# BMS1.net
KiCad netlist of a schematic drawn in Altium Designer
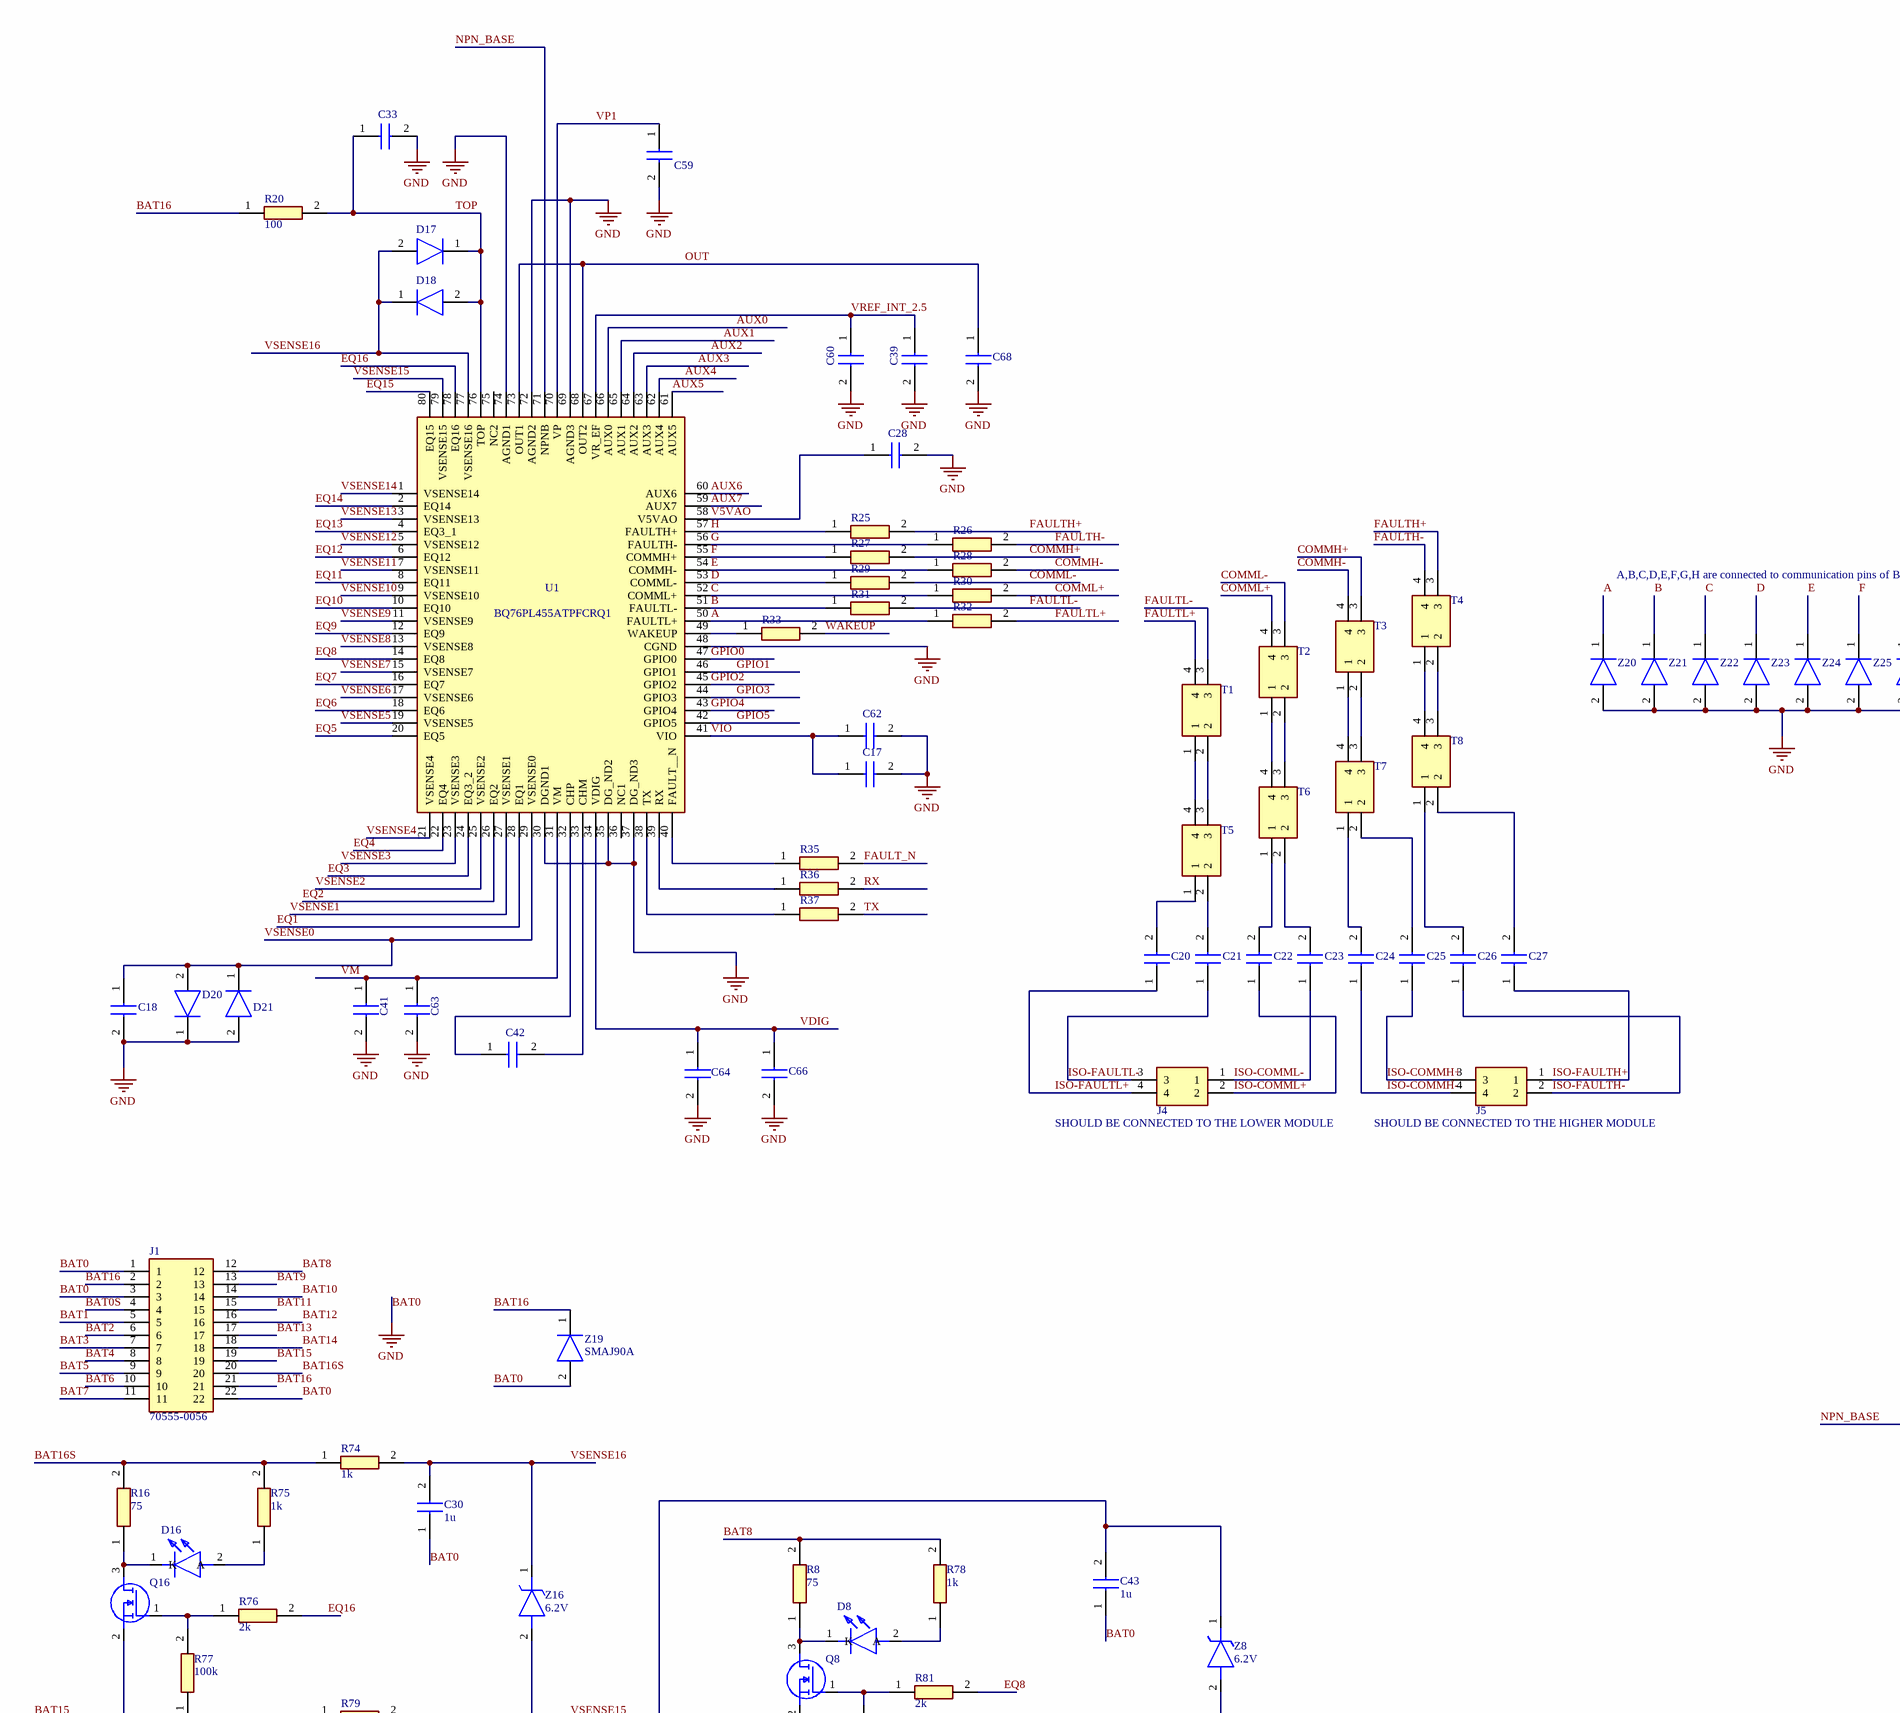
[diagram p0: BMS1.SchDoc, top left]
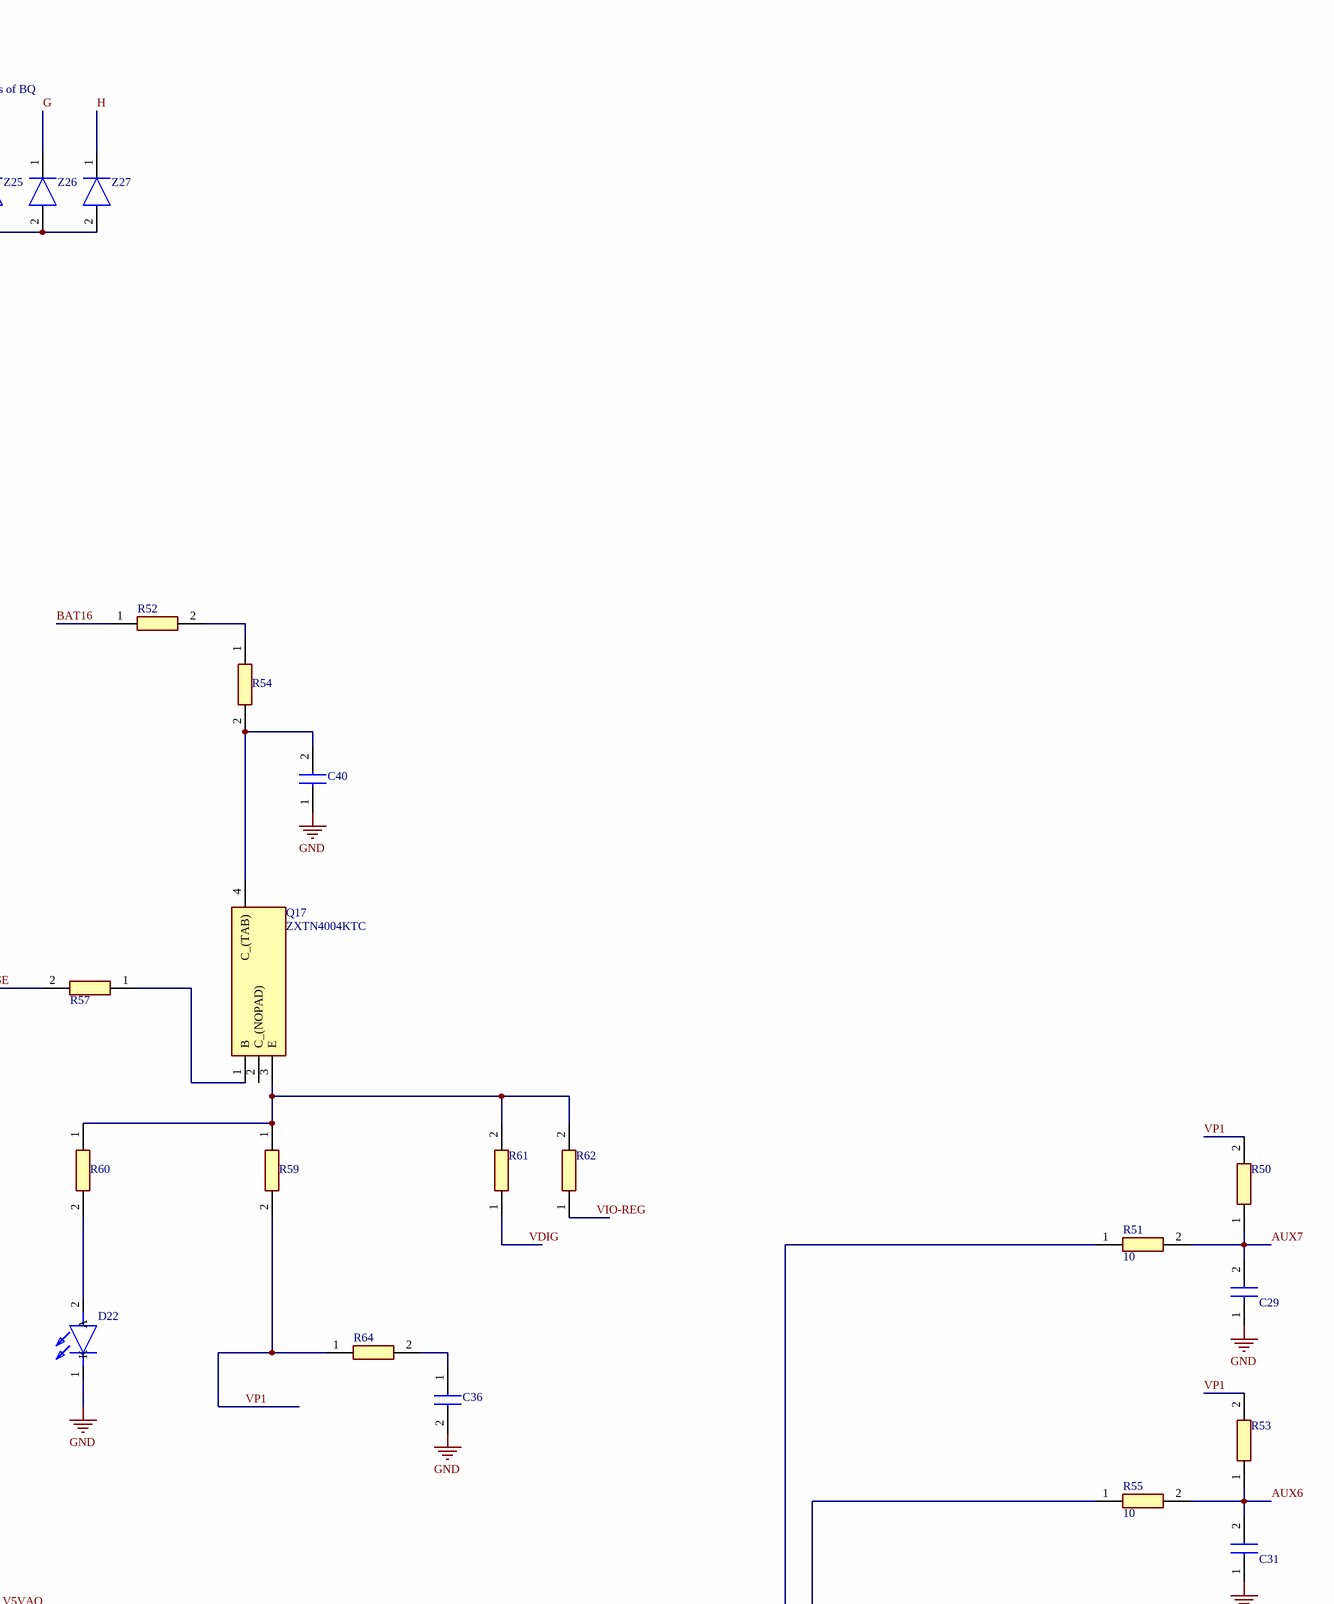
[diagram p1: BMS1.SchDoc, top right]
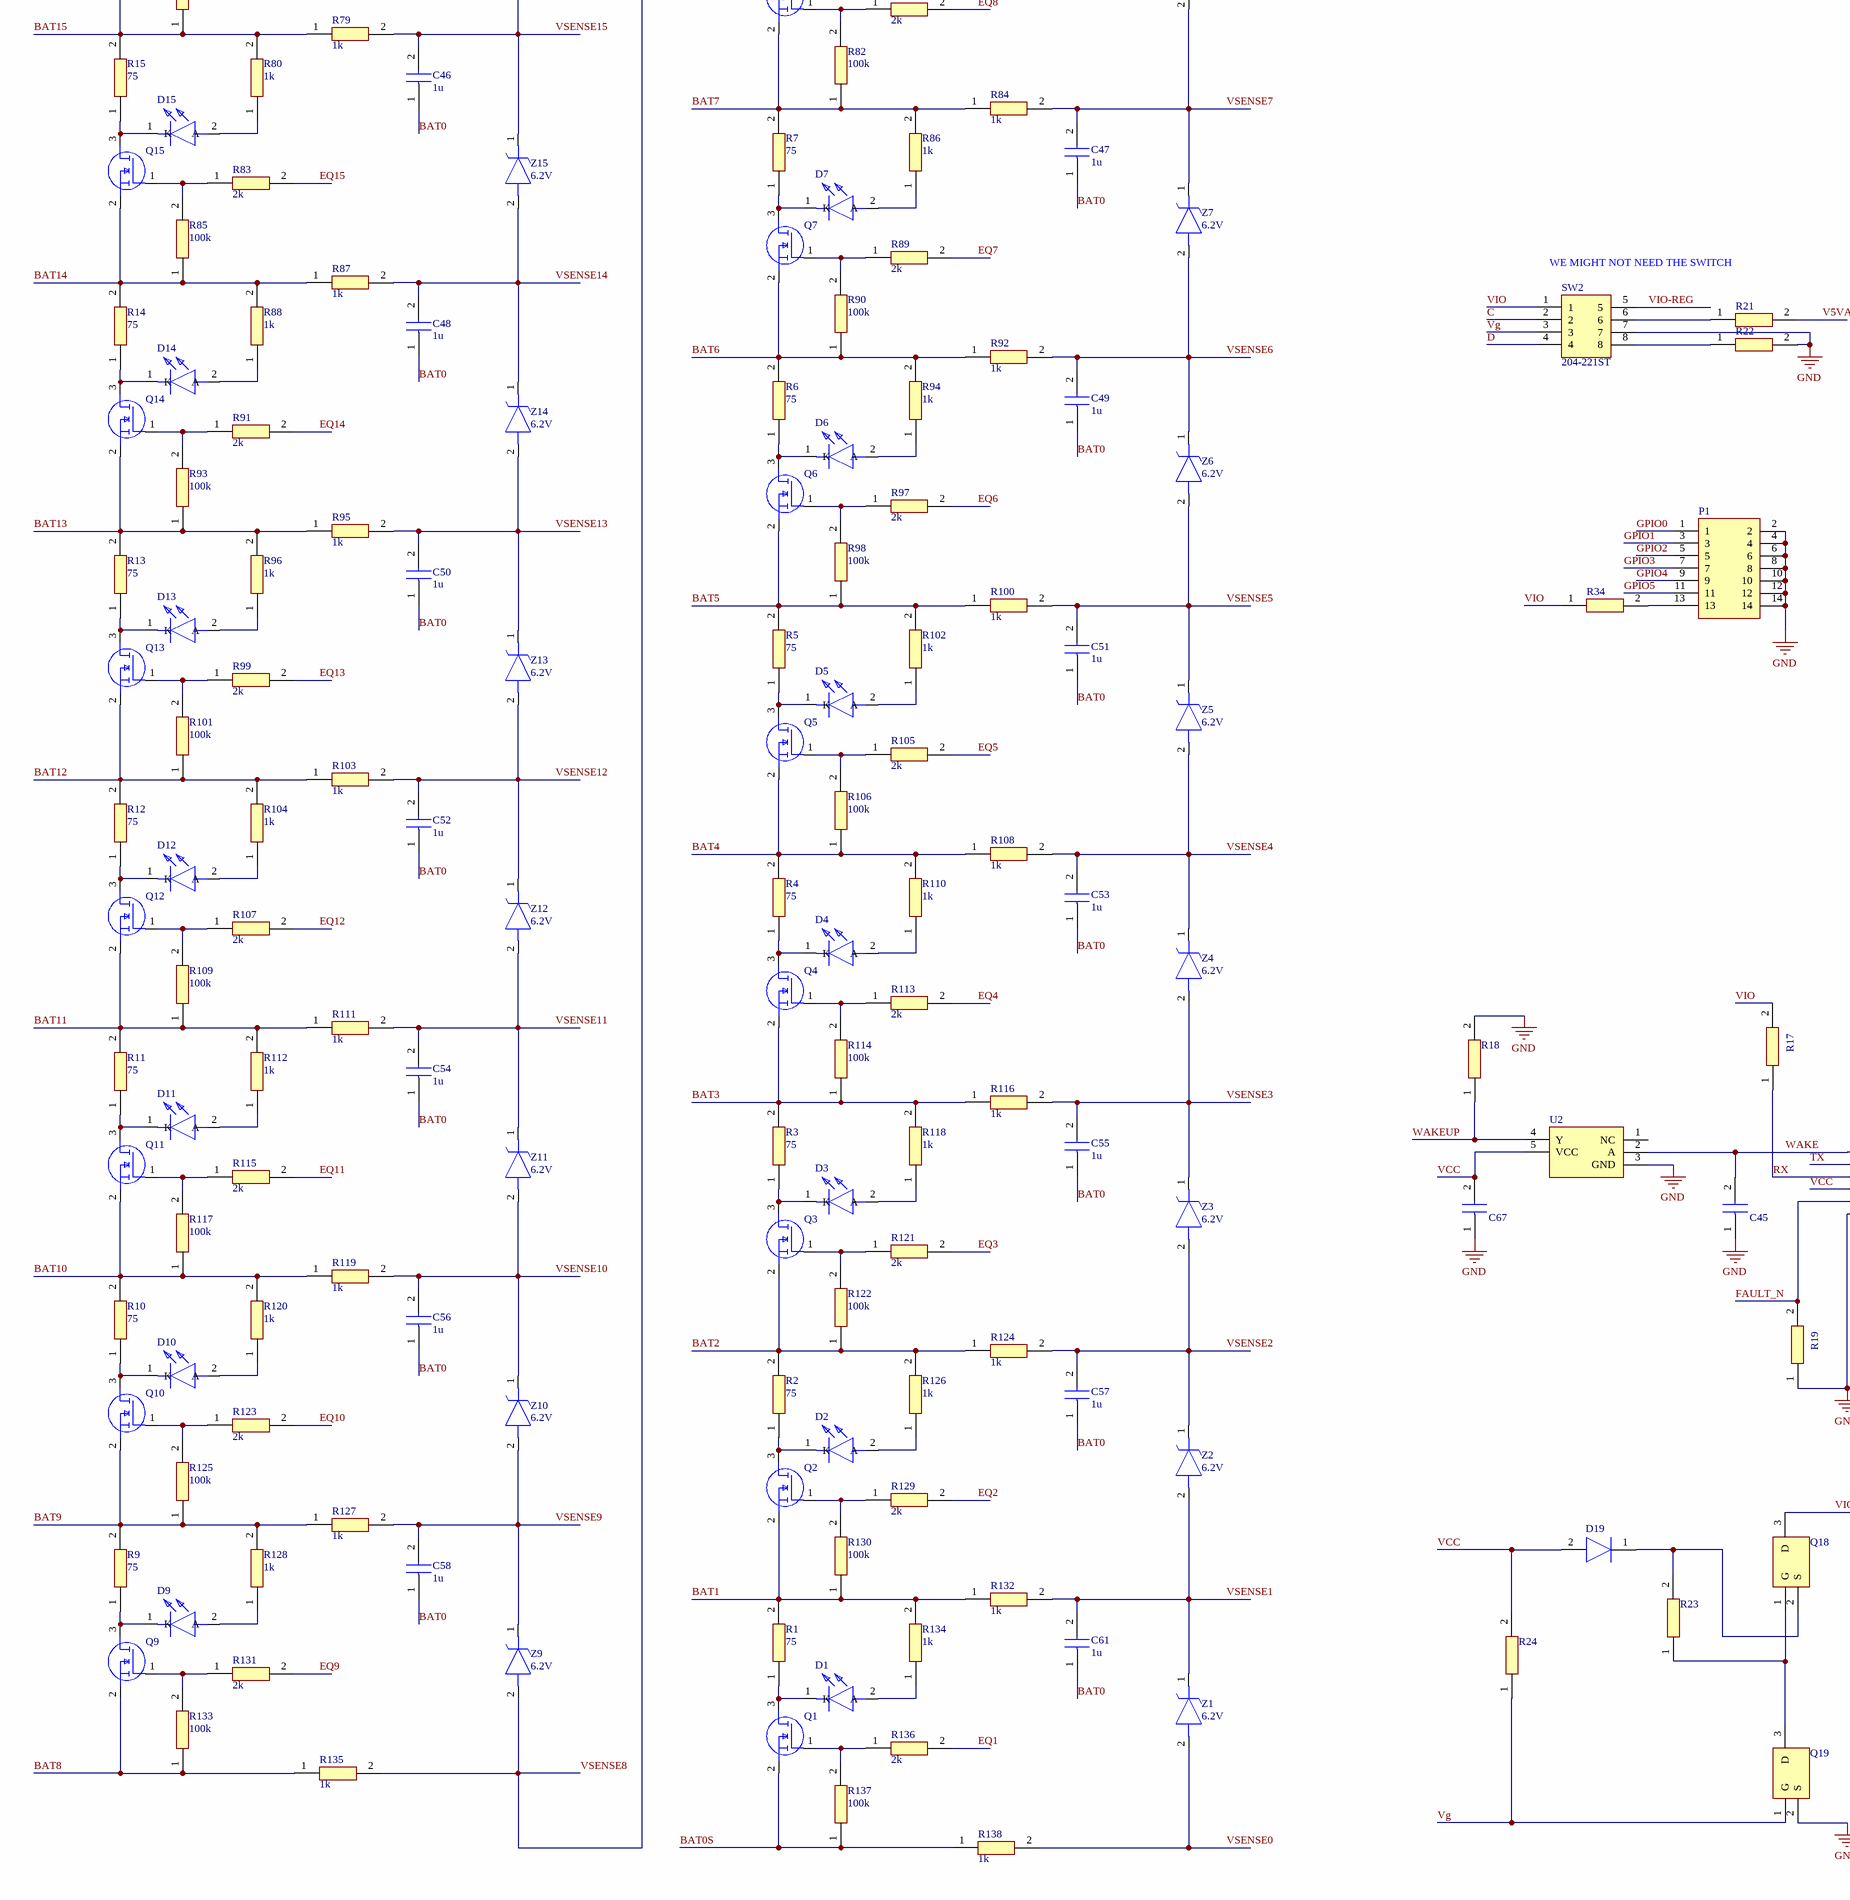
[diagram p2: BMS1.SchDoc, bottom left]
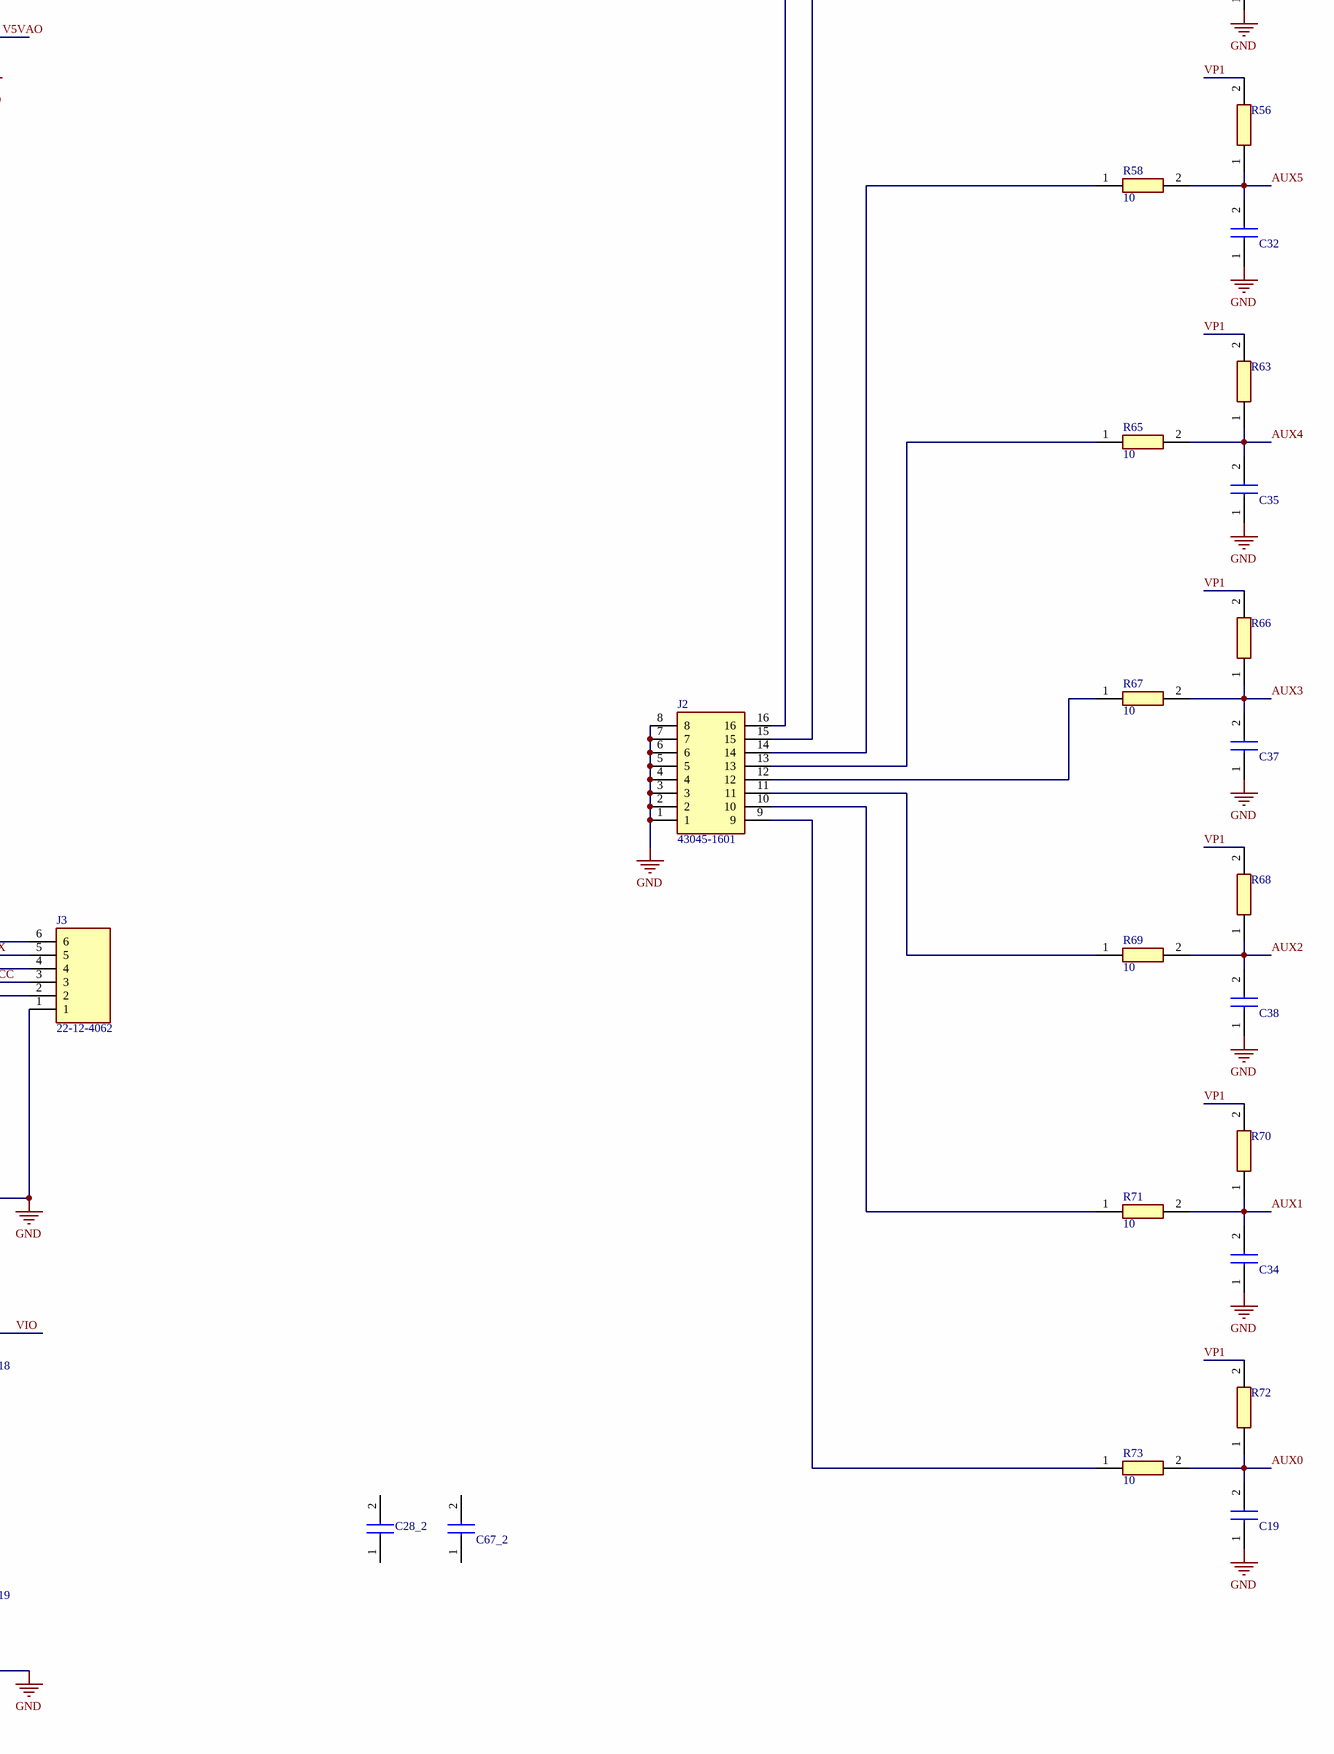
[diagram p3: BMS1.SchDoc, bottom right]

(export (version "E")
  (design (tool "Eeschema 10.0.6"))
  (components
    (comp (ref "C17")
      (value "1u")
      (footprint "SamacSys:CAPC1608X80N")
      (description "Capacitor")
      (fields
        (field (name "MANUFACTURER_PART_NUMBER") "C1608X7R1C105K080AC")
        (field (name "MOUSER PART NUMBER") "810-C1608X7R1C105K")
      )
      (libsource (lib "*") (part "C1608X7R1C105K080AC"))
    )
    (comp (ref "C18")
      (value "1u")
      (footprint "SamacSys:CAPC1608X80N")
      (description "Capacitor")
      (fields
        (field (name "MANUFACTURER_PART_NUMBER") "C1608X7R1C105K080AC")
        (field (name "MOUSER PART NUMBER") "810-C1608X7R1C105K")
      )
      (libsource (lib "*") (part "C1608X7R1C105K080AC"))
    )
    (comp (ref "C19")
      (value "C1608X7R1H104K080AA")
      (footprint "SamacSys:CAPC1608X80N")
      (description "Capacitor")
      (fields
        (field (name "MOUSER PART NUMBER") "810-C1608X7R1H104K")
        (field (name "RS PART NUMBER") "7414459P")
      )
      (libsource (lib "*") (part "C1608X7R1H104K080AA"))
    )
    (comp (ref "C20")
      (value "CC1206KKX7RCBB102")
      (footprint "SamacSys:CAPC3216X70N")
      (description "Capacitor")
      (fields (field (name "MOUSER PART NUMBER") "603-CC126KKX7RCBB102"))
      (libsource (lib "*") (part "CC1206KKX7RCBB102"))
    )
    (comp (ref "C21")
      (value "CC1206KKX7RCBB102")
      (footprint "SamacSys:CAPC3216X70N")
      (description "Capacitor")
      (fields (field (name "MOUSER PART NUMBER") "603-CC126KKX7RCBB102"))
      (libsource (lib "*") (part "CC1206KKX7RCBB102"))
    )
    (comp (ref "C22")
      (value "CC1206KKX7RCBB102")
      (footprint "SamacSys:CAPC3216X70N")
      (description "Capacitor")
      (fields (field (name "MOUSER PART NUMBER") "603-CC126KKX7RCBB102"))
      (libsource (lib "*") (part "CC1206KKX7RCBB102"))
    )
    (comp (ref "C23")
      (value "CC1206KKX7RCBB102")
      (footprint "SamacSys:CAPC3216X70N")
      (description "Capacitor")
      (fields (field (name "MOUSER PART NUMBER") "603-CC126KKX7RCBB102"))
      (libsource (lib "*") (part "CC1206KKX7RCBB102"))
    )
    (comp (ref "C24")
      (value "CC1206KKX7RCBB102")
      (footprint "SamacSys:CAPC3216X70N")
      (description "Capacitor")
      (fields (field (name "MOUSER PART NUMBER") "603-CC126KKX7RCBB102"))
      (libsource (lib "*") (part "CC1206KKX7RCBB102"))
    )
    (comp (ref "C25")
      (value "CC1206KKX7RCBB102")
      (footprint "SamacSys:CAPC3216X70N")
      (description "Capacitor")
      (fields (field (name "MOUSER PART NUMBER") "603-CC126KKX7RCBB102"))
      (libsource (lib "*") (part "CC1206KKX7RCBB102"))
    )
    (comp (ref "C26")
      (value "CC1206KKX7RCBB102")
      (footprint "SamacSys:CAPC3216X70N")
      (description "Capacitor")
      (fields (field (name "MOUSER PART NUMBER") "603-CC126KKX7RCBB102"))
      (libsource (lib "*") (part "CC1206KKX7RCBB102"))
    )
    (comp (ref "C27")
      (value "CC1206KKX7RCBB102")
      (footprint "SamacSys:CAPC3216X70N")
      (description "Capacitor")
      (fields (field (name "MOUSER PART NUMBER") "603-CC126KKX7RCBB102"))
      (libsource (lib "*") (part "CC1206KKX7RCBB102"))
    )
    (comp (ref "C28")
      (value "4.7u")
      (footprint "SamacSys:CAPC2012X145N")
      (description "Capacitor")
      (fields
        (field (name "MANUFACTURER_PART_NUMBER") "GRM21BR71C475KA73L")
        (field (name "MOUSER PART NUMBER") "81-GRM21BR71C475KA73")
      )
      (libsource (lib "*") (part "GRM21BR71C475KA73L"))
    )
    (comp (ref "C28_2")
      (value "0805YC475KAT2A")
      (footprint "SamacSys:CAPC2013X152N")
      (description "Capacitor")
      (fields
        (field (name "MOUSER PART NUMBER") "581-0805YC475KAT2A")
        (field (name "RS PART NUMBER") "6983554P")
      )
      (libsource (lib "*") (part "0805YC475KAT2A"))
    )
    (comp (ref "C29")
      (value "C1608X7R1H104K080AA")
      (footprint "SamacSys:CAPC1608X80N")
      (description "Capacitor")
      (fields
        (field (name "MOUSER PART NUMBER") "810-C1608X7R1H104K")
        (field (name "RS PART NUMBER") "7414459P")
      )
      (libsource (lib "*") (part "C1608X7R1H104K080AA"))
    )
    (comp (ref "C30")
      (value "1u")
      (footprint "SamacSys:CAPC3225X180N")
      (description "Capacitor")
      (fields
        (field (name "MANUFACTURER_PART_NUMBER") "GRM32CR72A105KA35L")
        (field (name "MOUSER PART NUMBER") "81-GRM32CR72A105KA35")
      )
      (libsource (lib "*") (part "GRM32CR72A105KA35L"))
    )
    (comp (ref "C31")
      (value "C1608X7R1H104K080AA")
      (footprint "SamacSys:CAPC1608X80N")
      (description "Capacitor")
      (fields
        (field (name "MOUSER PART NUMBER") "810-C1608X7R1H104K")
        (field (name "RS PART NUMBER") "7414459P")
      )
      (libsource (lib "*") (part "C1608X7R1H104K080AA"))
    )
    (comp (ref "C32")
      (value "C1608X7R1H104K080AA")
      (footprint "SamacSys:CAPC1608X80N")
      (description "Capacitor")
      (fields
        (field (name "MOUSER PART NUMBER") "810-C1608X7R1H104K")
        (field (name "RS PART NUMBER") "7414459P")
      )
      (libsource (lib "*") (part "C1608X7R1H104K080AA"))
    )
    (comp (ref "C33")
      (value "0.1u")
      (footprint "SamacSys:CAPC3225X150N")
      (description "Capacitor")
      (fields
        (field (name "MANUFACTURER_PART_NUMBER") "GRM32NR72A104KA01L")
        (field (name "MOUSER PART NUMBER") "81-GRM422X104K100L")
      )
      (libsource (lib "*") (part "GRM32NR72A104KA01L"))
    )
    (comp (ref "C34")
      (value "C1608X7R1H104K080AA")
      (footprint "SamacSys:CAPC1608X80N")
      (description "Capacitor")
      (fields
        (field (name "MOUSER PART NUMBER") "810-C1608X7R1H104K")
        (field (name "RS PART NUMBER") "7414459P")
      )
      (libsource (lib "*") (part "C1608X7R1H104K080AA"))
    )
    (comp (ref "C35")
      (value "C1608X7R1H104K080AA")
      (footprint "SamacSys:CAPC1608X80N")
      (description "Capacitor")
      (fields
        (field (name "MOUSER PART NUMBER") "810-C1608X7R1H104K")
        (field (name "RS PART NUMBER") "7414459P")
      )
      (libsource (lib "*") (part "C1608X7R1H104K080AA"))
    )
    (comp (ref "C36")
      (value "GRM31CR71H475KA12L")
      (footprint "SamacSys:CAPC3216X180N")
      (description "Capacitor")
      (fields
        (field (name "MOUSER PART NUMBER") "81-GRM31CR71H475KA2L")
        (field (name "RS PART NUMBER") "7236580P")
      )
      (libsource (lib "*") (part "GRM31CR71H475KA12L"))
    )
    (comp (ref "C37")
      (value "C1608X7R1H104K080AA")
      (footprint "SamacSys:CAPC1608X80N")
      (description "Capacitor")
      (fields
        (field (name "MOUSER PART NUMBER") "810-C1608X7R1H104K")
        (field (name "RS PART NUMBER") "7414459P")
      )
      (libsource (lib "*") (part "C1608X7R1H104K080AA"))
    )
    (comp (ref "C38")
      (value "C1608X7R1H104K080AA")
      (footprint "SamacSys:CAPC1608X80N")
      (description "Capacitor")
      (fields
        (field (name "MOUSER PART NUMBER") "810-C1608X7R1H104K")
        (field (name "RS PART NUMBER") "7414459P")
      )
      (libsource (lib "*") (part "C1608X7R1H104K080AA"))
    )
    (comp (ref "C39")
      (value "0.1u")
      (footprint "SamacSys:CAPC1608X95N")
      (description "Capacitor")
      (fields
        (field (name "MANUFACTURER_PART_NUMBER") "C0603X104K3RACTU")
        (field (name "MOUSER PART NUMBER") "80-C0603X104K3R")
      )
      (libsource (lib "*") (part "C0603X104K3RACTU"))
    )
    (comp (ref "C40")
      (value "GRM31CR72A105KA01L")
      (footprint "SamacSys:CAPC3216X180N")
      (description "Capacitor")
      (fields
        (field (name "MOUSER PART NUMBER") "81-GRM31CR72A105KA01")
        (field (name "RS PART NUMBER") "7236584P")
      )
      (libsource (lib "*") (part "GRM31CR72A105KA01L"))
    )
    (comp (ref "C41")
      (value "4.7u")
      (footprint "SamacSys:CAPC2012X145N")
      (description "Capacitor")
      (fields
        (field (name "MANUFACTURER_PART_NUMBER") "GRM21BR71C475KA73L")
        (field (name "MOUSER PART NUMBER") "81-GRM21BR71C475KA73")
      )
      (libsource (lib "*") (part "GRM21BR71C475KA73L"))
    )
    (comp (ref "C42")
      (value "22n")
      (footprint "SamacSys:CAPC1608X80N")
      (description "Capacitor")
      (fields
        (field (name "MANUFACTURER_PART_NUMBER") "C1608X7R1H223K080AA")
        (field (name "MOUSER PART NUMBER") "810-C1608X7R1H223K")
      )
      (libsource (lib "*") (part "C1608X7R1H223K080AA"))
    )
    (comp (ref "C43")
      (value "1u")
      (footprint "SamacSys:CAPC3225X180N")
      (description "Capacitor")
      (fields
        (field (name "MANUFACTURER_PART_NUMBER") "GRM32CR72A105KA35L")
        (field (name "MOUSER PART NUMBER") "81-GRM32CR72A105KA35")
      )
      (libsource (lib "*") (part "GRM32CR72A105KA35L"))
    )
    (comp (ref "C45")
      (value "GRM188R71C104KA01D")
      (footprint "SamacSys:CAPC1608X90N")
      (description "Capacitor")
      (fields (field (name "MOUSER PART NUMBER") "81-GRM39X104K16") (field (name "RS PART NUMBER") "2207922"))
      (libsource (lib "*") (part "GRM188R71C104KA01D"))
    )
    (comp (ref "C46")
      (value "1u")
      (footprint "SamacSys:CAPC3225X180N")
      (description "Capacitor")
      (fields
        (field (name "MANUFACTURER_PART_NUMBER") "GRM32CR72A105KA35L")
        (field (name "MOUSER PART NUMBER") "81-GRM32CR72A105KA35")
      )
      (libsource (lib "*") (part "GRM32CR72A105KA35L"))
    )
    (comp (ref "C47")
      (value "1u")
      (footprint "SamacSys:CAPC3225X180N")
      (description "Capacitor")
      (fields
        (field (name "MANUFACTURER_PART_NUMBER") "GRM32CR72A105KA35L")
        (field (name "MOUSER PART NUMBER") "81-GRM32CR72A105KA35")
      )
      (libsource (lib "*") (part "GRM32CR72A105KA35L"))
    )
    (comp (ref "C48")
      (value "1u")
      (footprint "SamacSys:CAPC3225X180N")
      (description "Capacitor")
      (fields
        (field (name "MANUFACTURER_PART_NUMBER") "GRM32CR72A105KA35L")
        (field (name "MOUSER PART NUMBER") "81-GRM32CR72A105KA35")
      )
      (libsource (lib "*") (part "GRM32CR72A105KA35L"))
    )
    (comp (ref "C49")
      (value "1u")
      (footprint "SamacSys:CAPC3225X180N")
      (description "Capacitor")
      (fields
        (field (name "MANUFACTURER_PART_NUMBER") "GRM32CR72A105KA35L")
        (field (name "MOUSER PART NUMBER") "81-GRM32CR72A105KA35")
      )
      (libsource (lib "*") (part "GRM32CR72A105KA35L"))
    )
    (comp (ref "C50")
      (value "1u")
      (footprint "SamacSys:CAPC3225X180N")
      (description "Capacitor")
      (fields
        (field (name "MANUFACTURER_PART_NUMBER") "GRM32CR72A105KA35L")
        (field (name "MOUSER PART NUMBER") "81-GRM32CR72A105KA35")
      )
      (libsource (lib "*") (part "GRM32CR72A105KA35L"))
    )
    (comp (ref "C51")
      (value "1u")
      (footprint "SamacSys:CAPC3225X180N")
      (description "Capacitor")
      (fields
        (field (name "MANUFACTURER_PART_NUMBER") "GRM32CR72A105KA35L")
        (field (name "MOUSER PART NUMBER") "81-GRM32CR72A105KA35")
      )
      (libsource (lib "*") (part "GRM32CR72A105KA35L"))
    )
    (comp (ref "C52")
      (value "1u")
      (footprint "SamacSys:CAPC3225X180N")
      (description "Capacitor")
      (fields
        (field (name "MANUFACTURER_PART_NUMBER") "GRM32CR72A105KA35L")
        (field (name "MOUSER PART NUMBER") "81-GRM32CR72A105KA35")
      )
      (libsource (lib "*") (part "GRM32CR72A105KA35L"))
    )
    (comp (ref "C53")
      (value "1u")
      (footprint "SamacSys:CAPC3225X180N")
      (description "Capacitor")
      (fields
        (field (name "MANUFACTURER_PART_NUMBER") "GRM32CR72A105KA35L")
        (field (name "MOUSER PART NUMBER") "81-GRM32CR72A105KA35")
      )
      (libsource (lib "*") (part "GRM32CR72A105KA35L"))
    )
    (comp (ref "C54")
      (value "1u")
      (footprint "SamacSys:CAPC3225X180N")
      (description "Capacitor")
      (fields
        (field (name "MANUFACTURER_PART_NUMBER") "GRM32CR72A105KA35L")
        (field (name "MOUSER PART NUMBER") "81-GRM32CR72A105KA35")
      )
      (libsource (lib "*") (part "GRM32CR72A105KA35L"))
    )
    (comp (ref "C55")
      (value "1u")
      (footprint "SamacSys:CAPC3225X180N")
      (description "Capacitor")
      (fields
        (field (name "MANUFACTURER_PART_NUMBER") "GRM32CR72A105KA35L")
        (field (name "MOUSER PART NUMBER") "81-GRM32CR72A105KA35")
      )
      (libsource (lib "*") (part "GRM32CR72A105KA35L"))
    )
    (comp (ref "C56")
      (value "1u")
      (footprint "SamacSys:CAPC3225X180N")
      (description "Capacitor")
      (fields
        (field (name "MANUFACTURER_PART_NUMBER") "GRM32CR72A105KA35L")
        (field (name "MOUSER PART NUMBER") "81-GRM32CR72A105KA35")
      )
      (libsource (lib "*") (part "GRM32CR72A105KA35L"))
    )
    (comp (ref "C57")
      (value "1u")
      (footprint "SamacSys:CAPC3225X180N")
      (description "Capacitor")
      (fields
        (field (name "MANUFACTURER_PART_NUMBER") "GRM32CR72A105KA35L")
        (field (name "MOUSER PART NUMBER") "81-GRM32CR72A105KA35")
      )
      (libsource (lib "*") (part "GRM32CR72A105KA35L"))
    )
    (comp (ref "C58")
      (value "1u")
      (footprint "SamacSys:CAPC3225X180N")
      (description "Capacitor")
      (fields
        (field (name "MANUFACTURER_PART_NUMBER") "GRM32CR72A105KA35L")
        (field (name "MOUSER PART NUMBER") "81-GRM32CR72A105KA35")
      )
      (libsource (lib "*") (part "GRM32CR72A105KA35L"))
    )
    (comp (ref "C59")
      (value "0.1u")
      (footprint "SamacSys:CAPC1608X95N")
      (description "Capacitor")
      (fields
        (field (name "MANUFACTURER_PART_NUMBER") "C0603X104K3RACTU")
        (field (name "MOUSER PART NUMBER") "80-C0603X104K3R")
      )
      (libsource (lib "*") (part "C0603X104K3RACTU"))
    )
    (comp (ref "C60")
      (value "1.8u")
      (footprint "SamacSys:CAPC3225X170N")
      (description "Capacitor")
      (fields
        (field (name "MANUFACTURER_PART_NUMBER") "C1210C185K3RACTU")
        (field (name "MOUSER PART NUMBER") "80-C1210C185K3R")
      )
      (libsource (lib "*") (part "C1210C185K3RACTU"))
    )
    (comp (ref "C61")
      (value "1u")
      (footprint "SamacSys:CAPC3225X180N")
      (description "Capacitor")
      (fields
        (field (name "MANUFACTURER_PART_NUMBER") "GRM32CR72A105KA35L")
        (field (name "MOUSER PART NUMBER") "81-GRM32CR72A105KA35")
      )
      (libsource (lib "*") (part "GRM32CR72A105KA35L"))
    )
    (comp (ref "C62")
      (value "0.1u")
      (footprint "SamacSys:CAPC1608X95N")
      (description "Capacitor")
      (fields
        (field (name "MANUFACTURER_PART_NUMBER") "C0603X104K3RACTU")
        (field (name "MOUSER PART NUMBER") "80-C0603X104K3R")
      )
      (libsource (lib "*") (part "C0603X104K3RACTU"))
    )
    (comp (ref "C63")
      (value "0.1u")
      (footprint "SamacSys:CAPC1608X95N")
      (description "Capacitor")
      (fields
        (field (name "MANUFACTURER_PART_NUMBER") "C0603X104K3RACTU")
        (field (name "MOUSER PART NUMBER") "80-C0603X104K3R")
      )
      (libsource (lib "*") (part "C0603X104K3RACTU"))
    )
    (comp (ref "C64")
      (value "0.1u")
      (footprint "SamacSys:CAPC1608X95N")
      (description "Capacitor")
      (fields
        (field (name "MANUFACTURER_PART_NUMBER") "C0603X104K3RACTU")
        (field (name "MOUSER PART NUMBER") "80-C0603X104K3R")
      )
      (libsource (lib "*") (part "C0603X104K3RACTU"))
    )
    (comp (ref "C66")
      (value "4.7u")
      (footprint "SamacSys:CAPC2012X145N")
      (description "Capacitor")
      (fields
        (field (name "MANUFACTURER_PART_NUMBER") "GRM21BR71C475KA73L")
        (field (name "MOUSER PART NUMBER") "81-GRM21BR71C475KA73")
      )
      (libsource (lib "*") (part "GRM21BR71C475KA73L"))
    )
    (comp (ref "C67")
      (value "GRM188R71C104KA01D")
      (footprint "SamacSys:CAPC1608X90N")
      (description "Capacitor")
      (fields (field (name "MOUSER PART NUMBER") "81-GRM39X104K16") (field (name "RS PART NUMBER") "2207922"))
      (libsource (lib "*") (part "GRM188R71C104KA01D"))
    )
    (comp (ref "C67_2")
      (value "GRM188R72A104KA35D")
      (footprint "SamacSys:CAPC1608X90N")
      (description "Capacitor")
      (fields
        (field (name "MOUSER PART NUMBER") "81-GRM188R72A104KA35")
        (field (name "RS PART NUMBER") "7235742P")
      )
      (libsource (lib "*") (part "GRM188R72A104KA35D"))
    )
    (comp (ref "C68")
      (value "2700pF")
      (footprint "SamacSys:CAPC2012X147N")
      (description "Capacitor")
      (fields
        (field (name "MANUFACTURER_PART_NUMBER") "08055A272JAT2A")
        (field (name "MOUSER PART NUMBER") "581-08055A272JAT2A")
      )
      (libsource (lib "*") (part "08055A272JAT2A"))
    )
    (comp (ref "D1")
      (value "HSMG-C150")
      (footprint "SamacSys:LEDC3216X120N")
      (description "LED")
      (fields (field (name "MOUSER PART NUMBER") "630-HSMG-C150") (field (name "RS PART NUMBER") "4860531P"))
      (libsource (lib "*") (part "HSMG-C150"))
    )
    (comp (ref "D2")
      (value "HSMG-C150")
      (footprint "SamacSys:LEDC3216X120N")
      (description "LED")
      (fields (field (name "MOUSER PART NUMBER") "630-HSMG-C150") (field (name "RS PART NUMBER") "4860531P"))
      (libsource (lib "*") (part "HSMG-C150"))
    )
    (comp (ref "D3")
      (value "HSMG-C150")
      (footprint "SamacSys:LEDC3216X120N")
      (description "LED")
      (fields (field (name "MOUSER PART NUMBER") "630-HSMG-C150") (field (name "RS PART NUMBER") "4860531P"))
      (libsource (lib "*") (part "HSMG-C150"))
    )
    (comp (ref "D4")
      (value "HSMG-C150")
      (footprint "SamacSys:LEDC3216X120N")
      (description "LED")
      (fields (field (name "MOUSER PART NUMBER") "630-HSMG-C150") (field (name "RS PART NUMBER") "4860531P"))
      (libsource (lib "*") (part "HSMG-C150"))
    )
    (comp (ref "D5")
      (value "HSMG-C150")
      (footprint "SamacSys:LEDC3216X120N")
      (description "LED")
      (fields (field (name "MOUSER PART NUMBER") "630-HSMG-C150") (field (name "RS PART NUMBER") "4860531P"))
      (libsource (lib "*") (part "HSMG-C150"))
    )
    (comp (ref "D6")
      (value "HSMG-C150")
      (footprint "SamacSys:LEDC3216X120N")
      (description "LED")
      (fields (field (name "MOUSER PART NUMBER") "630-HSMG-C150") (field (name "RS PART NUMBER") "4860531P"))
      (libsource (lib "*") (part "HSMG-C150"))
    )
    (comp (ref "D7")
      (value "HSMG-C150")
      (footprint "SamacSys:LEDC3216X120N")
      (description "LED")
      (fields (field (name "MOUSER PART NUMBER") "630-HSMG-C150") (field (name "RS PART NUMBER") "4860531P"))
      (libsource (lib "*") (part "HSMG-C150"))
    )
    (comp (ref "D8")
      (value "HSMG-C150")
      (footprint "SamacSys:LEDC3216X120N")
      (description "LED")
      (fields (field (name "MOUSER PART NUMBER") "630-HSMG-C150") (field (name "RS PART NUMBER") "4860531P"))
      (libsource (lib "*") (part "HSMG-C150"))
    )
    (comp (ref "D9")
      (value "HSMG-C150")
      (footprint "SamacSys:LEDC3216X120N")
      (description "LED")
      (fields (field (name "MOUSER PART NUMBER") "630-HSMG-C150") (field (name "RS PART NUMBER") "4860531P"))
      (libsource (lib "*") (part "HSMG-C150"))
    )
    (comp (ref "D10")
      (value "HSMG-C150")
      (footprint "SamacSys:LEDC3216X120N")
      (description "LED")
      (fields (field (name "MOUSER PART NUMBER") "630-HSMG-C150") (field (name "RS PART NUMBER") "4860531P"))
      (libsource (lib "*") (part "HSMG-C150"))
    )
    (comp (ref "D11")
      (value "HSMG-C150")
      (footprint "SamacSys:LEDC3216X120N")
      (description "LED")
      (fields (field (name "MOUSER PART NUMBER") "630-HSMG-C150") (field (name "RS PART NUMBER") "4860531P"))
      (libsource (lib "*") (part "HSMG-C150"))
    )
    (comp (ref "D12")
      (value "HSMG-C150")
      (footprint "SamacSys:LEDC3216X120N")
      (description "LED")
      (fields (field (name "MOUSER PART NUMBER") "630-HSMG-C150") (field (name "RS PART NUMBER") "4860531P"))
      (libsource (lib "*") (part "HSMG-C150"))
    )
    (comp (ref "D13")
      (value "HSMG-C150")
      (footprint "SamacSys:LEDC3216X120N")
      (description "LED")
      (fields (field (name "MOUSER PART NUMBER") "630-HSMG-C150") (field (name "RS PART NUMBER") "4860531P"))
      (libsource (lib "*") (part "HSMG-C150"))
    )
    (comp (ref "D14")
      (value "HSMG-C150")
      (footprint "SamacSys:LEDC3216X120N")
      (description "LED")
      (fields (field (name "MOUSER PART NUMBER") "630-HSMG-C150") (field (name "RS PART NUMBER") "4860531P"))
      (libsource (lib "*") (part "HSMG-C150"))
    )
    (comp (ref "D15")
      (value "HSMG-C150")
      (footprint "SamacSys:LEDC3216X120N")
      (description "LED")
      (fields (field (name "MOUSER PART NUMBER") "630-HSMG-C150") (field (name "RS PART NUMBER") "4860531P"))
      (libsource (lib "*") (part "HSMG-C150"))
    )
    (comp (ref "D16")
      (value "HSMG-C150")
      (footprint "SamacSys:LEDC3216X120N")
      (description "LED")
      (fields (field (name "MOUSER PART NUMBER") "630-HSMG-C150") (field (name "RS PART NUMBER") "4860531P"))
      (libsource (lib "*") (part "HSMG-C150"))
    )
    (comp (ref "D17")
      (value "100v")
      (footprint "SamacSys:SOD3716X115N")
      (description "Diode")
      (fields
        (field (name "MANUFACTURER_PART_NUMBER") "1N4148W-7-F")
        (field (name "MOUSER PART NUMBER") "621-1N4148W-F")
      )
      (libsource (lib "*") (part "1N4148W-7-F"))
    )
    (comp (ref "D18")
      (value "100V")
      (footprint "SamacSys:SOD3716X115N")
      (description "Diode")
      (fields
        (field (name "MANUFACTURER_PART_NUMBER") "1N4148W-7-F")
        (field (name "MOUSER PART NUMBER") "621-1N4148W-F")
      )
      (libsource (lib "*") (part "1N4148W-7-F"))
    )
    (comp (ref "D19")
      (value "1N5819HW-7-F")
      (footprint "SamacSys:SOD3716X145N")
      (description "Diode")
      (fields (field (name "MOUSER PART NUMBER") "621-1N5819HW-F") (field (name "RS PART NUMBER") "7082197P"))
      (libsource (lib "*") (part "1N5819HW-7-F"))
    )
    (comp (ref "D20")
      (value "100v")
      (footprint "SamacSys:SOD3716X115N")
      (description "Diode")
      (fields
        (field (name "MANUFACTURER_PART_NUMBER") "1N4148W-7-F")
        (field (name "MOUSER PART NUMBER") "621-1N4148W-F")
      )
      (libsource (lib "*") (part "1N4148W-7-F"))
    )
    (comp (ref "D21")
      (value "100v")
      (footprint "SamacSys:SOD3716X115N")
      (description "Diode")
      (fields
        (field (name "MANUFACTURER_PART_NUMBER") "1N4148W-7-F")
        (field (name "MOUSER PART NUMBER") "621-1N4148W-F")
      )
      (libsource (lib "*") (part "1N4148W-7-F"))
    )
    (comp (ref "D22")
      (value "HSMG-C150")
      (footprint "SamacSys:LEDC3216X120N")
      (description "LED")
      (fields (field (name "MOUSER PART NUMBER") "630-HSMG-C150") (field (name "RS PART NUMBER") "4860531P"))
      (libsource (lib "*") (part "HSMG-C150"))
    )
    (comp (ref "J1")
      (value "70555-0056")
      (footprint "SamacSys:70555-0056")
      (description "Connector")
      (fields (field (name "MOUSER PART NUMBER") "538-70555-0056"))
      (libsource (lib "*") (part "70555-0056"))
    )
    (comp (ref "J2")
      (value "43045-1601")
      (footprint "SamacSys:0430451600")
      (description "Connector")
      (fields (field (name "MOUSER PART NUMBER") "538-43045-1601") (field (name "RS PART NUMBER") "6700504P"))
      (libsource (lib "*") (part "43045-1601"))
    )
    (comp (ref "J3")
      (value "22-12-4062")
      (footprint "SamacSys:22-12-4062")
      (description "Connector")
      (fields (field (name "MOUSER PART NUMBER") "538-22-12-4062") (field (name "RS PART NUMBER") "6701254P"))
      (libsource (lib "*") (part "22-12-4062"))
    )
    (comp (ref "J4")
      (value "70551-0038")
      (footprint "SamacSys:70551-0038_1")
      (description "Connector")
      (fields (field (name "MOUSER PART NUMBER") "538-70551-0038"))
      (libsource (lib "*") (part "70551-0038"))
    )
    (comp (ref "J5")
      (value "70551-0038")
      (footprint "SamacSys:70551-0038_1")
      (description "Connector")
      (fields (field (name "MOUSER PART NUMBER") "538-70551-0038"))
      (libsource (lib "*") (part "70551-0038"))
    )
    (comp (ref "P1")
      (value "HTSW-107-07-G-D")
      (footprint "SamacSys:HDRV14W64P254_2X7_1778X503X673P")
      (description "Connector")
      (fields (field (name "MOUSER PART NUMBER") "200-HTSW10707GD") (field (name "RS PART NUMBER") "1801877"))
      (libsource (lib "*") (part "HTSW-107-07-G-D"))
    )
    (comp (ref "Q1")
      (value "2V7002KT1G")
      (footprint "SamacSys:SOT96P237X111-3N")
      (description "MOSFET (N-Channel)")
      (fields (field (name "MOUSER PART NUMBER") "863-2V7002KT1G") (field (name "RS PART NUMBER") "8009361P"))
      (libsource (lib "*") (part "2V7002KT1G"))
    )
    (comp (ref "Q2")
      (value "2V7002KT1G")
      (footprint "SamacSys:SOT96P237X111-3N")
      (description "MOSFET (N-Channel)")
      (fields (field (name "MOUSER PART NUMBER") "863-2V7002KT1G") (field (name "RS PART NUMBER") "8009361P"))
      (libsource (lib "*") (part "2V7002KT1G"))
    )
    (comp (ref "Q3")
      (value "2V7002KT1G")
      (footprint "SamacSys:SOT96P237X111-3N")
      (description "MOSFET (N-Channel)")
      (fields (field (name "MOUSER PART NUMBER") "863-2V7002KT1G") (field (name "RS PART NUMBER") "8009361P"))
      (libsource (lib "*") (part "2V7002KT1G"))
    )
    (comp (ref "Q4")
      (value "2V7002KT1G")
      (footprint "SamacSys:SOT96P237X111-3N")
      (description "MOSFET (N-Channel)")
      (fields (field (name "MOUSER PART NUMBER") "863-2V7002KT1G") (field (name "RS PART NUMBER") "8009361P"))
      (libsource (lib "*") (part "2V7002KT1G"))
    )
    (comp (ref "Q5")
      (value "2V7002KT1G")
      (footprint "SamacSys:SOT96P237X111-3N")
      (description "MOSFET (N-Channel)")
      (fields (field (name "MOUSER PART NUMBER") "863-2V7002KT1G") (field (name "RS PART NUMBER") "8009361P"))
      (libsource (lib "*") (part "2V7002KT1G"))
    )
    (comp (ref "Q6")
      (value "2V7002KT1G")
      (footprint "SamacSys:SOT96P237X111-3N")
      (description "MOSFET (N-Channel)")
      (fields (field (name "MOUSER PART NUMBER") "863-2V7002KT1G") (field (name "RS PART NUMBER") "8009361P"))
      (libsource (lib "*") (part "2V7002KT1G"))
    )
    (comp (ref "Q7")
      (value "2V7002KT1G")
      (footprint "SamacSys:SOT96P237X111-3N")
      (description "MOSFET (N-Channel)")
      (fields (field (name "MOUSER PART NUMBER") "863-2V7002KT1G") (field (name "RS PART NUMBER") "8009361P"))
      (libsource (lib "*") (part "2V7002KT1G"))
    )
    (comp (ref "Q8")
      (value "2V7002KT1G")
      (footprint "SamacSys:SOT96P237X111-3N")
      (description "MOSFET (N-Channel)")
      (fields (field (name "MOUSER PART NUMBER") "863-2V7002KT1G") (field (name "RS PART NUMBER") "8009361P"))
      (libsource (lib "*") (part "2V7002KT1G"))
    )
    (comp (ref "Q9")
      (value "2V7002KT1G")
      (footprint "SamacSys:SOT96P237X111-3N")
      (description "MOSFET (N-Channel)")
      (fields (field (name "MOUSER PART NUMBER") "863-2V7002KT1G") (field (name "RS PART NUMBER") "8009361P"))
      (libsource (lib "*") (part "2V7002KT1G"))
    )
    (comp (ref "Q10")
      (value "2V7002KT1G")
      (footprint "SamacSys:SOT96P237X111-3N")
      (description "MOSFET (N-Channel)")
      (fields (field (name "MOUSER PART NUMBER") "863-2V7002KT1G") (field (name "RS PART NUMBER") "8009361P"))
      (libsource (lib "*") (part "2V7002KT1G"))
    )
    (comp (ref "Q11")
      (value "2V7002KT1G")
      (footprint "SamacSys:SOT96P237X111-3N")
      (description "MOSFET (N-Channel)")
      (fields (field (name "MOUSER PART NUMBER") "863-2V7002KT1G") (field (name "RS PART NUMBER") "8009361P"))
      (libsource (lib "*") (part "2V7002KT1G"))
    )
    (comp (ref "Q12")
      (value "2V7002KT1G")
      (footprint "SamacSys:SOT96P237X111-3N")
      (description "MOSFET (N-Channel)")
      (fields (field (name "MOUSER PART NUMBER") "863-2V7002KT1G") (field (name "RS PART NUMBER") "8009361P"))
      (libsource (lib "*") (part "2V7002KT1G"))
    )
    (comp (ref "Q13")
      (value "2V7002KT1G")
      (footprint "SamacSys:SOT96P237X111-3N")
      (description "MOSFET (N-Channel)")
      (fields (field (name "MOUSER PART NUMBER") "863-2V7002KT1G") (field (name "RS PART NUMBER") "8009361P"))
      (libsource (lib "*") (part "2V7002KT1G"))
    )
    (comp (ref "Q14")
      (value "2V7002KT1G")
      (footprint "SamacSys:SOT96P237X111-3N")
      (description "MOSFET (N-Channel)")
      (fields (field (name "MOUSER PART NUMBER") "863-2V7002KT1G") (field (name "RS PART NUMBER") "8009361P"))
      (libsource (lib "*") (part "2V7002KT1G"))
    )
    (comp (ref "Q15")
      (value "2V7002KT1G")
      (footprint "SamacSys:SOT96P237X111-3N")
      (description "MOSFET (N-Channel)")
      (fields (field (name "MOUSER PART NUMBER") "863-2V7002KT1G") (field (name "RS PART NUMBER") "8009361P"))
      (libsource (lib "*") (part "2V7002KT1G"))
    )
    (comp (ref "Q16")
      (value "2V7002KT1G")
      (footprint "SamacSys:SOT96P237X111-3N")
      (description "MOSFET (N-Channel)")
      (fields (field (name "MOUSER PART NUMBER") "863-2V7002KT1G") (field (name "RS PART NUMBER") "8009361P"))
      (libsource (lib "*") (part "2V7002KT1G"))
    )
    (comp (ref "Q17")
      (value "ZXTN4004KTC")
      (footprint "SamacSys:TO229P990X239-4N")
      (description "Transistor")
      (fields
        (field (name "MOUSER PART NUMBER") "621-ZXTN4004KTC")
        (field (name "RS PART NUMBER") "7705222P")
      )
      (libsource (lib "*") (part "ZXTN4004KTC"))
    )
    (comp (ref "Q18")
      (value "SI2319DS-T1-E3")
      (footprint "SamacSys:SOT95P237X112-3N")
      (description "Integrated Circuit")
      (fields
        (field (name "MOUSER PART NUMBER") "781-SI2319DS-T1-E3")
        (field (name "RS PART NUMBER") "7104689P")
      )
      (libsource (lib "*") (part "SI2319DS-T1-E3"))
    )
    (comp (ref "Q19")
      (value "2N7002E-T1-E3")
      (footprint "SamacSys:SOT95P237X112-3N")
      (description "Integrated Circuit")
      (fields (field (name "MOUSER PART NUMBER") "781-2N7002E-T1-E3"))
      (libsource (lib "*") (part "2N7002E-T1-E3"))
    )
    (comp (ref "R1")
      (value "75")
      (footprint "SamacSys:RESC6332X70N")
      (description "Resistor")
      (fields
        (field (name "MANUFACTURER_PART_NUMBER") "CRCW251275R0FKEG")
        (field (name "MOUSER PART NUMBER") "71-CRCW2512-75-E3")
      )
      (libsource (lib "*") (part "CRCW251275R0FKEG"))
    )
    (comp (ref "R2")
      (value "75")
      (footprint "SamacSys:RESC6332X70N")
      (description "Resistor")
      (fields
        (field (name "MANUFACTURER_PART_NUMBER") "CRCW251275R0FKEG")
        (field (name "MOUSER PART NUMBER") "71-CRCW2512-75-E3")
      )
      (libsource (lib "*") (part "CRCW251275R0FKEG"))
    )
    (comp (ref "R3")
      (value "75")
      (footprint "SamacSys:RESC6332X70N")
      (description "Resistor")
      (fields
        (field (name "MANUFACTURER_PART_NUMBER") "CRCW251275R0FKEG")
        (field (name "MOUSER PART NUMBER") "71-CRCW2512-75-E3")
      )
      (libsource (lib "*") (part "CRCW251275R0FKEG"))
    )
    (comp (ref "R4")
      (value "75")
      (footprint "SamacSys:RESC6332X70N")
      (description "Resistor")
      (fields
        (field (name "MANUFACTURER_PART_NUMBER") "CRCW251275R0FKEG")
        (field (name "MOUSER PART NUMBER") "71-CRCW2512-75-E3")
      )
      (libsource (lib "*") (part "CRCW251275R0FKEG"))
    )
    (comp (ref "R5")
      (value "75")
      (footprint "SamacSys:RESC6332X70N")
      (description "Resistor")
      (fields
        (field (name "MANUFACTURER_PART_NUMBER") "CRCW251275R0FKEG")
        (field (name "MOUSER PART NUMBER") "71-CRCW2512-75-E3")
      )
      (libsource (lib "*") (part "CRCW251275R0FKEG"))
    )
    (comp (ref "R6")
      (value "75")
      (footprint "SamacSys:RESC6332X70N")
      (description "Resistor")
      (fields
        (field (name "MANUFACTURER_PART_NUMBER") "CRCW251275R0FKEG")
        (field (name "MOUSER PART NUMBER") "71-CRCW2512-75-E3")
      )
      (libsource (lib "*") (part "CRCW251275R0FKEG"))
    )
    (comp (ref "R7")
      (value "75")
      (footprint "SamacSys:RESC6332X70N")
      (description "Resistor")
      (fields
        (field (name "MANUFACTURER_PART_NUMBER") "CRCW251275R0FKEG")
        (field (name "MOUSER PART NUMBER") "71-CRCW2512-75-E3")
      )
      (libsource (lib "*") (part "CRCW251275R0FKEG"))
    )
    (comp (ref "R8")
      (value "75")
      (footprint "SamacSys:RESC6332X70N")
      (description "Resistor")
      (fields
        (field (name "MANUFACTURER_PART_NUMBER") "CRCW251275R0FKEG")
        (field (name "MOUSER PART NUMBER") "71-CRCW2512-75-E3")
      )
      (libsource (lib "*") (part "CRCW251275R0FKEG"))
    )
    (comp (ref "R9")
      (value "75")
      (footprint "SamacSys:RESC6332X70N")
      (description "Resistor")
      (fields
        (field (name "MANUFACTURER_PART_NUMBER") "CRCW251275R0FKEG")
        (field (name "MOUSER PART NUMBER") "71-CRCW2512-75-E3")
      )
      (libsource (lib "*") (part "CRCW251275R0FKEG"))
    )
    (comp (ref "R10")
      (value "75")
      (footprint "SamacSys:RESC6332X70N")
      (description "Resistor")
      (fields
        (field (name "MANUFACTURER_PART_NUMBER") "CRCW251275R0FKEG")
        (field (name "MOUSER PART NUMBER") "71-CRCW2512-75-E3")
      )
      (libsource (lib "*") (part "CRCW251275R0FKEG"))
    )
    (comp (ref "R11")
      (value "75")
      (footprint "SamacSys:RESC6332X70N")
      (description "Resistor")
      (fields
        (field (name "MANUFACTURER_PART_NUMBER") "CRCW251275R0FKEG")
        (field (name "MOUSER PART NUMBER") "71-CRCW2512-75-E3")
      )
      (libsource (lib "*") (part "CRCW251275R0FKEG"))
    )
    (comp (ref "R12")
      (value "75")
      (footprint "SamacSys:RESC6332X70N")
      (description "Resistor")
      (fields
        (field (name "MANUFACTURER_PART_NUMBER") "CRCW251275R0FKEG")
        (field (name "MOUSER PART NUMBER") "71-CRCW2512-75-E3")
      )
      (libsource (lib "*") (part "CRCW251275R0FKEG"))
    )
    (comp (ref "R13")
      (value "75")
      (footprint "SamacSys:RESC6332X70N")
      (description "Resistor")
      (fields
        (field (name "MANUFACTURER_PART_NUMBER") "CRCW251275R0FKEG")
        (field (name "MOUSER PART NUMBER") "71-CRCW2512-75-E3")
      )
      (libsource (lib "*") (part "CRCW251275R0FKEG"))
    )
    (comp (ref "R14")
      (value "75")
      (footprint "SamacSys:RESC6332X70N")
      (description "Resistor")
      (fields
        (field (name "MANUFACTURER_PART_NUMBER") "CRCW251275R0FKEG")
        (field (name "MOUSER PART NUMBER") "71-CRCW2512-75-E3")
      )
      (libsource (lib "*") (part "CRCW251275R0FKEG"))
    )
    (comp (ref "R15")
      (value "75")
      (footprint "SamacSys:RESC6332X70N")
      (description "Resistor")
      (fields
        (field (name "MANUFACTURER_PART_NUMBER") "CRCW251275R0FKEG")
        (field (name "MOUSER PART NUMBER") "71-CRCW2512-75-E3")
      )
      (libsource (lib "*") (part "CRCW251275R0FKEG"))
    )
    (comp (ref "R16")
      (value "75")
      (footprint "SamacSys:RESC6332X70N")
      (description "Resistor")
      (fields
        (field (name "MANUFACTURER_PART_NUMBER") "CRCW251275R0FKEG")
        (field (name "MOUSER PART NUMBER") "71-CRCW2512-75-E3")
      )
      (libsource (lib "*") (part "CRCW251275R0FKEG"))
    )
    (comp (ref "R17")
      (value "CRCW060310K0FKEA")
      (footprint "SamacSys:RESC1608X50N")
      (description "Resistor")
      (fields
        (field (name "MOUSER PART NUMBER") "71-CRCW0603-10K-E3")
        (field (name "RS PART NUMBER") "6789667P")
      )
      (libsource (lib "*") (part "CRCW060310K0FKEA"))
    )
    (comp (ref "R18")
      (value "RC0603FR-07100KL")
      (footprint "SamacSys:RESC1608X55N")
      (description "Resistor")
      (fields
        (field (name "MOUSER PART NUMBER") "603-RC0603FR-07100KL")
        (field (name "RS PART NUMBER") "5048940")
      )
      (libsource (lib "") (part "RC0603FR-07100KL_1"))
    )
    (comp (ref "R19")
      (value "RC0603FR-0749K9L")
      (footprint "SamacSys:RESC1608X55N")
      (description "Resistor")
      (fields
        (field (name "MOUSER PART NUMBER") "603-RC0603FR-0749K9L")
        (field (name "RS PART NUMBER") "5047537")
      )
      (libsource (lib "*") (part "RC0603FR-0749K9L"))
    )
    (comp (ref "R20")
      (value "100")
      (footprint "SamacSys:RESC3216X60N")
      (description "Resistor")
      (fields
        (field (name "MANUFACTURER_PART_NUMBER") "CRCW1206100RFKEA")
        (field (name "MOUSER PART NUMBER") "71-CRCW1206-100-E3")
      )
      (libsource (lib "*") (part "CRCW1206100RFKEA"))
    )
    (comp (ref "R21")
      (value "RC0603FR-07100KL")
      (footprint "SamacSys:RESC1608X55N")
      (description "Resistor")
      (fields
        (field (name "MOUSER PART NUMBER") "603-RC0603FR-07100KL")
        (field (name "RS PART NUMBER") "5048940")
      )
      (libsource (lib "*") (part "RC0603FR-07100KL"))
    )
    (comp (ref "R22")
      (value "RC0603FR-07100KL")
      (footprint "SamacSys:RESC1608X55N")
      (description "Resistor")
      (fields
        (field (name "MOUSER PART NUMBER") "603-RC0603FR-07100KL")
        (field (name "RS PART NUMBER") "5048940")
      )
      (libsource (lib "*") (part "RC0603FR-07100KL"))
    )
    (comp (ref "R23")
      (value "RC0603FR-07100KL")
      (footprint "SamacSys:RESC1608X55N")
      (description "Resistor")
      (fields
        (field (name "MOUSER PART NUMBER") "603-RC0603FR-07100KL")
        (field (name "RS PART NUMBER") "5048940")
      )
      (libsource (lib "") (part "RC0603FR-07100KL_1"))
    )
    (comp (ref "R24")
      (value "RC0603FR-07100KL")
      (footprint "SamacSys:RESC1608X55N")
      (description "Resistor")
      (fields
        (field (name "MOUSER PART NUMBER") "603-RC0603FR-07100KL")
        (field (name "RS PART NUMBER") "5048940")
      )
      (libsource (lib "") (part "RC0603FR-07100KL_1"))
    )
    (comp (ref "R25")
      (value "10")
      (footprint "SamacSys:RESC3216X60N")
      (description "Resistor")
      (fields
        (field (name "MANUFACTURER_PART_NUMBER") "CRCW120610R0FKEA")
        (field (name "MOUSER PART NUMBER") "71-CRCW1206-10-E3")
      )
      (libsource (lib "*") (part "CRCW120610R0FKEA"))
    )
    (comp (ref "R26")
      (value "10")
      (footprint "SamacSys:RESC3216X60N")
      (description "Resistor")
      (fields
        (field (name "MANUFACTURER_PART_NUMBER") "CRCW120610R0FKEA")
        (field (name "MOUSER PART NUMBER") "71-CRCW1206-10-E3")
      )
      (libsource (lib "*") (part "CRCW120610R0FKEA"))
    )
    (comp (ref "R27")
      (value "10")
      (footprint "SamacSys:RESC3216X60N")
      (description "Resistor")
      (fields
        (field (name "MANUFACTURER_PART_NUMBER") "CRCW120610R0FKEA")
        (field (name "MOUSER PART NUMBER") "71-CRCW1206-10-E3")
      )
      (libsource (lib "*") (part "CRCW120610R0FKEA"))
    )
    (comp (ref "R28")
      (value "10")
      (footprint "SamacSys:RESC3216X60N")
      (description "Resistor")
      (fields
        (field (name "MANUFACTURER_PART_NUMBER") "CRCW120610R0FKEA")
        (field (name "MOUSER PART NUMBER") "71-CRCW1206-10-E3")
      )
      (libsource (lib "*") (part "CRCW120610R0FKEA"))
    )
    (comp (ref "R29")
      (value "10")
      (footprint "SamacSys:RESC3216X60N")
      (description "Resistor")
      (fields
        (field (name "MANUFACTURER_PART_NUMBER") "CRCW120610R0FKEA")
        (field (name "MOUSER PART NUMBER") "71-CRCW1206-10-E3")
      )
      (libsource (lib "*") (part "CRCW120610R0FKEA"))
    )
    (comp (ref "R30")
      (value "10")
      (footprint "SamacSys:RESC3216X60N")
      (description "Resistor")
      (fields
        (field (name "MANUFACTURER_PART_NUMBER") "CRCW120610R0FKEA")
        (field (name "MOUSER PART NUMBER") "71-CRCW1206-10-E3")
      )
      (libsource (lib "*") (part "CRCW120610R0FKEA"))
    )
    (comp (ref "R31")
      (value "10")
      (footprint "SamacSys:RESC3216X60N")
      (description "Resistor")
      (fields
        (field (name "MANUFACTURER_PART_NUMBER") "CRCW120610R0FKEA")
        (field (name "MOUSER PART NUMBER") "71-CRCW1206-10-E3")
      )
      (libsource (lib "*") (part "CRCW120610R0FKEA"))
    )
    (comp (ref "R32")
      (value "10")
      (footprint "SamacSys:RESC3216X60N")
      (description "Resistor")
      (fields
        (field (name "MANUFACTURER_PART_NUMBER") "CRCW120610R0FKEA")
        (field (name "MOUSER PART NUMBER") "71-CRCW1206-10-E3")
      )
      (libsource (lib "*") (part "CRCW120610R0FKEA"))
    )
    (comp (ref "R33")
      (value "49.9")
      (footprint "SamacSys:RESC1608X50N")
      (description "Resistor")
      (fields
        (field (name "MANUFACTURER_PART_NUMBER") "CRCW060349R9FKEA")
        (field (name "MOUSER PART NUMBER") "71-CRCW0603-49.9-E3")
      )
      (libsource (lib "*") (part "CRCW060349R9FKEA"))
    )
    (comp (ref "R34")
      (value "CRCW0603100RFKEA")
      (footprint "SamacSys:RESC1608X50N")
      (description "Resistor")
      (fields
        (field (name "MOUSER PART NUMBER") "71-CRCW0603-100-E3")
        (field (name "RS PART NUMBER") "2509682456")
      )
      (libsource (lib "*") (part "CRCW0603100RFKEA"))
    )
    (comp (ref "R35")
      (value "49.9")
      (footprint "SamacSys:RESC1608X50N")
      (description "Resistor")
      (fields
        (field (name "MANUFACTURER_PART_NUMBER") "CRCW060349R9FKEA")
        (field (name "MOUSER PART NUMBER") "71-CRCW0603-49.9-E3")
      )
      (libsource (lib "*") (part "CRCW060349R9FKEA"))
    )
    (comp (ref "R36")
      (value "49.9")
      (footprint "SamacSys:RESC1608X50N")
      (description "Resistor")
      (fields
        (field (name "MANUFACTURER_PART_NUMBER") "CRCW060349R9FKEA")
        (field (name "MOUSER PART NUMBER") "71-CRCW0603-49.9-E3")
      )
      (libsource (lib "*") (part "CRCW060349R9FKEA"))
    )
    (comp (ref "R37")
      (value "49.9")
      (footprint "SamacSys:RESC1608X50N")
      (description "Resistor")
      (fields
        (field (name "MANUFACTURER_PART_NUMBER") "CRCW060349R9FKEA")
        (field (name "MOUSER PART NUMBER") "71-CRCW0603-49.9-E3")
      )
      (libsource (lib "*") (part "CRCW060349R9FKEA"))
    )
    (comp (ref "R50")
      (value "CRCW060310K0FKEA")
      (footprint "SamacSys:RESC1608X50N")
      (description "Resistor")
      (fields
        (field (name "MOUSER PART NUMBER") "71-CRCW0603-10K-E3")
        (field (name "RS PART NUMBER") "6789667P")
      )
      (libsource (lib "*") (part "CRCW060310K0FKEA"))
    )
    (comp (ref "R51")
      (value "10")
      (footprint "SamacSys:RESC1608X50N")
      (description "Resistor")
      (fields
        (field (name "MANUFACTURER_PART_NUMBER") "CRCW060310R0FKEA")
        (field (name "MOUSER PART NUMBER") "71-CRCW0603-10-E3")
      )
      (libsource (lib "*") (part "CRCW060310R0FKEA"))
    )
    (comp (ref "R52")
      (value "CRCW2512200RJNEG")
      (footprint "SamacSys:RESC6332X70N")
      (description "Resistor")
      (fields
        (field (name "MOUSER PART NUMBER") "71-CRCW2512J-200-E3")
        (field (name "RS PART NUMBER") "8429493")
      )
      (libsource (lib "") (part "CRCW2512200RJNEG_1"))
    )
    (comp (ref "R53")
      (value "CRCW060310K0FKEA")
      (footprint "SamacSys:RESC1608X50N")
      (description "Resistor")
      (fields
        (field (name "MOUSER PART NUMBER") "71-CRCW0603-10K-E3")
        (field (name "RS PART NUMBER") "6789667P")
      )
      (libsource (lib "*") (part "CRCW060310K0FKEA"))
    )
    (comp (ref "R54")
      (value "CRCW2512200RJNEG")
      (footprint "SamacSys:RESC6332X70N")
      (description "Resistor")
      (fields
        (field (name "MOUSER PART NUMBER") "71-CRCW2512J-200-E3")
        (field (name "RS PART NUMBER") "8429493")
      )
      (libsource (lib "*") (part "CRCW2512200RJNEG"))
    )
    (comp (ref "R55")
      (value "10")
      (footprint "SamacSys:RESC1608X50N")
      (description "Resistor")
      (fields
        (field (name "MANUFACTURER_PART_NUMBER") "CRCW060310R0FKEA")
        (field (name "MOUSER PART NUMBER") "71-CRCW0603-10-E3")
      )
      (libsource (lib "*") (part "CRCW060310R0FKEA"))
    )
    (comp (ref "R56")
      (value "CRCW060310K0FKEA")
      (footprint "SamacSys:RESC1608X50N")
      (description "Resistor")
      (fields
        (field (name "MOUSER PART NUMBER") "71-CRCW0603-10K-E3")
        (field (name "RS PART NUMBER") "6789667P")
      )
      (libsource (lib "*") (part "CRCW060310K0FKEA"))
    )
    (comp (ref "R57")
      (value "CRCW06030000Z0EA")
      (footprint "SamacSys:RESC1608X50N")
      (description "Resistor")
      (fields
        (field (name "MOUSER PART NUMBER") "71-CRCW0603-0-E3")
        (field (name "RS PART NUMBER") "2508364822")
      )
      (libsource (lib "") (part "CRCW06030000Z0EA_1"))
    )
    (comp (ref "R58")
      (value "10")
      (footprint "SamacSys:RESC1608X50N")
      (description "Resistor")
      (fields
        (field (name "MANUFACTURER_PART_NUMBER") "CRCW060310R0FKEA")
        (field (name "MOUSER PART NUMBER") "71-CRCW0603-10-E3")
      )
      (libsource (lib "*") (part "CRCW060310R0FKEA"))
    )
    (comp (ref "R59")
      (value "CRCW06030000Z0EA")
      (footprint "SamacSys:RESC1608X50N")
      (description "Resistor")
      (fields
        (field (name "MOUSER PART NUMBER") "71-CRCW0603-0-E3")
        (field (name "RS PART NUMBER") "2508364822")
      )
      (libsource (lib "*") (part "CRCW06030000Z0EA"))
    )
    (comp (ref "R60")
      (value "CRCW06032K00FKEA")
      (footprint "SamacSys:RESC1608X50N")
      (description "Resistor")
      (fields
        (field (name "MOUSER PART NUMBER") "71-CRCW0603-2.0K-E3")
        (field (name "RS PART NUMBER") "2508364901")
      )
      (libsource (lib "") (part "CRCW06032K00FKEA_1"))
    )
    (comp (ref "R61")
      (value "RC0603FR-071RL")
      (footprint "SamacSys:RESC1608X55N")
      (description "Resistor")
      (fields
        (field (name "MOUSER PART NUMBER") "603-RC0603FR-071RL")
        (field (name "RS PART NUMBER") "5048978")
      )
      (libsource (lib "*") (part "RC0603FR-071RL"))
    )
    (comp (ref "R62")
      (value "RC0603FR-071RL")
      (footprint "SamacSys:RESC1608X55N")
      (description "Resistor")
      (fields
        (field (name "MOUSER PART NUMBER") "603-RC0603FR-071RL")
        (field (name "RS PART NUMBER") "5048978")
      )
      (libsource (lib "*") (part "RC0603FR-071RL"))
    )
    (comp (ref "R63")
      (value "CRCW060310K0FKEA")
      (footprint "SamacSys:RESC1608X50N")
      (description "Resistor")
      (fields
        (field (name "MOUSER PART NUMBER") "71-CRCW0603-10K-E3")
        (field (name "RS PART NUMBER") "6789667P")
      )
      (libsource (lib "*") (part "CRCW060310K0FKEA"))
    )
    (comp (ref "R64")
      (value "ERJ-3RQFR39V")
      (footprint "SamacSys:RESC1608X60N")
      (description "Resistor")
      (fields (field (name "MOUSER PART NUMBER") "667-ERJ-3RQFR39V"))
      (libsource (lib "*") (part "ERJ-3RQFR39V"))
    )
    (comp (ref "R65")
      (value "10")
      (footprint "SamacSys:RESC1608X50N")
      (description "Resistor")
      (fields
        (field (name "MANUFACTURER_PART_NUMBER") "CRCW060310R0FKEA")
        (field (name "MOUSER PART NUMBER") "71-CRCW0603-10-E3")
      )
      (libsource (lib "*") (part "CRCW060310R0FKEA"))
    )
    (comp (ref "R66")
      (value "CRCW060310K0FKEA")
      (footprint "SamacSys:RESC1608X50N")
      (description "Resistor")
      (fields
        (field (name "MOUSER PART NUMBER") "71-CRCW0603-10K-E3")
        (field (name "RS PART NUMBER") "6789667P")
      )
      (libsource (lib "*") (part "CRCW060310K0FKEA"))
    )
    (comp (ref "R67")
      (value "10")
      (footprint "SamacSys:RESC1608X50N")
      (description "Resistor")
      (fields
        (field (name "MANUFACTURER_PART_NUMBER") "CRCW060310R0FKEA")
        (field (name "MOUSER PART NUMBER") "71-CRCW0603-10-E3")
      )
      (libsource (lib "*") (part "CRCW060310R0FKEA"))
    )
    (comp (ref "R68")
      (value "CRCW060310K0FKEA")
      (footprint "SamacSys:RESC1608X50N")
      (description "Resistor")
      (fields
        (field (name "MOUSER PART NUMBER") "71-CRCW0603-10K-E3")
        (field (name "RS PART NUMBER") "6789667P")
      )
      (libsource (lib "*") (part "CRCW060310K0FKEA"))
    )
    (comp (ref "R69")
      (value "10")
      (footprint "SamacSys:RESC1608X50N")
      (description "Resistor")
      (fields
        (field (name "MANUFACTURER_PART_NUMBER") "CRCW060310R0FKEA")
        (field (name "MOUSER PART NUMBER") "71-CRCW0603-10-E3")
      )
      (libsource (lib "*") (part "CRCW060310R0FKEA"))
    )
    (comp (ref "R70")
      (value "CRCW060310K0FKEA")
      (footprint "SamacSys:RESC1608X50N")
      (description "Resistor")
      (fields
        (field (name "MOUSER PART NUMBER") "71-CRCW0603-10K-E3")
        (field (name "RS PART NUMBER") "6789667P")
      )
      (libsource (lib "*") (part "CRCW060310K0FKEA"))
    )
    (comp (ref "R71")
      (value "10")
      (footprint "SamacSys:RESC1608X50N")
      (description "Resistor")
      (fields
        (field (name "MANUFACTURER_PART_NUMBER") "CRCW060310R0FKEA")
        (field (name "MOUSER PART NUMBER") "71-CRCW0603-10-E3")
      )
      (libsource (lib "*") (part "CRCW060310R0FKEA"))
    )
    (comp (ref "R72")
      (value "CRCW060310K0FKEA")
      (footprint "SamacSys:RESC1608X50N")
      (description "Resistor")
      (fields
        (field (name "MOUSER PART NUMBER") "71-CRCW0603-10K-E3")
        (field (name "RS PART NUMBER") "6789667P")
      )
      (libsource (lib "*") (part "CRCW060310K0FKEA"))
    )
    (comp (ref "R73")
      (value "10")
      (footprint "SamacSys:RESC1608X50N")
      (description "Resistor")
      (fields
        (field (name "MANUFACTURER_PART_NUMBER") "CRCW060310R0FKEA")
        (field (name "MOUSER PART NUMBER") "71-CRCW0603-10-E3")
      )
      (libsource (lib "*") (part "CRCW060310R0FKEA"))
    )
    (comp (ref "R74")
      (value "1k")
      (footprint "SamacSys:RESC1608X50N")
      (description "Resistor")
      (fields
        (field (name "MANUFACTURER_PART_NUMBER") "CRCW06031K00FKEA")
        (field (name "MOUSER PART NUMBER") "71-CRCW0603-1.0K-E3")
      )
      (libsource (lib "*") (part "CRCW06031K00FKEA"))
    )
    (comp (ref "R75")
      (value "1k")
      (footprint "SamacSys:RESC1608X50N")
      (description "Resistor")
      (fields
        (field (name "MANUFACTURER_PART_NUMBER") "CRCW06031K00FKEA")
        (field (name "MOUSER PART NUMBER") "71-CRCW0603-1.0K-E3")
      )
      (libsource (lib "") (part "CRCW06031K00FKEA_1"))
    )
    (comp (ref "R76")
      (value "2k")
      (footprint "SamacSys:RESC1608X50N")
      (description "Resistor")
      (fields
        (field (name "MANUFACTURER_PART_NUMBER") "CRCW06032K00FKEA")
        (field (name "MOUSER PART NUMBER") "71-CRCW0603-2.0K-E3")
      )
      (libsource (lib "*") (part "CRCW06032K00FKEA"))
    )
    (comp (ref "R77")
      (value "100k")
      (footprint "SamacSys:RESC1608X55N")
      (description "Resistor")
      (fields
        (field (name "MANUFACTURER_PART_NUMBER") "RC0603FR-07100KL")
        (field (name "MOUSER PART NUMBER") "603-RC0603FR-07100KL")
      )
      (libsource (lib "") (part "RC0603FR-07100KL_1"))
    )
    (comp (ref "R78")
      (value "1k")
      (footprint "SamacSys:RESC1608X50N")
      (description "Resistor")
      (fields
        (field (name "MANUFACTURER_PART_NUMBER") "CRCW06031K00FKEA")
        (field (name "MOUSER PART NUMBER") "71-CRCW0603-1.0K-E3")
      )
      (libsource (lib "") (part "CRCW06031K00FKEA_1"))
    )
    (comp (ref "R79")
      (value "1k")
      (footprint "SamacSys:RESC1608X50N")
      (description "Resistor")
      (fields
        (field (name "MANUFACTURER_PART_NUMBER") "CRCW06031K00FKEA")
        (field (name "MOUSER PART NUMBER") "71-CRCW0603-1.0K-E3")
      )
      (libsource (lib "*") (part "CRCW06031K00FKEA"))
    )
    (comp (ref "R80")
      (value "1k")
      (footprint "SamacSys:RESC1608X50N")
      (description "Resistor")
      (fields
        (field (name "MANUFACTURER_PART_NUMBER") "CRCW06031K00FKEA")
        (field (name "MOUSER PART NUMBER") "71-CRCW0603-1.0K-E3")
      )
      (libsource (lib "") (part "CRCW06031K00FKEA_1"))
    )
    (comp (ref "R81")
      (value "2k")
      (footprint "SamacSys:RESC1608X50N")
      (description "Resistor")
      (fields
        (field (name "MANUFACTURER_PART_NUMBER") "CRCW06032K00FKEA")
        (field (name "MOUSER PART NUMBER") "71-CRCW0603-2.0K-E3")
      )
      (libsource (lib "*") (part "CRCW06032K00FKEA"))
    )
    (comp (ref "R82")
      (value "100k")
      (footprint "SamacSys:RESC1608X55N")
      (description "Resistor")
      (fields
        (field (name "MANUFACTURER_PART_NUMBER") "RC0603FR-07100KL")
        (field (name "MOUSER PART NUMBER") "603-RC0603FR-07100KL")
      )
      (libsource (lib "") (part "RC0603FR-07100KL_1"))
    )
    (comp (ref "R83")
      (value "2k")
      (footprint "SamacSys:RESC1608X50N")
      (description "Resistor")
      (fields
        (field (name "MANUFACTURER_PART_NUMBER") "CRCW06032K00FKEA")
        (field (name "MOUSER PART NUMBER") "71-CRCW0603-2.0K-E3")
      )
      (libsource (lib "*") (part "CRCW06032K00FKEA"))
    )
    (comp (ref "R84")
      (value "1k")
      (footprint "SamacSys:RESC1608X50N")
      (description "Resistor")
      (fields
        (field (name "MANUFACTURER_PART_NUMBER") "CRCW06031K00FKEA")
        (field (name "MOUSER PART NUMBER") "71-CRCW0603-1.0K-E3")
      )
      (libsource (lib "*") (part "CRCW06031K00FKEA"))
    )
    (comp (ref "R85")
      (value "100k")
      (footprint "SamacSys:RESC1608X55N")
      (description "Resistor")
      (fields
        (field (name "MANUFACTURER_PART_NUMBER") "RC0603FR-07100KL")
        (field (name "MOUSER PART NUMBER") "603-RC0603FR-07100KL")
      )
      (libsource (lib "") (part "RC0603FR-07100KL_1"))
    )
    (comp (ref "R86")
      (value "1k")
      (footprint "SamacSys:RESC1608X50N")
      (description "Resistor")
      (fields
        (field (name "MANUFACTURER_PART_NUMBER") "CRCW06031K00FKEA")
        (field (name "MOUSER PART NUMBER") "71-CRCW0603-1.0K-E3")
      )
      (libsource (lib "") (part "CRCW06031K00FKEA_1"))
    )
    (comp (ref "R87")
      (value "1k")
      (footprint "SamacSys:RESC1608X50N")
      (description "Resistor")
      (fields
        (field (name "MANUFACTURER_PART_NUMBER") "CRCW06031K00FKEA")
        (field (name "MOUSER PART NUMBER") "71-CRCW0603-1.0K-E3")
      )
      (libsource (lib "*") (part "CRCW06031K00FKEA"))
    )
    (comp (ref "R88")
      (value "1k")
      (footprint "SamacSys:RESC1608X50N")
      (description "Resistor")
      (fields
        (field (name "MANUFACTURER_PART_NUMBER") "CRCW06031K00FKEA")
        (field (name "MOUSER PART NUMBER") "71-CRCW0603-1.0K-E3")
      )
      (libsource (lib "") (part "CRCW06031K00FKEA_1"))
    )
    (comp (ref "R89")
      (value "2k")
      (footprint "SamacSys:RESC1608X50N")
      (description "Resistor")
      (fields
        (field (name "MANUFACTURER_PART_NUMBER") "CRCW06032K00FKEA")
        (field (name "MOUSER PART NUMBER") "71-CRCW0603-2.0K-E3")
      )
      (libsource (lib "*") (part "CRCW06032K00FKEA"))
    )
    (comp (ref "R90")
      (value "100k")
      (footprint "SamacSys:RESC1608X55N")
      (description "Resistor")
      (fields
        (field (name "MANUFACTURER_PART_NUMBER") "RC0603FR-07100KL")
        (field (name "MOUSER PART NUMBER") "603-RC0603FR-07100KL")
      )
      (libsource (lib "") (part "RC0603FR-07100KL_1"))
    )
    (comp (ref "R91")
      (value "2k")
      (footprint "SamacSys:RESC1608X50N")
      (description "Resistor")
      (fields
        (field (name "MANUFACTURER_PART_NUMBER") "CRCW06032K00FKEA")
        (field (name "MOUSER PART NUMBER") "71-CRCW0603-2.0K-E3")
      )
      (libsource (lib "*") (part "CRCW06032K00FKEA"))
    )
    (comp (ref "R92")
      (value "1k")
      (footprint "SamacSys:RESC1608X50N")
      (description "Resistor")
      (fields
        (field (name "MANUFACTURER_PART_NUMBER") "CRCW06031K00FKEA")
        (field (name "MOUSER PART NUMBER") "71-CRCW0603-1.0K-E3")
      )
      (libsource (lib "*") (part "CRCW06031K00FKEA"))
    )
    (comp (ref "R93")
      (value "100k")
      (footprint "SamacSys:RESC1608X55N")
      (description "Resistor")
      (fields
        (field (name "MANUFACTURER_PART_NUMBER") "RC0603FR-07100KL")
        (field (name "MOUSER PART NUMBER") "603-RC0603FR-07100KL")
      )
      (libsource (lib "") (part "RC0603FR-07100KL_1"))
    )
    (comp (ref "R94")
      (value "1k")
      (footprint "SamacSys:RESC1608X50N")
      (description "Resistor")
      (fields
        (field (name "MANUFACTURER_PART_NUMBER") "CRCW06031K00FKEA")
        (field (name "MOUSER PART NUMBER") "71-CRCW0603-1.0K-E3")
      )
      (libsource (lib "") (part "CRCW06031K00FKEA_1"))
    )
    (comp (ref "R95")
      (value "1k")
      (footprint "SamacSys:RESC1608X50N")
      (description "Resistor")
      (fields
        (field (name "MANUFACTURER_PART_NUMBER") "CRCW06031K00FKEA")
        (field (name "MOUSER PART NUMBER") "71-CRCW0603-1.0K-E3")
      )
      (libsource (lib "*") (part "CRCW06031K00FKEA"))
    )
    (comp (ref "R96")
      (value "1k")
      (footprint "SamacSys:RESC1608X50N")
      (description "Resistor")
      (fields
        (field (name "MANUFACTURER_PART_NUMBER") "CRCW06031K00FKEA")
        (field (name "MOUSER PART NUMBER") "71-CRCW0603-1.0K-E3")
      )
      (libsource (lib "") (part "CRCW06031K00FKEA_1"))
    )
    (comp (ref "R97")
      (value "2k")
      (footprint "SamacSys:RESC1608X50N")
      (description "Resistor")
      (fields
        (field (name "MANUFACTURER_PART_NUMBER") "CRCW06032K00FKEA")
        (field (name "MOUSER PART NUMBER") "71-CRCW0603-2.0K-E3")
      )
      (libsource (lib "*") (part "CRCW06032K00FKEA"))
    )
    (comp (ref "R98")
      (value "100k")
      (footprint "SamacSys:RESC1608X55N")
      (description "Resistor")
      (fields
        (field (name "MANUFACTURER_PART_NUMBER") "RC0603FR-07100KL")
        (field (name "MOUSER PART NUMBER") "603-RC0603FR-07100KL")
      )
      (libsource (lib "") (part "RC0603FR-07100KL_1"))
    )
    (comp (ref "R99")
      (value "2k")
      (footprint "SamacSys:RESC1608X50N")
      (description "Resistor")
      (fields
        (field (name "MANUFACTURER_PART_NUMBER") "CRCW06032K00FKEA")
        (field (name "MOUSER PART NUMBER") "71-CRCW0603-2.0K-E3")
      )
      (libsource (lib "*") (part "CRCW06032K00FKEA"))
    )
    (comp (ref "R100")
      (value "1k")
      (footprint "SamacSys:RESC1608X50N")
      (description "Resistor")
      (fields
        (field (name "MANUFACTURER_PART_NUMBER") "CRCW06031K00FKEA")
        (field (name "MOUSER PART NUMBER") "71-CRCW0603-1.0K-E3")
      )
      (libsource (lib "*") (part "CRCW06031K00FKEA"))
    )
    (comp (ref "R101")
      (value "100k")
      (footprint "SamacSys:RESC1608X55N")
      (description "Resistor")
      (fields
        (field (name "MANUFACTURER_PART_NUMBER") "RC0603FR-07100KL")
        (field (name "MOUSER PART NUMBER") "603-RC0603FR-07100KL")
      )
      (libsource (lib "") (part "RC0603FR-07100KL_1"))
    )
    (comp (ref "R102")
      (value "1k")
      (footprint "SamacSys:RESC1608X50N")
      (description "Resistor")
      (fields
        (field (name "MANUFACTURER_PART_NUMBER") "CRCW06031K00FKEA")
        (field (name "MOUSER PART NUMBER") "71-CRCW0603-1.0K-E3")
      )
      (libsource (lib "") (part "CRCW06031K00FKEA_1"))
    )
    (comp (ref "R103")
      (value "1k")
      (footprint "SamacSys:RESC1608X50N")
      (description "Resistor")
      (fields
        (field (name "MANUFACTURER_PART_NUMBER") "CRCW06031K00FKEA")
        (field (name "MOUSER PART NUMBER") "71-CRCW0603-1.0K-E3")
      )
      (libsource (lib "*") (part "CRCW06031K00FKEA"))
    )
    (comp (ref "R104")
      (value "1k")
      (footprint "SamacSys:RESC1608X50N")
      (description "Resistor")
      (fields
        (field (name "MANUFACTURER_PART_NUMBER") "CRCW06031K00FKEA")
        (field (name "MOUSER PART NUMBER") "71-CRCW0603-1.0K-E3")
      )
      (libsource (lib "") (part "CRCW06031K00FKEA_1"))
    )
    (comp (ref "R105")
      (value "2k")
      (footprint "SamacSys:RESC1608X50N")
      (description "Resistor")
      (fields
        (field (name "MANUFACTURER_PART_NUMBER") "CRCW06032K00FKEA")
        (field (name "MOUSER PART NUMBER") "71-CRCW0603-2.0K-E3")
      )
      (libsource (lib "*") (part "CRCW06032K00FKEA"))
    )
    (comp (ref "R106")
      (value "100k")
      (footprint "SamacSys:RESC1608X55N")
      (description "Resistor")
      (fields
        (field (name "MANUFACTURER_PART_NUMBER") "RC0603FR-07100KL")
        (field (name "MOUSER PART NUMBER") "603-RC0603FR-07100KL")
      )
      (libsource (lib "") (part "RC0603FR-07100KL_1"))
    )
    (comp (ref "R107")
      (value "2k")
      (footprint "SamacSys:RESC1608X50N")
      (description "Resistor")
      (fields
        (field (name "MANUFACTURER_PART_NUMBER") "CRCW06032K00FKEA")
        (field (name "MOUSER PART NUMBER") "71-CRCW0603-2.0K-E3")
      )
      (libsource (lib "*") (part "CRCW06032K00FKEA"))
    )
    (comp (ref "R108")
      (value "1k")
      (footprint "SamacSys:RESC1608X50N")
      (description "Resistor")
      (fields
        (field (name "MANUFACTURER_PART_NUMBER") "CRCW06031K00FKEA")
        (field (name "MOUSER PART NUMBER") "71-CRCW0603-1.0K-E3")
      )
      (libsource (lib "*") (part "CRCW06031K00FKEA"))
    )
    (comp (ref "R109")
      (value "100k")
      (footprint "SamacSys:RESC1608X55N")
      (description "Resistor")
      (fields
        (field (name "MANUFACTURER_PART_NUMBER") "RC0603FR-07100KL")
        (field (name "MOUSER PART NUMBER") "603-RC0603FR-07100KL")
      )
      (libsource (lib "") (part "RC0603FR-07100KL_1"))
    )
    (comp (ref "R110")
      (value "1k")
      (footprint "SamacSys:RESC1608X50N")
      (description "Resistor")
      (fields
        (field (name "MANUFACTURER_PART_NUMBER") "CRCW06031K00FKEA")
        (field (name "MOUSER PART NUMBER") "71-CRCW0603-1.0K-E3")
      )
      (libsource (lib "") (part "CRCW06031K00FKEA_1"))
    )
    (comp (ref "R111")
      (value "1k")
      (footprint "SamacSys:RESC1608X50N")
      (description "Resistor")
      (fields
        (field (name "MANUFACTURER_PART_NUMBER") "CRCW06031K00FKEA")
        (field (name "MOUSER PART NUMBER") "71-CRCW0603-1.0K-E3")
      )
      (libsource (lib "*") (part "CRCW06031K00FKEA"))
    )
    (comp (ref "R112")
      (value "1k")
      (footprint "SamacSys:RESC1608X50N")
      (description "Resistor")
      (fields
        (field (name "MANUFACTURER_PART_NUMBER") "CRCW06031K00FKEA")
        (field (name "MOUSER PART NUMBER") "71-CRCW0603-1.0K-E3")
      )
      (libsource (lib "") (part "CRCW06031K00FKEA_1"))
    )
    (comp (ref "R113")
      (value "2k")
      (footprint "SamacSys:RESC1608X50N")
      (description "Resistor")
      (fields
        (field (name "MANUFACTURER_PART_NUMBER") "CRCW06032K00FKEA")
        (field (name "MOUSER PART NUMBER") "71-CRCW0603-2.0K-E3")
      )
      (libsource (lib "*") (part "CRCW06032K00FKEA"))
    )
    (comp (ref "R114")
      (value "100k")
      (footprint "SamacSys:RESC1608X55N")
      (description "Resistor")
      (fields
        (field (name "MANUFACTURER_PART_NUMBER") "RC0603FR-07100KL")
        (field (name "MOUSER PART NUMBER") "603-RC0603FR-07100KL")
      )
      (libsource (lib "") (part "RC0603FR-07100KL_1"))
    )
    (comp (ref "R115")
      (value "2k")
      (footprint "SamacSys:RESC1608X50N")
      (description "Resistor")
      (fields
        (field (name "MANUFACTURER_PART_NUMBER") "CRCW06032K00FKEA")
        (field (name "MOUSER PART NUMBER") "71-CRCW0603-2.0K-E3")
      )
      (libsource (lib "*") (part "CRCW06032K00FKEA"))
    )
    (comp (ref "R116")
      (value "1k")
      (footprint "SamacSys:RESC1608X50N")
      (description "Resistor")
      (fields
        (field (name "MANUFACTURER_PART_NUMBER") "CRCW06031K00FKEA")
        (field (name "MOUSER PART NUMBER") "71-CRCW0603-1.0K-E3")
      )
      (libsource (lib "*") (part "CRCW06031K00FKEA"))
    )
    (comp (ref "R117")
      (value "100k")
      (footprint "SamacSys:RESC1608X55N")
      (description "Resistor")
      (fields
        (field (name "MANUFACTURER_PART_NUMBER") "RC0603FR-07100KL")
        (field (name "MOUSER PART NUMBER") "603-RC0603FR-07100KL")
      )
      (libsource (lib "") (part "RC0603FR-07100KL_1"))
    )
    (comp (ref "R118")
      (value "1k")
      (footprint "SamacSys:RESC1608X50N")
      (description "Resistor")
      (fields
        (field (name "MANUFACTURER_PART_NUMBER") "CRCW06031K00FKEA")
        (field (name "MOUSER PART NUMBER") "71-CRCW0603-1.0K-E3")
      )
      (libsource (lib "") (part "CRCW06031K00FKEA_1"))
    )
    (comp (ref "R119")
      (value "1k")
      (footprint "SamacSys:RESC1608X50N")
      (description "Resistor")
      (fields
        (field (name "MANUFACTURER_PART_NUMBER") "CRCW06031K00FKEA")
        (field (name "MOUSER PART NUMBER") "71-CRCW0603-1.0K-E3")
      )
      (libsource (lib "*") (part "CRCW06031K00FKEA"))
    )
    (comp (ref "R120")
      (value "1k")
      (footprint "SamacSys:RESC1608X50N")
      (description "Resistor")
      (fields
        (field (name "MANUFACTURER_PART_NUMBER") "CRCW06031K00FKEA")
        (field (name "MOUSER PART NUMBER") "71-CRCW0603-1.0K-E3")
      )
      (libsource (lib "") (part "CRCW06031K00FKEA_1"))
    )
    (comp (ref "R121")
      (value "2k")
      (footprint "SamacSys:RESC1608X50N")
      (description "Resistor")
      (fields
        (field (name "MANUFACTURER_PART_NUMBER") "CRCW06032K00FKEA")
        (field (name "MOUSER PART NUMBER") "71-CRCW0603-2.0K-E3")
      )
      (libsource (lib "*") (part "CRCW06032K00FKEA"))
    )
    (comp (ref "R122")
      (value "100k")
      (footprint "SamacSys:RESC1608X55N")
      (description "Resistor")
      (fields
        (field (name "MANUFACTURER_PART_NUMBER") "RC0603FR-07100KL")
        (field (name "MOUSER PART NUMBER") "603-RC0603FR-07100KL")
      )
      (libsource (lib "") (part "RC0603FR-07100KL_1"))
    )
    (comp (ref "R123")
      (value "2k")
      (footprint "SamacSys:RESC1608X50N")
      (description "Resistor")
      (fields
        (field (name "MANUFACTURER_PART_NUMBER") "CRCW06032K00FKEA")
        (field (name "MOUSER PART NUMBER") "71-CRCW0603-2.0K-E3")
      )
      (libsource (lib "*") (part "CRCW06032K00FKEA"))
    )
    (comp (ref "R124")
      (value "1k")
      (footprint "SamacSys:RESC1608X50N")
      (description "Resistor")
      (fields
        (field (name "MANUFACTURER_PART_NUMBER") "CRCW06031K00FKEA")
        (field (name "MOUSER PART NUMBER") "71-CRCW0603-1.0K-E3")
      )
      (libsource (lib "*") (part "CRCW06031K00FKEA"))
    )
    (comp (ref "R125")
      (value "100k")
      (footprint "SamacSys:RESC1608X55N")
      (description "Resistor")
      (fields
        (field (name "MANUFACTURER_PART_NUMBER") "RC0603FR-07100KL")
        (field (name "MOUSER PART NUMBER") "603-RC0603FR-07100KL")
      )
      (libsource (lib "") (part "RC0603FR-07100KL_1"))
    )
    (comp (ref "R126")
      (value "1k")
      (footprint "SamacSys:RESC1608X50N")
      (description "Resistor")
      (fields
        (field (name "MANUFACTURER_PART_NUMBER") "CRCW06031K00FKEA")
        (field (name "MOUSER PART NUMBER") "71-CRCW0603-1.0K-E3")
      )
      (libsource (lib "") (part "CRCW06031K00FKEA_1"))
    )
    (comp (ref "R127")
      (value "1k")
      (footprint "SamacSys:RESC1608X50N")
      (description "Resistor")
      (fields
        (field (name "MANUFACTURER_PART_NUMBER") "CRCW06031K00FKEA")
        (field (name "MOUSER PART NUMBER") "71-CRCW0603-1.0K-E3")
      )
      (libsource (lib "*") (part "CRCW06031K00FKEA"))
    )
    (comp (ref "R128")
      (value "1k")
      (footprint "SamacSys:RESC1608X50N")
      (description "Resistor")
      (fields
        (field (name "MANUFACTURER_PART_NUMBER") "CRCW06031K00FKEA")
        (field (name "MOUSER PART NUMBER") "71-CRCW0603-1.0K-E3")
      )
      (libsource (lib "") (part "CRCW06031K00FKEA_1"))
    )
    (comp (ref "R129")
      (value "2k")
      (footprint "SamacSys:RESC1608X50N")
      (description "Resistor")
      (fields
        (field (name "MANUFACTURER_PART_NUMBER") "CRCW06032K00FKEA")
        (field (name "MOUSER PART NUMBER") "71-CRCW0603-2.0K-E3")
      )
      (libsource (lib "*") (part "CRCW06032K00FKEA"))
    )
    (comp (ref "R130")
      (value "100k")
      (footprint "SamacSys:RESC1608X55N")
      (description "Resistor")
      (fields
        (field (name "MANUFACTURER_PART_NUMBER") "RC0603FR-07100KL")
        (field (name "MOUSER PART NUMBER") "603-RC0603FR-07100KL")
      )
      (libsource (lib "") (part "RC0603FR-07100KL_1"))
    )
    (comp (ref "R131")
      (value "2k")
      (footprint "SamacSys:RESC1608X50N")
      (description "Resistor")
      (fields
        (field (name "MANUFACTURER_PART_NUMBER") "CRCW06032K00FKEA")
        (field (name "MOUSER PART NUMBER") "71-CRCW0603-2.0K-E3")
      )
      (libsource (lib "*") (part "CRCW06032K00FKEA"))
    )
    (comp (ref "R132")
      (value "1k")
      (footprint "SamacSys:RESC1608X50N")
      (description "Resistor")
      (fields
        (field (name "MANUFACTURER_PART_NUMBER") "CRCW06031K00FKEA")
        (field (name "MOUSER PART NUMBER") "71-CRCW0603-1.0K-E3")
      )
      (libsource (lib "*") (part "CRCW06031K00FKEA"))
    )
    (comp (ref "R133")
      (value "100k")
      (footprint "SamacSys:RESC1608X55N")
      (description "Resistor")
      (fields
        (field (name "MANUFACTURER_PART_NUMBER") "RC0603FR-07100KL")
        (field (name "MOUSER PART NUMBER") "603-RC0603FR-07100KL")
      )
      (libsource (lib "") (part "RC0603FR-07100KL_1"))
    )
    (comp (ref "R134")
      (value "1k")
      (footprint "SamacSys:RESC1608X50N")
      (description "Resistor")
      (fields
        (field (name "MANUFACTURER_PART_NUMBER") "CRCW06031K00FKEA")
        (field (name "MOUSER PART NUMBER") "71-CRCW0603-1.0K-E3")
      )
      (libsource (lib "") (part "CRCW06031K00FKEA_1"))
    )
    (comp (ref "R135")
      (value "1k")
      (footprint "SamacSys:RESC1608X50N")
      (description "Resistor")
      (fields
        (field (name "MANUFACTURER_PART_NUMBER") "CRCW06031K00FKEA")
        (field (name "MOUSER PART NUMBER") "71-CRCW0603-1.0K-E3")
      )
      (libsource (lib "*") (part "CRCW06031K00FKEA"))
    )
    (comp (ref "R136")
      (value "2k")
      (footprint "SamacSys:RESC1608X50N")
      (description "Resistor")
      (fields
        (field (name "MANUFACTURER_PART_NUMBER") "CRCW06032K00FKEA")
        (field (name "MOUSER PART NUMBER") "71-CRCW0603-2.0K-E3")
      )
      (libsource (lib "*") (part "CRCW06032K00FKEA"))
    )
    (comp (ref "R137")
      (value "100k")
      (footprint "SamacSys:RESC1608X55N")
      (description "Resistor")
      (fields
        (field (name "MANUFACTURER_PART_NUMBER") "RC0603FR-07100KL")
        (field (name "MOUSER PART NUMBER") "603-RC0603FR-07100KL")
      )
      (libsource (lib "") (part "RC0603FR-07100KL_1"))
    )
    (comp (ref "R138")
      (value "1k")
      (footprint "SamacSys:RESC1608X50N")
      (description "Resistor")
      (fields
        (field (name "MANUFACTURER_PART_NUMBER") "CRCW06031K00FKEA")
        (field (name "MOUSER PART NUMBER") "71-CRCW0603-1.0K-E3")
      )
      (libsource (lib "*") (part "CRCW06031K00FKEA"))
    )
    (comp (ref "SW2")
      (value "204-221ST")
      (footprint "SamacSys:204-221ST")
      (description "Switch")
      (fields (field (name "MOUSER PART NUMBER") "774-204221ST"))
      (libsource (lib "*") (part "204-221ST"))
    )
    (comp (ref "T1")
      (value "744242471")
      (footprint "SamacSys:744242471")
      (description "Inductor")
      (fields (field (name "MOUSER PART NUMBER") "710-744242471") (field (name "RS PART NUMBER") "9040274P"))
      (libsource (lib "*") (part "744242471"))
    )
    (comp (ref "T2")
      (value "744242471")
      (footprint "SamacSys:744242471")
      (description "Inductor")
      (fields (field (name "MOUSER PART NUMBER") "710-744242471") (field (name "RS PART NUMBER") "9040274P"))
      (libsource (lib "*") (part "744242471"))
    )
    (comp (ref "T3")
      (value "744242471")
      (footprint "SamacSys:744242471")
      (description "Inductor")
      (fields (field (name "MOUSER PART NUMBER") "710-744242471") (field (name "RS PART NUMBER") "9040274P"))
      (libsource (lib "*") (part "744242471"))
    )
    (comp (ref "T4")
      (value "744242471")
      (footprint "SamacSys:744242471")
      (description "Inductor")
      (fields (field (name "MOUSER PART NUMBER") "710-744242471") (field (name "RS PART NUMBER") "9040274P"))
      (libsource (lib "*") (part "744242471"))
    )
    (comp (ref "T5")
      (value "ACT45B-101-2P-TL003")
      (footprint "SamacSys:TDK_ACT45B_2")
      (description "Filter")
      (fields (field (name "MOUSER PART NUMBER") "810-ACT45B1012PTL003"))
      (libsource (lib "*") (part "ACT45B-101-2P-TL003"))
    )
    (comp (ref "T6")
      (value "ACT45B-101-2P-TL003")
      (footprint "SamacSys:TDK_ACT45B_2")
      (description "Filter")
      (fields (field (name "MOUSER PART NUMBER") "810-ACT45B1012PTL003"))
      (libsource (lib "*") (part "ACT45B-101-2P-TL003"))
    )
    (comp (ref "T7")
      (value "ACT45B-101-2P-TL003")
      (footprint "SamacSys:TDK_ACT45B_2")
      (description "Filter")
      (fields (field (name "MOUSER PART NUMBER") "810-ACT45B1012PTL003"))
      (libsource (lib "*") (part "ACT45B-101-2P-TL003"))
    )
    (comp (ref "T8")
      (value "ACT45B-101-2P-TL003")
      (footprint "SamacSys:TDK_ACT45B_2")
      (description "Filter")
      (fields (field (name "MOUSER PART NUMBER") "810-ACT45B1012PTL003"))
      (libsource (lib "*") (part "ACT45B-101-2P-TL003"))
    )
    (comp (ref "U1")
      (value "BQ76PL455ATPFCRQ1")
      (footprint "SamacSys:QFP50P1400X1400X120-80N")
      (description "Integrated Circuit")
      (fields (field (name "MOUSER PART NUMBER") "595-Q76PL455ATPFCRQ1"))
      (libsource (lib "*") (part "BQ76PL455ATPFCRQ1"))
    )
    (comp (ref "U2")
      (value "NC7SZ04M5X")
      (footprint "SamacSys:SOT95P280X145-5N")
      (description "Integrated Circuit")
      (fields (field (name "MOUSER PART NUMBER") "512-NC7SZ04M5X") (field (name "RS PART NUMBER") "6709797P"))
      (libsource (lib "*") (part "NC7SZ04M5X"))
    )
    (comp (ref "Z1")
      (value "6.2V")
      (footprint "SamacSys:SOD3716X145N")
      (description "Zener Diode")
      (fields
        (field (name "MANUFACTURER_PART_NUMBER") "DDZ6V2B-7")
        (field (name "MOUSER PART NUMBER") "621-DDZ6V2B-7")
      )
      (libsource (lib "*") (part "DDZ6V2B-7"))
    )
    (comp (ref "Z2")
      (value "6.2V")
      (footprint "SamacSys:SOD3716X145N")
      (description "Zener Diode")
      (fields
        (field (name "MANUFACTURER_PART_NUMBER") "DDZ6V2B-7")
        (field (name "MOUSER PART NUMBER") "621-DDZ6V2B-7")
      )
      (libsource (lib "*") (part "DDZ6V2B-7"))
    )
    (comp (ref "Z3")
      (value "6.2V")
      (footprint "SamacSys:SOD3716X145N")
      (description "Zener Diode")
      (fields
        (field (name "MANUFACTURER_PART_NUMBER") "DDZ6V2B-7")
        (field (name "MOUSER PART NUMBER") "621-DDZ6V2B-7")
      )
      (libsource (lib "*") (part "DDZ6V2B-7"))
    )
    (comp (ref "Z4")
      (value "6.2V")
      (footprint "SamacSys:SOD3716X145N")
      (description "Zener Diode")
      (fields
        (field (name "MANUFACTURER_PART_NUMBER") "DDZ6V2B-7")
        (field (name "MOUSER PART NUMBER") "621-DDZ6V2B-7")
      )
      (libsource (lib "*") (part "DDZ6V2B-7"))
    )
    (comp (ref "Z5")
      (value "6.2V")
      (footprint "SamacSys:SOD3716X145N")
      (description "Zener Diode")
      (fields
        (field (name "MANUFACTURER_PART_NUMBER") "DDZ6V2B-7")
        (field (name "MOUSER PART NUMBER") "621-DDZ6V2B-7")
      )
      (libsource (lib "*") (part "DDZ6V2B-7"))
    )
    (comp (ref "Z6")
      (value "6.2V")
      (footprint "SamacSys:SOD3716X145N")
      (description "Zener Diode")
      (fields
        (field (name "MANUFACTURER_PART_NUMBER") "DDZ6V2B-7")
        (field (name "MOUSER PART NUMBER") "621-DDZ6V2B-7")
      )
      (libsource (lib "*") (part "DDZ6V2B-7"))
    )
    (comp (ref "Z7")
      (value "6.2V")
      (footprint "SamacSys:SOD3716X145N")
      (description "Zener Diode")
      (fields
        (field (name "MANUFACTURER_PART_NUMBER") "DDZ6V2B-7")
        (field (name "MOUSER PART NUMBER") "621-DDZ6V2B-7")
      )
      (libsource (lib "*") (part "DDZ6V2B-7"))
    )
    (comp (ref "Z8")
      (value "6.2V")
      (footprint "SamacSys:SOD3716X145N")
      (description "Zener Diode")
      (fields
        (field (name "MANUFACTURER_PART_NUMBER") "DDZ6V2B-7")
        (field (name "MOUSER PART NUMBER") "621-DDZ6V2B-7")
      )
      (libsource (lib "*") (part "DDZ6V2B-7"))
    )
    (comp (ref "Z9")
      (value "6.2V")
      (footprint "SamacSys:SOD3716X145N")
      (description "Zener Diode")
      (fields
        (field (name "MANUFACTURER_PART_NUMBER") "DDZ6V2B-7")
        (field (name "MOUSER PART NUMBER") "621-DDZ6V2B-7")
      )
      (libsource (lib "*") (part "DDZ6V2B-7"))
    )
    (comp (ref "Z10")
      (value "6.2V")
      (footprint "SamacSys:SOD3716X145N")
      (description "Zener Diode")
      (fields
        (field (name "MANUFACTURER_PART_NUMBER") "DDZ6V2B-7")
        (field (name "MOUSER PART NUMBER") "621-DDZ6V2B-7")
      )
      (libsource (lib "*") (part "DDZ6V2B-7"))
    )
    (comp (ref "Z11")
      (value "6.2V")
      (footprint "SamacSys:SOD3716X145N")
      (description "Zener Diode")
      (fields
        (field (name "MANUFACTURER_PART_NUMBER") "DDZ6V2B-7")
        (field (name "MOUSER PART NUMBER") "621-DDZ6V2B-7")
      )
      (libsource (lib "*") (part "DDZ6V2B-7"))
    )
    (comp (ref "Z12")
      (value "6.2V")
      (footprint "SamacSys:SOD3716X145N")
      (description "Zener Diode")
      (fields
        (field (name "MANUFACTURER_PART_NUMBER") "DDZ6V2B-7")
        (field (name "MOUSER PART NUMBER") "621-DDZ6V2B-7")
      )
      (libsource (lib "*") (part "DDZ6V2B-7"))
    )
    (comp (ref "Z13")
      (value "6.2V")
      (footprint "SamacSys:SOD3716X145N")
      (description "Zener Diode")
      (fields
        (field (name "MANUFACTURER_PART_NUMBER") "DDZ6V2B-7")
        (field (name "MOUSER PART NUMBER") "621-DDZ6V2B-7")
      )
      (libsource (lib "*") (part "DDZ6V2B-7"))
    )
    (comp (ref "Z14")
      (value "6.2V")
      (footprint "SamacSys:SOD3716X145N")
      (description "Zener Diode")
      (fields
        (field (name "MANUFACTURER_PART_NUMBER") "DDZ6V2B-7")
        (field (name "MOUSER PART NUMBER") "621-DDZ6V2B-7")
      )
      (libsource (lib "*") (part "DDZ6V2B-7"))
    )
    (comp (ref "Z15")
      (value "6.2V")
      (footprint "SamacSys:SOD3716X145N")
      (description "Zener Diode")
      (fields
        (field (name "MANUFACTURER_PART_NUMBER") "DDZ6V2B-7")
        (field (name "MOUSER PART NUMBER") "621-DDZ6V2B-7")
      )
      (libsource (lib "*") (part "DDZ6V2B-7"))
    )
    (comp (ref "Z16")
      (value "6.2V")
      (footprint "SamacSys:SOD3716X145N")
      (description "Zener Diode")
      (fields
        (field (name "MANUFACTURER_PART_NUMBER") "DDZ6V2B-7")
        (field (name "MOUSER PART NUMBER") "621-DDZ6V2B-7")
      )
      (libsource (lib "*") (part "DDZ6V2B-7"))
    )
    (comp (ref "Z19")
      (value "SMAJ90A")
      (footprint "SamacSys:DIOM5026X229N")
      (description "Diode")
      (fields (field (name "MOUSER PART NUMBER") "576-SMAJ90A"))
      (libsource (lib "*") (part "SMAJ90A"))
    )
    (comp (ref "Z20")
      (value "PESD5V0U1UA,115")
      (footprint "SamacSys:SOD2512X110N")
      (description "Diode")
      (fields
        (field (name "MOUSER PART NUMBER") "771-PESD5V0U1UA-T/R")
        (field (name "RS PART NUMBER") "8166751P")
      )
      (libsource (lib "*") (part "PESD5V0U1UA,115"))
    )
    (comp (ref "Z21")
      (value "PESD5V0U1UA,115")
      (footprint "SamacSys:SOD2512X110N")
      (description "Diode")
      (fields
        (field (name "MOUSER PART NUMBER") "771-PESD5V0U1UA-T/R")
        (field (name "RS PART NUMBER") "8166751P")
      )
      (libsource (lib "*") (part "PESD5V0U1UA,115"))
    )
    (comp (ref "Z22")
      (value "PESD5V0U1UA,115")
      (footprint "SamacSys:SOD2512X110N")
      (description "Diode")
      (fields
        (field (name "MOUSER PART NUMBER") "771-PESD5V0U1UA-T/R")
        (field (name "RS PART NUMBER") "8166751P")
      )
      (libsource (lib "*") (part "PESD5V0U1UA,115"))
    )
    (comp (ref "Z23")
      (value "PESD5V0U1UA,115")
      (footprint "SamacSys:SOD2512X110N")
      (description "Diode")
      (fields
        (field (name "MOUSER PART NUMBER") "771-PESD5V0U1UA-T/R")
        (field (name "RS PART NUMBER") "8166751P")
      )
      (libsource (lib "*") (part "PESD5V0U1UA,115"))
    )
    (comp (ref "Z24")
      (value "PESD5V0U1UA,115")
      (footprint "SamacSys:SOD2512X110N")
      (description "Diode")
      (fields
        (field (name "MOUSER PART NUMBER") "771-PESD5V0U1UA-T/R")
        (field (name "RS PART NUMBER") "8166751P")
      )
      (libsource (lib "*") (part "PESD5V0U1UA,115"))
    )
    (comp (ref "Z25")
      (value "PESD5V0U1UA,115")
      (footprint "SamacSys:SOD2512X110N")
      (description "Diode")
      (fields
        (field (name "MOUSER PART NUMBER") "771-PESD5V0U1UA-T/R")
        (field (name "RS PART NUMBER") "8166751P")
      )
      (libsource (lib "*") (part "PESD5V0U1UA,115"))
    )
    (comp (ref "Z26")
      (value "PESD5V0U1UA,115")
      (footprint "SamacSys:SOD2512X110N")
      (description "Diode")
      (fields
        (field (name "MOUSER PART NUMBER") "771-PESD5V0U1UA-T/R")
        (field (name "RS PART NUMBER") "8166751P")
      )
      (libsource (lib "*") (part "PESD5V0U1UA,115"))
    )
    (comp (ref "Z27")
      (value "PESD5V0U1UA,115")
      (footprint "SamacSys:SOD2512X110N")
      (description "Diode")
      (fields
        (field (name "MOUSER PART NUMBER") "771-PESD5V0U1UA-T/R")
        (field (name "RS PART NUMBER") "8166751P")
      )
      (libsource (lib "*") (part "PESD5V0U1UA,115"))
    )
  )
  (nets
    (net (code "1") (name "/A") (class "Default")
      (node (ref "R32") (pin "1") (pinfunction "1_1") (pintype "passive"))
      (node (ref "U1") (pin "50") (pinfunction "FAULTL+_50") (pintype "passive"))
      (node (ref "Z20") (pin "1") (pinfunction "K_1") (pintype "passive"))
    )
    (net (code "2") (name "/AUX0") (class "Default")
      (node (ref "C19") (pin "2") (pinfunction "2_2") (pintype "passive"))
      (node (ref "R72") (pin "1") (pinfunction "1_1") (pintype "passive"))
      (node (ref "R73") (pin "2") (pinfunction "2_2") (pintype "passive"))
      (node (ref "U1") (pin "66") (pinfunction "AUX0_66") (pintype "passive"))
    )
    (net (code "3") (name "/AUX1") (class "Default")
      (node (ref "C34") (pin "2") (pinfunction "2_2") (pintype "passive"))
      (node (ref "R70") (pin "1") (pinfunction "1_1") (pintype "passive"))
      (node (ref "R71") (pin "2") (pinfunction "2_2") (pintype "passive"))
      (node (ref "U1") (pin "65") (pinfunction "AUX1_65") (pintype "passive"))
    )
    (net (code "4") (name "/AUX2") (class "Default")
      (node (ref "C38") (pin "2") (pinfunction "2_2") (pintype "passive"))
      (node (ref "R68") (pin "1") (pinfunction "1_1") (pintype "passive"))
      (node (ref "R69") (pin "2") (pinfunction "2_2") (pintype "passive"))
      (node (ref "U1") (pin "64") (pinfunction "AUX2_64") (pintype "passive"))
    )
    (net (code "5") (name "/AUX3") (class "Default")
      (node (ref "C37") (pin "2") (pinfunction "2_2") (pintype "passive"))
      (node (ref "R66") (pin "1") (pinfunction "1_1") (pintype "passive"))
      (node (ref "R67") (pin "2") (pinfunction "2_2") (pintype "passive"))
      (node (ref "U1") (pin "63") (pinfunction "AUX3_63") (pintype "passive"))
    )
    (net (code "6") (name "/AUX4") (class "Default")
      (node (ref "C35") (pin "2") (pinfunction "2_2") (pintype "passive"))
      (node (ref "R63") (pin "1") (pinfunction "1_1") (pintype "passive"))
      (node (ref "R65") (pin "2") (pinfunction "2_2") (pintype "passive"))
      (node (ref "U1") (pin "62") (pinfunction "AUX4_62") (pintype "passive"))
    )
    (net (code "7") (name "/AUX5") (class "Default")
      (node (ref "C32") (pin "2") (pinfunction "2_2") (pintype "passive"))
      (node (ref "R56") (pin "1") (pinfunction "1_1") (pintype "passive"))
      (node (ref "R58") (pin "2") (pinfunction "2_2") (pintype "passive"))
      (node (ref "U1") (pin "61") (pinfunction "AUX5_61") (pintype "passive"))
    )
    (net (code "8") (name "/AUX6") (class "Default")
      (node (ref "C31") (pin "2") (pinfunction "2_2") (pintype "passive"))
      (node (ref "R53") (pin "1") (pinfunction "1_1") (pintype "passive"))
      (node (ref "R55") (pin "2") (pinfunction "2_2") (pintype "passive"))
      (node (ref "U1") (pin "60") (pinfunction "AUX6_60") (pintype "passive"))
    )
    (net (code "9") (name "/AUX7") (class "Default")
      (node (ref "C29") (pin "2") (pinfunction "2_2") (pintype "passive"))
      (node (ref "R50") (pin "1") (pinfunction "1_1") (pintype "passive"))
      (node (ref "R51") (pin "2") (pinfunction "2_2") (pintype "passive"))
      (node (ref "U1") (pin "59") (pinfunction "AUX7_59") (pintype "passive"))
    )
    (net (code "10") (name "/B") (class "Default")
      (node (ref "R31") (pin "1") (pinfunction "1_1") (pintype "passive"))
      (node (ref "U1") (pin "51") (pinfunction "FAULTL-_51") (pintype "passive"))
      (node (ref "Z21") (pin "1") (pinfunction "K_1") (pintype "passive"))
    )
    (net (code "11") (name "/BAT0S") (class "Default")
      (node (ref "J1") (pin "4") (pinfunction "4_4") (pintype "passive"))
      (node (ref "Q1") (pin "2") (pinfunction "S_2") (pintype "passive"))
      (node (ref "R137") (pin "1") (pinfunction "1_1") (pintype "passive"))
      (node (ref "R138") (pin "1") (pinfunction "1_1") (pintype "passive"))
    )
    (net (code "12") (name "/BAT1") (class "Default")
      (node (ref "J1") (pin "5") (pinfunction "5_5") (pintype "passive"))
      (node (ref "Q2") (pin "2") (pinfunction "S_2") (pintype "passive"))
      (node (ref "R1") (pin "2") (pinfunction "2_2") (pintype "passive"))
      (node (ref "R130") (pin "1") (pinfunction "1_1") (pintype "passive"))
      (node (ref "R132") (pin "1") (pinfunction "1_1") (pintype "passive"))
      (node (ref "R134") (pin "2") (pinfunction "2_2") (pintype "passive"))
    )
    (net (code "13") (name "/BAT2") (class "Default")
      (node (ref "J1") (pin "6") (pinfunction "6_6") (pintype "passive"))
      (node (ref "Q3") (pin "2") (pinfunction "S_2") (pintype "passive"))
      (node (ref "R122") (pin "1") (pinfunction "1_1") (pintype "passive"))
      (node (ref "R124") (pin "1") (pinfunction "1_1") (pintype "passive"))
      (node (ref "R126") (pin "2") (pinfunction "2_2") (pintype "passive"))
      (node (ref "R2") (pin "2") (pinfunction "2_2") (pintype "passive"))
    )
    (net (code "14") (name "/BAT3") (class "Default")
      (node (ref "J1") (pin "7") (pinfunction "7_7") (pintype "passive"))
      (node (ref "Q4") (pin "2") (pinfunction "S_2") (pintype "passive"))
      (node (ref "R114") (pin "1") (pinfunction "1_1") (pintype "passive"))
      (node (ref "R116") (pin "1") (pinfunction "1_1") (pintype "passive"))
      (node (ref "R118") (pin "2") (pinfunction "2_2") (pintype "passive"))
      (node (ref "R3") (pin "2") (pinfunction "2_2") (pintype "passive"))
    )
    (net (code "15") (name "/BAT4") (class "Default")
      (node (ref "J1") (pin "8") (pinfunction "8_8") (pintype "passive"))
      (node (ref "Q5") (pin "2") (pinfunction "S_2") (pintype "passive"))
      (node (ref "R106") (pin "1") (pinfunction "1_1") (pintype "passive"))
      (node (ref "R108") (pin "1") (pinfunction "1_1") (pintype "passive"))
      (node (ref "R110") (pin "2") (pinfunction "2_2") (pintype "passive"))
      (node (ref "R4") (pin "2") (pinfunction "2_2") (pintype "passive"))
    )
    (net (code "16") (name "/BAT5") (class "Default")
      (node (ref "J1") (pin "9") (pinfunction "9_9") (pintype "passive"))
      (node (ref "Q6") (pin "2") (pinfunction "S_2") (pintype "passive"))
      (node (ref "R100") (pin "1") (pinfunction "1_1") (pintype "passive"))
      (node (ref "R102") (pin "2") (pinfunction "2_2") (pintype "passive"))
      (node (ref "R5") (pin "2") (pinfunction "2_2") (pintype "passive"))
      (node (ref "R98") (pin "1") (pinfunction "1_1") (pintype "passive"))
    )
    (net (code "17") (name "/BAT6") (class "Default")
      (node (ref "J1") (pin "10") (pinfunction "10_10") (pintype "passive"))
      (node (ref "Q7") (pin "2") (pinfunction "S_2") (pintype "passive"))
      (node (ref "R6") (pin "2") (pinfunction "2_2") (pintype "passive"))
      (node (ref "R90") (pin "1") (pinfunction "1_1") (pintype "passive"))
      (node (ref "R92") (pin "1") (pinfunction "1_1") (pintype "passive"))
      (node (ref "R94") (pin "2") (pinfunction "2_2") (pintype "passive"))
    )
    (net (code "18") (name "/BAT7") (class "Default")
      (node (ref "J1") (pin "11") (pinfunction "11_11") (pintype "passive"))
      (node (ref "Q8") (pin "2") (pinfunction "S_2") (pintype "passive"))
      (node (ref "R7") (pin "2") (pinfunction "2_2") (pintype "passive"))
      (node (ref "R82") (pin "1") (pinfunction "1_1") (pintype "passive"))
      (node (ref "R84") (pin "1") (pinfunction "1_1") (pintype "passive"))
      (node (ref "R86") (pin "2") (pinfunction "2_2") (pintype "passive"))
    )
    (net (code "19") (name "/BAT8") (class "Default")
      (node (ref "J1") (pin "12") (pinfunction "12_12") (pintype "passive"))
      (node (ref "Q9") (pin "2") (pinfunction "S_2") (pintype "passive"))
      (node (ref "R133") (pin "1") (pinfunction "1_1") (pintype "passive"))
      (node (ref "R135") (pin "1") (pinfunction "1_1") (pintype "passive"))
      (node (ref "R78") (pin "2") (pinfunction "2_2") (pintype "passive"))
      (node (ref "R8") (pin "2") (pinfunction "2_2") (pintype "passive"))
    )
    (net (code "20") (name "/BAT9") (class "Default")
      (node (ref "J1") (pin "13") (pinfunction "13_13") (pintype "passive"))
      (node (ref "Q10") (pin "2") (pinfunction "S_2") (pintype "passive"))
      (node (ref "R125") (pin "1") (pinfunction "1_1") (pintype "passive"))
      (node (ref "R127") (pin "1") (pinfunction "1_1") (pintype "passive"))
      (node (ref "R128") (pin "2") (pinfunction "2_2") (pintype "passive"))
      (node (ref "R9") (pin "2") (pinfunction "2_2") (pintype "passive"))
    )
    (net (code "21") (name "/BAT10") (class "Default")
      (node (ref "J1") (pin "14") (pinfunction "14_14") (pintype "passive"))
      (node (ref "Q11") (pin "2") (pinfunction "S_2") (pintype "passive"))
      (node (ref "R10") (pin "2") (pinfunction "2_2") (pintype "passive"))
      (node (ref "R117") (pin "1") (pinfunction "1_1") (pintype "passive"))
      (node (ref "R119") (pin "1") (pinfunction "1_1") (pintype "passive"))
      (node (ref "R120") (pin "2") (pinfunction "2_2") (pintype "passive"))
    )
    (net (code "22") (name "/BAT11") (class "Default")
      (node (ref "J1") (pin "15") (pinfunction "15_15") (pintype "passive"))
      (node (ref "Q12") (pin "2") (pinfunction "S_2") (pintype "passive"))
      (node (ref "R109") (pin "1") (pinfunction "1_1") (pintype "passive"))
      (node (ref "R11") (pin "2") (pinfunction "2_2") (pintype "passive"))
      (node (ref "R111") (pin "1") (pinfunction "1_1") (pintype "passive"))
      (node (ref "R112") (pin "2") (pinfunction "2_2") (pintype "passive"))
    )
    (net (code "23") (name "/BAT12") (class "Default")
      (node (ref "J1") (pin "16") (pinfunction "16_16") (pintype "passive"))
      (node (ref "Q13") (pin "2") (pinfunction "S_2") (pintype "passive"))
      (node (ref "R101") (pin "1") (pinfunction "1_1") (pintype "passive"))
      (node (ref "R103") (pin "1") (pinfunction "1_1") (pintype "passive"))
      (node (ref "R104") (pin "2") (pinfunction "2_2") (pintype "passive"))
      (node (ref "R12") (pin "2") (pinfunction "2_2") (pintype "passive"))
    )
    (net (code "24") (name "/BAT13") (class "Default")
      (node (ref "J1") (pin "17") (pinfunction "17_17") (pintype "passive"))
      (node (ref "Q14") (pin "2") (pinfunction "S_2") (pintype "passive"))
      (node (ref "R13") (pin "2") (pinfunction "2_2") (pintype "passive"))
      (node (ref "R93") (pin "1") (pinfunction "1_1") (pintype "passive"))
      (node (ref "R95") (pin "1") (pinfunction "1_1") (pintype "passive"))
      (node (ref "R96") (pin "2") (pinfunction "2_2") (pintype "passive"))
    )
    (net (code "25") (name "/BAT14") (class "Default")
      (node (ref "J1") (pin "18") (pinfunction "18_18") (pintype "passive"))
      (node (ref "Q15") (pin "2") (pinfunction "S_2") (pintype "passive"))
      (node (ref "R14") (pin "2") (pinfunction "2_2") (pintype "passive"))
      (node (ref "R85") (pin "1") (pinfunction "1_1") (pintype "passive"))
      (node (ref "R87") (pin "1") (pinfunction "1_1") (pintype "passive"))
      (node (ref "R88") (pin "2") (pinfunction "2_2") (pintype "passive"))
    )
    (net (code "26") (name "/BAT15") (class "Default")
      (node (ref "J1") (pin "19") (pinfunction "19_19") (pintype "passive"))
      (node (ref "Q16") (pin "2") (pinfunction "S_2") (pintype "passive"))
      (node (ref "R15") (pin "2") (pinfunction "2_2") (pintype "passive"))
      (node (ref "R77") (pin "1") (pinfunction "1_1") (pintype "passive"))
      (node (ref "R79") (pin "1") (pinfunction "1_1") (pintype "passive"))
      (node (ref "R80") (pin "2") (pinfunction "2_2") (pintype "passive"))
    )
    (net (code "27") (name "/BAT16") (class "Default")
      (node (ref "J1") (pin "2") (pinfunction "2_2") (pintype "passive"))
      (node (ref "J1") (pin "21") (pinfunction "21_21") (pintype "passive"))
      (node (ref "R20") (pin "1") (pinfunction "1_1") (pintype "passive"))
      (node (ref "R52") (pin "1") (pinfunction "1_1") (pintype "passive"))
      (node (ref "Z19") (pin "1") (pinfunction "K_1") (pintype "passive"))
    )
    (net (code "28") (name "/BAT16S") (class "Default")
      (node (ref "J1") (pin "20") (pinfunction "20_20") (pintype "passive"))
      (node (ref "R16") (pin "2") (pinfunction "2_2") (pintype "passive"))
      (node (ref "R74") (pin "1") (pinfunction "1_1") (pintype "passive"))
      (node (ref "R75") (pin "2") (pinfunction "2_2") (pintype "passive"))
    )
    (net (code "29") (name "/C") (class "Default")
      (node (ref "R30") (pin "1") (pinfunction "1_1") (pintype "passive"))
      (node (ref "SW2") (pin "2") (pinfunction "2_2") (pintype "passive"))
      (node (ref "U1") (pin "52") (pinfunction "COMML+_52") (pintype "passive"))
      (node (ref "Z22") (pin "1") (pinfunction "K_1") (pintype "passive"))
    )
    (net (code "30") (name "/COMMH+") (class "Default")
      (node (ref "R27") (pin "2") (pinfunction "2_2") (pintype "passive"))
      (node (ref "T3") (pin "3") (pinfunction "3_3") (pintype "passive"))
    )
    (net (code "31") (name "/COMMH-") (class "Default")
      (node (ref "R28") (pin "2") (pinfunction "2_2") (pintype "passive"))
      (node (ref "T3") (pin "4") (pinfunction "4_4") (pintype "passive"))
    )
    (net (code "32") (name "/COMML+") (class "Default")
      (node (ref "R30") (pin "2") (pinfunction "2_2") (pintype "passive"))
      (node (ref "T2") (pin "4") (pinfunction "4_4") (pintype "passive"))
    )
    (net (code "33") (name "/COMML-") (class "Default")
      (node (ref "R29") (pin "2") (pinfunction "2_2") (pintype "passive"))
      (node (ref "T2") (pin "3") (pinfunction "3_3") (pintype "passive"))
    )
    (net (code "34") (name "/D") (class "Default")
      (node (ref "R29") (pin "1") (pinfunction "1_1") (pintype "passive"))
      (node (ref "SW2") (pin "4") (pinfunction "4_4") (pintype "passive"))
      (node (ref "U1") (pin "53") (pinfunction "COMML-_53") (pintype "passive"))
      (node (ref "Z23") (pin "1") (pinfunction "K_1") (pintype "passive"))
    )
    (net (code "35") (name "/E") (class "Default")
      (node (ref "R28") (pin "1") (pinfunction "1_1") (pintype "passive"))
      (node (ref "U1") (pin "54") (pinfunction "COMMH-_54") (pintype "passive"))
      (node (ref "Z24") (pin "1") (pinfunction "K_1") (pintype "passive"))
    )
    (net (code "36") (name "/EQ1") (class "Default")
      (node (ref "R136") (pin "2") (pinfunction "2_2") (pintype "passive"))
      (node (ref "U1") (pin "28") (pinfunction "EQ1_28") (pintype "passive"))
    )
    (net (code "37") (name "/EQ2") (class "Default")
      (node (ref "R129") (pin "2") (pinfunction "2_2") (pintype "passive"))
      (node (ref "U1") (pin "26") (pinfunction "EQ2_26") (pintype "passive"))
    )
    (net (code "38") (name "/EQ3") (class "Default")
      (node (ref "R121") (pin "2") (pinfunction "2_2") (pintype "passive"))
      (node (ref "U1") (pin "24") (pinfunction "EQ3_2_24") (pintype "passive"))
    )
    (net (code "39") (name "/EQ4") (class "Default")
      (node (ref "R113") (pin "2") (pinfunction "2_2") (pintype "passive"))
      (node (ref "U1") (pin "22") (pinfunction "EQ4_22") (pintype "passive"))
    )
    (net (code "40") (name "/EQ5") (class "Default")
      (node (ref "R105") (pin "2") (pinfunction "2_2") (pintype "passive"))
      (node (ref "U1") (pin "20") (pinfunction "EQ5_20") (pintype "passive"))
    )
    (net (code "41") (name "/EQ6") (class "Default")
      (node (ref "R97") (pin "2") (pinfunction "2_2") (pintype "passive"))
      (node (ref "U1") (pin "18") (pinfunction "EQ6_18") (pintype "passive"))
    )
    (net (code "42") (name "/EQ7") (class "Default")
      (node (ref "R89") (pin "2") (pinfunction "2_2") (pintype "passive"))
      (node (ref "U1") (pin "16") (pinfunction "EQ7_16") (pintype "passive"))
    )
    (net (code "43") (name "/EQ8") (class "Default")
      (node (ref "R81") (pin "2") (pinfunction "2_2") (pintype "passive"))
      (node (ref "U1") (pin "14") (pinfunction "EQ8_14") (pintype "passive"))
    )
    (net (code "44") (name "/EQ9") (class "Default")
      (node (ref "R131") (pin "2") (pinfunction "2_2") (pintype "passive"))
      (node (ref "U1") (pin "12") (pinfunction "EQ9_12") (pintype "passive"))
    )
    (net (code "45") (name "/EQ10") (class "Default")
      (node (ref "R123") (pin "2") (pinfunction "2_2") (pintype "passive"))
      (node (ref "U1") (pin "10") (pinfunction "EQ10_10") (pintype "passive"))
    )
    (net (code "46") (name "/EQ11") (class "Default")
      (node (ref "R115") (pin "2") (pinfunction "2_2") (pintype "passive"))
      (node (ref "U1") (pin "8") (pinfunction "EQ11_8") (pintype "passive"))
    )
    (net (code "47") (name "/EQ12") (class "Default")
      (node (ref "R107") (pin "2") (pinfunction "2_2") (pintype "passive"))
      (node (ref "U1") (pin "6") (pinfunction "EQ12_6") (pintype "passive"))
    )
    (net (code "48") (name "/EQ13") (class "Default")
      (node (ref "R99") (pin "2") (pinfunction "2_2") (pintype "passive"))
      (node (ref "U1") (pin "4") (pinfunction "EQ3_1_4") (pintype "passive"))
    )
    (net (code "49") (name "/EQ14") (class "Default")
      (node (ref "R91") (pin "2") (pinfunction "2_2") (pintype "passive"))
      (node (ref "U1") (pin "2") (pinfunction "EQ14_2") (pintype "passive"))
    )
    (net (code "50") (name "/EQ15") (class "Default")
      (node (ref "R83") (pin "2") (pinfunction "2_2") (pintype "passive"))
      (node (ref "U1") (pin "80") (pinfunction "EQ15_80") (pintype "passive"))
    )
    (net (code "51") (name "/EQ16") (class "Default")
      (node (ref "R76") (pin "2") (pinfunction "2_2") (pintype "passive"))
      (node (ref "U1") (pin "78") (pinfunction "EQ16_78") (pintype "passive"))
    )
    (net (code "52") (name "/F") (class "Default")
      (node (ref "R27") (pin "1") (pinfunction "1_1") (pintype "passive"))
      (node (ref "U1") (pin "55") (pinfunction "COMMH+_55") (pintype "passive"))
      (node (ref "Z25") (pin "1") (pinfunction "K_1") (pintype "passive"))
    )
    (net (code "53") (name "/FAULTH+") (class "Default")
      (node (ref "R25") (pin "2") (pinfunction "2_2") (pintype "passive"))
      (node (ref "T4") (pin "3") (pinfunction "3_3") (pintype "passive"))
    )
    (net (code "54") (name "/FAULTH-") (class "Default")
      (node (ref "R26") (pin "2") (pinfunction "2_2") (pintype "passive"))
      (node (ref "T4") (pin "4") (pinfunction "4_4") (pintype "passive"))
    )
    (net (code "55") (name "/FAULTL+") (class "Default")
      (node (ref "R32") (pin "2") (pinfunction "2_2") (pintype "passive"))
      (node (ref "T1") (pin "4") (pinfunction "4_4") (pintype "passive"))
    )
    (net (code "56") (name "/FAULTL-") (class "Default")
      (node (ref "R31") (pin "2") (pinfunction "2_2") (pintype "passive"))
      (node (ref "T1") (pin "3") (pinfunction "3_3") (pintype "passive"))
    )
    (net (code "57") (name "/FAULT_N") (class "Default")
      (node (ref "J3") (pin "2") (pinfunction "2_2") (pintype "passive"))
      (node (ref "R19") (pin "2") (pinfunction "2_2") (pintype "passive"))
      (node (ref "R35") (pin "2") (pinfunction "2_2") (pintype "passive"))
    )
    (net (code "58") (name "/G") (class "Default")
      (node (ref "R26") (pin "1") (pinfunction "1_1") (pintype "passive"))
      (node (ref "U1") (pin "56") (pinfunction "FAULTH-_56") (pintype "passive"))
      (node (ref "Z26") (pin "1") (pinfunction "K_1") (pintype "passive"))
    )
    (net (code "59") (name "/GPIO0") (class "Default")
      (node (ref "P1") (pin "1") (pinfunction "1_1") (pintype "passive"))
      (node (ref "U1") (pin "47") (pinfunction "GPIO0_47") (pintype "passive"))
    )
    (net (code "60") (name "/GPIO1") (class "Default")
      (node (ref "P1") (pin "3") (pinfunction "3_3") (pintype "passive"))
      (node (ref "U1") (pin "46") (pinfunction "GPIO1_46") (pintype "passive"))
    )
    (net (code "61") (name "/GPIO2") (class "Default")
      (node (ref "P1") (pin "5") (pinfunction "5_5") (pintype "passive"))
      (node (ref "U1") (pin "45") (pinfunction "GPIO2_45") (pintype "passive"))
    )
    (net (code "62") (name "/GPIO3") (class "Default")
      (node (ref "P1") (pin "7") (pinfunction "7_7") (pintype "passive"))
      (node (ref "U1") (pin "44") (pinfunction "GPIO3_44") (pintype "passive"))
    )
    (net (code "63") (name "/GPIO4") (class "Default")
      (node (ref "P1") (pin "9") (pinfunction "9_9") (pintype "passive"))
      (node (ref "U1") (pin "43") (pinfunction "GPIO4_43") (pintype "passive"))
    )
    (net (code "64") (name "/GPIO5") (class "Default")
      (node (ref "P1") (pin "11") (pinfunction "11_11") (pintype "passive"))
      (node (ref "U1") (pin "42") (pinfunction "GPIO5_42") (pintype "passive"))
    )
    (net (code "65") (name "/H") (class "Default")
      (node (ref "R25") (pin "1") (pinfunction "1_1") (pintype "passive"))
      (node (ref "U1") (pin "57") (pinfunction "FAULTH+_57") (pintype "passive"))
      (node (ref "Z27") (pin "1") (pinfunction "K_1") (pintype "passive"))
    )
    (net (code "66") (name "/ISO-COMMH+") (class "Default")
      (node (ref "C25") (pin "1") (pinfunction "1_1") (pintype "passive"))
      (node (ref "J5") (pin "3") (pinfunction "3_3") (pintype "passive"))
    )
    (net (code "67") (name "/ISO-COMMH-") (class "Default")
      (node (ref "C24") (pin "1") (pinfunction "1_1") (pintype "passive"))
      (node (ref "J5") (pin "4") (pinfunction "4_4") (pintype "passive"))
    )
    (net (code "68") (name "/ISO-COMML+") (class "Default")
      (node (ref "C22") (pin "1") (pinfunction "1_1") (pintype "passive"))
      (node (ref "J4") (pin "2") (pinfunction "2_2") (pintype "passive"))
    )
    (net (code "69") (name "/ISO-COMML-") (class "Default")
      (node (ref "C23") (pin "1") (pinfunction "1_1") (pintype "passive"))
      (node (ref "J4") (pin "1") (pinfunction "1_1") (pintype "passive"))
    )
    (net (code "70") (name "/ISO-FAULTH+") (class "Default")
      (node (ref "C27") (pin "1") (pinfunction "1_1") (pintype "passive"))
      (node (ref "J5") (pin "1") (pinfunction "1_1") (pintype "passive"))
    )
    (net (code "71") (name "/ISO-FAULTH-") (class "Default")
      (node (ref "C26") (pin "1") (pinfunction "1_1") (pintype "passive"))
      (node (ref "J5") (pin "2") (pinfunction "2_2") (pintype "passive"))
    )
    (net (code "72") (name "/ISO-FAULTL+") (class "Default")
      (node (ref "C20") (pin "1") (pinfunction "1_1") (pintype "passive"))
      (node (ref "J4") (pin "4") (pinfunction "4_4") (pintype "passive"))
    )
    (net (code "73") (name "/ISO-FAULTL-") (class "Default")
      (node (ref "C21") (pin "1") (pinfunction "1_1") (pintype "passive"))
      (node (ref "J4") (pin "3") (pinfunction "3_3") (pintype "passive"))
    )
    (net (code "74") (name "/NPN_BASE") (class "Default")
      (node (ref "R57") (pin "2") (pinfunction "2_2") (pintype "passive"))
      (node (ref "U1") (pin "71") (pinfunction "NPNB_71") (pintype "passive"))
    )
    (net (code "75") (name "/OUT") (class "Default")
      (node (ref "C68") (pin "1") (pinfunction "1_1") (pintype "passive"))
      (node (ref "U1") (pin "68") (pinfunction "OUT2_68") (pintype "passive"))
      (node (ref "U1") (pin "73") (pinfunction "OUT1_73") (pintype "passive"))
    )
    (net (code "76") (name "/RX") (class "Default")
      (node (ref "J3") (pin "4") (pinfunction "4_4") (pintype "passive"))
      (node (ref "R17") (pin "1") (pinfunction "1_1") (pintype "passive"))
      (node (ref "R36") (pin "2") (pinfunction "2_2") (pintype "passive"))
    )
    (net (code "77") (name "/TOP") (class "Default")
      (node (ref "C33") (pin "1") (pinfunction "1_1") (pintype "passive"))
      (node (ref "D17") (pin "1") (pinfunction "K_1") (pintype "passive"))
      (node (ref "D18") (pin "2") (pinfunction "A_2") (pintype "passive"))
      (node (ref "R20") (pin "2") (pinfunction "2_2") (pintype "passive"))
      (node (ref "U1") (pin "76") (pinfunction "TOP_76") (pintype "passive"))
    )
    (net (code "78") (name "/TX") (class "Default")
      (node (ref "J3") (pin "5") (pinfunction "5_5") (pintype "passive"))
      (node (ref "R37") (pin "2") (pinfunction "2_2") (pintype "passive"))
    )
    (net (code "79") (name "/V5VAO") (class "Default")
      (node (ref "C28") (pin "1") (pinfunction "1_1") (pintype "passive"))
      (node (ref "R21") (pin "2") (pinfunction "2_2") (pintype "passive"))
      (node (ref "U1") (pin "58") (pinfunction "V5VAO_58") (pintype "passive"))
    )
    (net (code "80") (name "/VCC") (class "Default")
      (node (ref "C67") (pin "2") (pinfunction "2_2") (pintype "passive"))
      (node (ref "D19") (pin "2") (pinfunction "A_2") (pintype "passive"))
      (node (ref "J3") (pin "3") (pinfunction "3_3") (pintype "passive"))
      (node (ref "R24") (pin "2") (pinfunction "2_2") (pintype "passive"))
      (node (ref "U2") (pin "5") (pinfunction "VCC_5") (pintype "passive"))
    )
    (net (code "81") (name "/VDIG") (class "Default")
      (node (ref "C64") (pin "1") (pinfunction "1_1") (pintype "passive"))
      (node (ref "C66") (pin "1") (pinfunction "1_1") (pintype "passive"))
      (node (ref "R61") (pin "1") (pinfunction "1_1") (pintype "passive"))
      (node (ref "U1") (pin "34") (pinfunction "VDIG_34") (pintype "passive"))
    )
    (net (code "82") (name "/VIO") (class "Default")
      (node (ref "C17") (pin "1") (pinfunction "1_1") (pintype "passive"))
      (node (ref "C62") (pin "1") (pinfunction "1_1") (pintype "passive"))
      (node (ref "Q18") (pin "3") (pinfunction "D_3") (pintype "passive"))
      (node (ref "R17") (pin "2") (pinfunction "2_2") (pintype "passive"))
      (node (ref "R34") (pin "1") (pinfunction "1_1") (pintype "passive"))
      (node (ref "SW2") (pin "1") (pinfunction "1_1") (pintype "passive"))
      (node (ref "U1") (pin "41") (pinfunction "VIO_41") (pintype "passive"))
    )
    (net (code "83") (name "/VIO-REG") (class "Default")
      (node (ref "R62") (pin "1") (pinfunction "1_1") (pintype "passive"))
      (node (ref "SW2") (pin "5") (pinfunction "5_5") (pintype "passive"))
    )
    (net (code "84") (name "/VM") (class "Default")
      (node (ref "C41") (pin "1") (pinfunction "1_1") (pintype "passive"))
      (node (ref "C63") (pin "1") (pinfunction "1_1") (pintype "passive"))
      (node (ref "U1") (pin "31") (pinfunction "VM_31") (pintype "passive"))
    )
    (net (code "85") (name "/VP1") (class "Default")
      (node (ref "C59") (pin "1") (pinfunction "1_1") (pintype "passive"))
      (node (ref "R50") (pin "2") (pinfunction "2_2") (pintype "passive"))
      (node (ref "R53") (pin "2") (pinfunction "2_2") (pintype "passive"))
      (node (ref "R56") (pin "2") (pinfunction "2_2") (pintype "passive"))
      (node (ref "R59") (pin "2") (pinfunction "2_2") (pintype "passive"))
      (node (ref "R63") (pin "2") (pinfunction "2_2") (pintype "passive"))
      (node (ref "R64") (pin "1") (pinfunction "R1_1") (pintype "passive"))
      (node (ref "R66") (pin "2") (pinfunction "2_2") (pintype "passive"))
      (node (ref "R68") (pin "2") (pinfunction "2_2") (pintype "passive"))
      (node (ref "R70") (pin "2") (pinfunction "2_2") (pintype "passive"))
      (node (ref "R72") (pin "2") (pinfunction "2_2") (pintype "passive"))
      (node (ref "U1") (pin "70") (pinfunction "VP_70") (pintype "passive"))
    )
    (net (code "86") (name "/VREF_INT_2.5") (class "Default")
      (node (ref "C39") (pin "1") (pinfunction "1_1") (pintype "passive"))
      (node (ref "C60") (pin "1") (pinfunction "1_1") (pintype "passive"))
      (node (ref "U1") (pin "67") (pinfunction "VR_EF_67") (pintype "passive"))
    )
    (net (code "87") (name "/VSENSE0") (class "Default")
      (node (ref "C18") (pin "1") (pinfunction "1_1") (pintype "passive"))
      (node (ref "D20") (pin "2") (pinfunction "A_2") (pintype "passive"))
      (node (ref "D21") (pin "1") (pinfunction "K_1") (pintype "passive"))
      (node (ref "R138") (pin "2") (pinfunction "2_2") (pintype "passive"))
      (node (ref "U1") (pin "29") (pinfunction "VSENSE0_29") (pintype "passive"))
      (node (ref "Z1") (pin "2") (pinfunction "A_2") (pintype "passive"))
    )
    (net (code "88") (name "/VSENSE1") (class "Default")
      (node (ref "C61") (pin "2") (pinfunction "2_2") (pintype "passive"))
      (node (ref "R132") (pin "2") (pinfunction "2_2") (pintype "passive"))
      (node (ref "U1") (pin "27") (pinfunction "VSENSE1_27") (pintype "passive"))
      (node (ref "Z1") (pin "1") (pinfunction "K_1") (pintype "passive"))
      (node (ref "Z2") (pin "2") (pinfunction "A_2") (pintype "passive"))
    )
    (net (code "89") (name "/VSENSE2") (class "Default")
      (node (ref "C57") (pin "2") (pinfunction "2_2") (pintype "passive"))
      (node (ref "R124") (pin "2") (pinfunction "2_2") (pintype "passive"))
      (node (ref "U1") (pin "25") (pinfunction "VSENSE2_25") (pintype "passive"))
      (node (ref "Z2") (pin "1") (pinfunction "K_1") (pintype "passive"))
      (node (ref "Z3") (pin "2") (pinfunction "A_2") (pintype "passive"))
    )
    (net (code "90") (name "/VSENSE3") (class "Default")
      (node (ref "C55") (pin "2") (pinfunction "2_2") (pintype "passive"))
      (node (ref "R116") (pin "2") (pinfunction "2_2") (pintype "passive"))
      (node (ref "U1") (pin "23") (pinfunction "VSENSE3_23") (pintype "passive"))
      (node (ref "Z3") (pin "1") (pinfunction "K_1") (pintype "passive"))
      (node (ref "Z4") (pin "2") (pinfunction "A_2") (pintype "passive"))
    )
    (net (code "91") (name "/VSENSE4") (class "Default")
      (node (ref "C53") (pin "2") (pinfunction "2_2") (pintype "passive"))
      (node (ref "R108") (pin "2") (pinfunction "2_2") (pintype "passive"))
      (node (ref "U1") (pin "21") (pinfunction "VSENSE4_21") (pintype "passive"))
      (node (ref "Z4") (pin "1") (pinfunction "K_1") (pintype "passive"))
      (node (ref "Z5") (pin "2") (pinfunction "A_2") (pintype "passive"))
    )
    (net (code "92") (name "/VSENSE5") (class "Default")
      (node (ref "C51") (pin "2") (pinfunction "2_2") (pintype "passive"))
      (node (ref "R100") (pin "2") (pinfunction "2_2") (pintype "passive"))
      (node (ref "U1") (pin "19") (pinfunction "VSENSE5_19") (pintype "passive"))
      (node (ref "Z5") (pin "1") (pinfunction "K_1") (pintype "passive"))
      (node (ref "Z6") (pin "2") (pinfunction "A_2") (pintype "passive"))
    )
    (net (code "93") (name "/VSENSE6") (class "Default")
      (node (ref "C49") (pin "2") (pinfunction "2_2") (pintype "passive"))
      (node (ref "R92") (pin "2") (pinfunction "2_2") (pintype "passive"))
      (node (ref "U1") (pin "17") (pinfunction "VSENSE6_17") (pintype "passive"))
      (node (ref "Z6") (pin "1") (pinfunction "K_1") (pintype "passive"))
      (node (ref "Z7") (pin "2") (pinfunction "A_2") (pintype "passive"))
    )
    (net (code "94") (name "/VSENSE7") (class "Default")
      (node (ref "C47") (pin "2") (pinfunction "2_2") (pintype "passive"))
      (node (ref "R84") (pin "2") (pinfunction "2_2") (pintype "passive"))
      (node (ref "U1") (pin "15") (pinfunction "VSENSE7_15") (pintype "passive"))
      (node (ref "Z7") (pin "1") (pinfunction "K_1") (pintype "passive"))
      (node (ref "Z8") (pin "2") (pinfunction "A_2") (pintype "passive"))
    )
    (net (code "95") (name "/VSENSE8") (class "Default")
      (node (ref "C43") (pin "2") (pinfunction "2_2") (pintype "passive"))
      (node (ref "R135") (pin "2") (pinfunction "2_2") (pintype "passive"))
      (node (ref "U1") (pin "13") (pinfunction "VSENSE8_13") (pintype "passive"))
      (node (ref "Z8") (pin "1") (pinfunction "K_1") (pintype "passive"))
      (node (ref "Z9") (pin "2") (pinfunction "A_2") (pintype "passive"))
    )
    (net (code "96") (name "/VSENSE9") (class "Default")
      (node (ref "C58") (pin "2") (pinfunction "2_2") (pintype "passive"))
      (node (ref "R127") (pin "2") (pinfunction "2_2") (pintype "passive"))
      (node (ref "U1") (pin "11") (pinfunction "VSENSE9_11") (pintype "passive"))
      (node (ref "Z10") (pin "2") (pinfunction "A_2") (pintype "passive"))
      (node (ref "Z9") (pin "1") (pinfunction "K_1") (pintype "passive"))
    )
    (net (code "97") (name "/VSENSE10") (class "Default")
      (node (ref "C56") (pin "2") (pinfunction "2_2") (pintype "passive"))
      (node (ref "R119") (pin "2") (pinfunction "2_2") (pintype "passive"))
      (node (ref "U1") (pin "9") (pinfunction "VSENSE10_9") (pintype "passive"))
      (node (ref "Z10") (pin "1") (pinfunction "K_1") (pintype "passive"))
      (node (ref "Z11") (pin "2") (pinfunction "A_2") (pintype "passive"))
    )
    (net (code "98") (name "/VSENSE11") (class "Default")
      (node (ref "C54") (pin "2") (pinfunction "2_2") (pintype "passive"))
      (node (ref "R111") (pin "2") (pinfunction "2_2") (pintype "passive"))
      (node (ref "U1") (pin "7") (pinfunction "VSENSE11_7") (pintype "passive"))
      (node (ref "Z11") (pin "1") (pinfunction "K_1") (pintype "passive"))
      (node (ref "Z12") (pin "2") (pinfunction "A_2") (pintype "passive"))
    )
    (net (code "99") (name "/VSENSE12") (class "Default")
      (node (ref "C52") (pin "2") (pinfunction "2_2") (pintype "passive"))
      (node (ref "R103") (pin "2") (pinfunction "2_2") (pintype "passive"))
      (node (ref "U1") (pin "5") (pinfunction "VSENSE12_5") (pintype "passive"))
      (node (ref "Z12") (pin "1") (pinfunction "K_1") (pintype "passive"))
      (node (ref "Z13") (pin "2") (pinfunction "A_2") (pintype "passive"))
    )
    (net (code "100") (name "/VSENSE13") (class "Default")
      (node (ref "C50") (pin "2") (pinfunction "2_2") (pintype "passive"))
      (node (ref "R95") (pin "2") (pinfunction "2_2") (pintype "passive"))
      (node (ref "U1") (pin "3") (pinfunction "VSENSE13_3") (pintype "passive"))
      (node (ref "Z13") (pin "1") (pinfunction "K_1") (pintype "passive"))
      (node (ref "Z14") (pin "2") (pinfunction "A_2") (pintype "passive"))
    )
    (net (code "101") (name "/VSENSE14") (class "Default")
      (node (ref "C48") (pin "2") (pinfunction "2_2") (pintype "passive"))
      (node (ref "R87") (pin "2") (pinfunction "2_2") (pintype "passive"))
      (node (ref "U1") (pin "1") (pinfunction "VSENSE14_1") (pintype "passive"))
      (node (ref "Z14") (pin "1") (pinfunction "K_1") (pintype "passive"))
      (node (ref "Z15") (pin "2") (pinfunction "A_2") (pintype "passive"))
    )
    (net (code "102") (name "/VSENSE15") (class "Default")
      (node (ref "C46") (pin "2") (pinfunction "2_2") (pintype "passive"))
      (node (ref "R79") (pin "2") (pinfunction "2_2") (pintype "passive"))
      (node (ref "U1") (pin "79") (pinfunction "VSENSE15_79") (pintype "passive"))
      (node (ref "Z15") (pin "1") (pinfunction "K_1") (pintype "passive"))
      (node (ref "Z16") (pin "2") (pinfunction "A_2") (pintype "passive"))
    )
    (net (code "103") (name "/VSENSE16") (class "Default")
      (node (ref "C30") (pin "2") (pinfunction "2_2") (pintype "passive"))
      (node (ref "D17") (pin "2") (pinfunction "A_2") (pintype "passive"))
      (node (ref "D18") (pin "1") (pinfunction "K_1") (pintype "passive"))
      (node (ref "R74") (pin "2") (pinfunction "2_2") (pintype "passive"))
      (node (ref "U1") (pin "77") (pinfunction "VSENSE16_77") (pintype "passive"))
      (node (ref "Z16") (pin "1") (pinfunction "K_1") (pintype "passive"))
    )
    (net (code "104") (name "/Vg") (class "Default")
      (node (ref "Q19") (pin "1") (pinfunction "G_1") (pintype "passive"))
      (node (ref "R24") (pin "1") (pinfunction "1_1") (pintype "passive"))
      (node (ref "SW2") (pin "3") (pinfunction "3_3") (pintype "passive"))
    )
    (net (code "105") (name "/WAKE") (class "Default")
      (node (ref "C45") (pin "2") (pinfunction "2_2") (pintype "passive"))
      (node (ref "J3") (pin "6") (pinfunction "6_6") (pintype "passive"))
      (node (ref "U2") (pin "2") (pinfunction "A_2") (pintype "passive"))
    )
    (net (code "106") (name "/WAKEUP") (class "Default")
      (node (ref "R18") (pin "1") (pinfunction "1_1") (pintype "passive"))
      (node (ref "R33") (pin "2") (pinfunction "2_2") (pintype "passive"))
      (node (ref "U2") (pin "4") (pinfunction "Y_4") (pintype "passive"))
    )
    (net (code "107") (name "GND") (class "Default")
      (node (ref "C17") (pin "2") (pinfunction "2_2") (pintype "passive"))
      (node (ref "C18") (pin "2") (pinfunction "2_2") (pintype "passive"))
      (node (ref "C19") (pin "1") (pinfunction "1_1") (pintype "passive"))
      (node (ref "C28") (pin "2") (pinfunction "2_2") (pintype "passive"))
      (node (ref "C29") (pin "1") (pinfunction "1_1") (pintype "passive"))
      (node (ref "C30") (pin "1") (pinfunction "1_1") (pintype "passive"))
      (node (ref "C31") (pin "1") (pinfunction "1_1") (pintype "passive"))
      (node (ref "C32") (pin "1") (pinfunction "1_1") (pintype "passive"))
      (node (ref "C33") (pin "2") (pinfunction "2_2") (pintype "passive"))
      (node (ref "C34") (pin "1") (pinfunction "1_1") (pintype "passive"))
      (node (ref "C35") (pin "1") (pinfunction "1_1") (pintype "passive"))
      (node (ref "C36") (pin "2") (pinfunction "2_2") (pintype "passive"))
      (node (ref "C37") (pin "1") (pinfunction "1_1") (pintype "passive"))
      (node (ref "C38") (pin "1") (pinfunction "1_1") (pintype "passive"))
      (node (ref "C39") (pin "2") (pinfunction "2_2") (pintype "passive"))
      (node (ref "C40") (pin "1") (pinfunction "1_1") (pintype "passive"))
      (node (ref "C41") (pin "2") (pinfunction "2_2") (pintype "passive"))
      (node (ref "C43") (pin "1") (pinfunction "1_1") (pintype "passive"))
      (node (ref "C45") (pin "1") (pinfunction "1_1") (pintype "passive"))
      (node (ref "C46") (pin "1") (pinfunction "1_1") (pintype "passive"))
      (node (ref "C47") (pin "1") (pinfunction "1_1") (pintype "passive"))
      (node (ref "C48") (pin "1") (pinfunction "1_1") (pintype "passive"))
      (node (ref "C49") (pin "1") (pinfunction "1_1") (pintype "passive"))
      (node (ref "C50") (pin "1") (pinfunction "1_1") (pintype "passive"))
      (node (ref "C51") (pin "1") (pinfunction "1_1") (pintype "passive"))
      (node (ref "C52") (pin "1") (pinfunction "1_1") (pintype "passive"))
      (node (ref "C53") (pin "1") (pinfunction "1_1") (pintype "passive"))
      (node (ref "C54") (pin "1") (pinfunction "1_1") (pintype "passive"))
      (node (ref "C55") (pin "1") (pinfunction "1_1") (pintype "passive"))
      (node (ref "C56") (pin "1") (pinfunction "1_1") (pintype "passive"))
      (node (ref "C57") (pin "1") (pinfunction "1_1") (pintype "passive"))
      (node (ref "C58") (pin "1") (pinfunction "1_1") (pintype "passive"))
      (node (ref "C59") (pin "2") (pinfunction "2_2") (pintype "passive"))
      (node (ref "C60") (pin "2") (pinfunction "2_2") (pintype "passive"))
      (node (ref "C61") (pin "1") (pinfunction "1_1") (pintype "passive"))
      (node (ref "C62") (pin "2") (pinfunction "2_2") (pintype "passive"))
      (node (ref "C63") (pin "2") (pinfunction "2_2") (pintype "passive"))
      (node (ref "C64") (pin "2") (pinfunction "2_2") (pintype "passive"))
      (node (ref "C66") (pin "2") (pinfunction "2_2") (pintype "passive"))
      (node (ref "C67") (pin "1") (pinfunction "1_1") (pintype "passive"))
      (node (ref "C68") (pin "2") (pinfunction "2_2") (pintype "passive"))
      (node (ref "D20") (pin "1") (pinfunction "K_1") (pintype "passive"))
      (node (ref "D21") (pin "2") (pinfunction "A_2") (pintype "passive"))
      (node (ref "D22") (pin "1") (pinfunction "K_1") (pintype "passive"))
      (node (ref "J1") (pin "1") (pinfunction "1_1") (pintype "passive"))
      (node (ref "J1") (pin "22") (pinfunction "22_22") (pintype "passive"))
      (node (ref "J1") (pin "3") (pinfunction "3_3") (pintype "passive"))
      (node (ref "J2") (pin "1") (pinfunction "1_1") (pintype "passive"))
      (node (ref "J2") (pin "2") (pinfunction "2_2") (pintype "passive"))
      (node (ref "J2") (pin "3") (pinfunction "3_3") (pintype "passive"))
      (node (ref "J2") (pin "4") (pinfunction "4_4") (pintype "passive"))
      (node (ref "J2") (pin "5") (pinfunction "5_5") (pintype "passive"))
      (node (ref "J2") (pin "6") (pinfunction "6_6") (pintype "passive"))
      (node (ref "J2") (pin "7") (pinfunction "7_7") (pintype "passive"))
      (node (ref "J2") (pin "8") (pinfunction "8_8") (pintype "passive"))
      (node (ref "J3") (pin "1") (pinfunction "1_1") (pintype "passive"))
      (node (ref "P1") (pin "10") (pinfunction "10_10") (pintype "passive"))
      (node (ref "P1") (pin "12") (pinfunction "12_12") (pintype "passive"))
      (node (ref "P1") (pin "14") (pinfunction "14_14") (pintype "passive"))
      (node (ref "P1") (pin "2") (pinfunction "2_2") (pintype "passive"))
      (node (ref "P1") (pin "4") (pinfunction "4_4") (pintype "passive"))
      (node (ref "P1") (pin "6") (pinfunction "6_6") (pintype "passive"))
      (node (ref "P1") (pin "8") (pinfunction "8_8") (pintype "passive"))
      (node (ref "Q19") (pin "2") (pinfunction "S_2") (pintype "passive"))
      (node (ref "R18") (pin "2") (pinfunction "2_2") (pintype "passive"))
      (node (ref "R19") (pin "1") (pinfunction "1_1") (pintype "passive"))
      (node (ref "R22") (pin "2") (pinfunction "2_2") (pintype "passive"))
      (node (ref "SW2") (pin "7") (pinfunction "7_7") (pintype "passive"))
      (node (ref "U1") (pin "30") (pinfunction "DGND1_30") (pintype "passive"))
      (node (ref "U1") (pin "35") (pinfunction "DG_ND2_35") (pintype "passive"))
      (node (ref "U1") (pin "37") (pinfunction "DG_ND3_37") (pintype "passive"))
      (node (ref "U1") (pin "48") (pinfunction "CGND_48") (pintype "passive"))
      (node (ref "U1") (pin "69") (pinfunction "AGND3_69") (pintype "passive"))
      (node (ref "U1") (pin "72") (pinfunction "AGND2_72") (pintype "passive"))
      (node (ref "U1") (pin "74") (pinfunction "AGND1_74") (pintype "passive"))
      (node (ref "U2") (pin "3") (pinfunction "GND_3") (pintype "passive"))
      (node (ref "Z19") (pin "2") (pinfunction "A_2") (pintype "passive"))
      (node (ref "Z20") (pin "2") (pinfunction "A_2") (pintype "passive"))
      (node (ref "Z21") (pin "2") (pinfunction "A_2") (pintype "passive"))
      (node (ref "Z22") (pin "2") (pinfunction "A_2") (pintype "passive"))
      (node (ref "Z23") (pin "2") (pinfunction "A_2") (pintype "passive"))
      (node (ref "Z24") (pin "2") (pinfunction "A_2") (pintype "passive"))
      (node (ref "Z25") (pin "2") (pinfunction "A_2") (pintype "passive"))
      (node (ref "Z26") (pin "2") (pinfunction "A_2") (pintype "passive"))
      (node (ref "Z27") (pin "2") (pinfunction "A_2") (pintype "passive"))
    )
    (net (code "108") (name "Net-(C20-Pad2)") (class "Default")
      (node (ref "C20") (pin "2") (pinfunction "2_2") (pintype "passive"))
      (node (ref "T5") (pin "1") (pinfunction "1_1") (pintype "passive"))
    )
    (net (code "109") (name "Net-(C21-Pad2)") (class "Default")
      (node (ref "C21") (pin "2") (pinfunction "2_2") (pintype "passive"))
      (node (ref "T5") (pin "2") (pinfunction "2_2") (pintype "passive"))
    )
    (net (code "110") (name "Net-(C22-Pad2)") (class "Default")
      (node (ref "C22") (pin "2") (pinfunction "2_2") (pintype "passive"))
      (node (ref "T6") (pin "1") (pinfunction "1_1") (pintype "passive"))
    )
    (net (code "111") (name "Net-(C23-Pad2)") (class "Default")
      (node (ref "C23") (pin "2") (pinfunction "2_2") (pintype "passive"))
      (node (ref "T6") (pin "2") (pinfunction "2_2") (pintype "passive"))
    )
    (net (code "112") (name "Net-(C24-Pad2)") (class "Default")
      (node (ref "C24") (pin "2") (pinfunction "2_2") (pintype "passive"))
      (node (ref "T7") (pin "1") (pinfunction "1_1") (pintype "passive"))
    )
    (net (code "113") (name "Net-(C25-Pad2)") (class "Default")
      (node (ref "C25") (pin "2") (pinfunction "2_2") (pintype "passive"))
      (node (ref "T7") (pin "2") (pinfunction "2_2") (pintype "passive"))
    )
    (net (code "114") (name "Net-(C26-Pad2)") (class "Default")
      (node (ref "C26") (pin "2") (pinfunction "2_2") (pintype "passive"))
      (node (ref "T8") (pin "1") (pinfunction "1_1") (pintype "passive"))
    )
    (net (code "115") (name "Net-(C27-Pad2)") (class "Default")
      (node (ref "C27") (pin "2") (pinfunction "2_2") (pintype "passive"))
      (node (ref "T8") (pin "2") (pinfunction "2_2") (pintype "passive"))
    )
    (net (code "116") (name "Net-(D1-A)") (class "Default")
      (node (ref "D1") (pin "2") (pinfunction "A_2") (pintype "passive"))
      (node (ref "R134") (pin "1") (pinfunction "1_1") (pintype "passive"))
    )
    (net (code "117") (name "Net-(D1-K)") (class "Default")
      (node (ref "D1") (pin "1") (pinfunction "K_1") (pintype "passive"))
      (node (ref "Q1") (pin "3") (pinfunction "D_3") (pintype "passive"))
      (node (ref "R1") (pin "1") (pinfunction "1_1") (pintype "passive"))
    )
    (net (code "118") (name "Net-(D2-A)") (class "Default")
      (node (ref "D2") (pin "2") (pinfunction "A_2") (pintype "passive"))
      (node (ref "R126") (pin "1") (pinfunction "1_1") (pintype "passive"))
    )
    (net (code "119") (name "Net-(D2-K)") (class "Default")
      (node (ref "D2") (pin "1") (pinfunction "K_1") (pintype "passive"))
      (node (ref "Q2") (pin "3") (pinfunction "D_3") (pintype "passive"))
      (node (ref "R2") (pin "1") (pinfunction "1_1") (pintype "passive"))
    )
    (net (code "120") (name "Net-(D3-A)") (class "Default")
      (node (ref "D3") (pin "2") (pinfunction "A_2") (pintype "passive"))
      (node (ref "R118") (pin "1") (pinfunction "1_1") (pintype "passive"))
    )
    (net (code "121") (name "Net-(D3-K)") (class "Default")
      (node (ref "D3") (pin "1") (pinfunction "K_1") (pintype "passive"))
      (node (ref "Q3") (pin "3") (pinfunction "D_3") (pintype "passive"))
      (node (ref "R3") (pin "1") (pinfunction "1_1") (pintype "passive"))
    )
    (net (code "122") (name "Net-(D4-A)") (class "Default")
      (node (ref "D4") (pin "2") (pinfunction "A_2") (pintype "passive"))
      (node (ref "R110") (pin "1") (pinfunction "1_1") (pintype "passive"))
    )
    (net (code "123") (name "Net-(D4-K)") (class "Default")
      (node (ref "D4") (pin "1") (pinfunction "K_1") (pintype "passive"))
      (node (ref "Q4") (pin "3") (pinfunction "D_3") (pintype "passive"))
      (node (ref "R4") (pin "1") (pinfunction "1_1") (pintype "passive"))
    )
    (net (code "124") (name "Net-(D5-A)") (class "Default")
      (node (ref "D5") (pin "2") (pinfunction "A_2") (pintype "passive"))
      (node (ref "R102") (pin "1") (pinfunction "1_1") (pintype "passive"))
    )
    (net (code "125") (name "Net-(D5-K)") (class "Default")
      (node (ref "D5") (pin "1") (pinfunction "K_1") (pintype "passive"))
      (node (ref "Q5") (pin "3") (pinfunction "D_3") (pintype "passive"))
      (node (ref "R5") (pin "1") (pinfunction "1_1") (pintype "passive"))
    )
    (net (code "126") (name "Net-(D6-A)") (class "Default")
      (node (ref "D6") (pin "2") (pinfunction "A_2") (pintype "passive"))
      (node (ref "R94") (pin "1") (pinfunction "1_1") (pintype "passive"))
    )
    (net (code "127") (name "Net-(D6-K)") (class "Default")
      (node (ref "D6") (pin "1") (pinfunction "K_1") (pintype "passive"))
      (node (ref "Q6") (pin "3") (pinfunction "D_3") (pintype "passive"))
      (node (ref "R6") (pin "1") (pinfunction "1_1") (pintype "passive"))
    )
    (net (code "128") (name "Net-(D7-A)") (class "Default")
      (node (ref "D7") (pin "2") (pinfunction "A_2") (pintype "passive"))
      (node (ref "R86") (pin "1") (pinfunction "1_1") (pintype "passive"))
    )
    (net (code "129") (name "Net-(D7-K)") (class "Default")
      (node (ref "D7") (pin "1") (pinfunction "K_1") (pintype "passive"))
      (node (ref "Q7") (pin "3") (pinfunction "D_3") (pintype "passive"))
      (node (ref "R7") (pin "1") (pinfunction "1_1") (pintype "passive"))
    )
    (net (code "130") (name "Net-(D8-A)") (class "Default")
      (node (ref "D8") (pin "2") (pinfunction "A_2") (pintype "passive"))
      (node (ref "R78") (pin "1") (pinfunction "1_1") (pintype "passive"))
    )
    (net (code "131") (name "Net-(D8-K)") (class "Default")
      (node (ref "D8") (pin "1") (pinfunction "K_1") (pintype "passive"))
      (node (ref "Q8") (pin "3") (pinfunction "D_3") (pintype "passive"))
      (node (ref "R8") (pin "1") (pinfunction "1_1") (pintype "passive"))
    )
    (net (code "132") (name "Net-(D9-A)") (class "Default")
      (node (ref "D9") (pin "2") (pinfunction "A_2") (pintype "passive"))
      (node (ref "R128") (pin "1") (pinfunction "1_1") (pintype "passive"))
    )
    (net (code "133") (name "Net-(D9-K)") (class "Default")
      (node (ref "D9") (pin "1") (pinfunction "K_1") (pintype "passive"))
      (node (ref "Q9") (pin "3") (pinfunction "D_3") (pintype "passive"))
      (node (ref "R9") (pin "1") (pinfunction "1_1") (pintype "passive"))
    )
    (net (code "134") (name "Net-(D10-A)") (class "Default")
      (node (ref "D10") (pin "2") (pinfunction "A_2") (pintype "passive"))
      (node (ref "R120") (pin "1") (pinfunction "1_1") (pintype "passive"))
    )
    (net (code "135") (name "Net-(D10-K)") (class "Default")
      (node (ref "D10") (pin "1") (pinfunction "K_1") (pintype "passive"))
      (node (ref "Q10") (pin "3") (pinfunction "D_3") (pintype "passive"))
      (node (ref "R10") (pin "1") (pinfunction "1_1") (pintype "passive"))
    )
    (net (code "136") (name "Net-(D11-A)") (class "Default")
      (node (ref "D11") (pin "2") (pinfunction "A_2") (pintype "passive"))
      (node (ref "R112") (pin "1") (pinfunction "1_1") (pintype "passive"))
    )
    (net (code "137") (name "Net-(D11-K)") (class "Default")
      (node (ref "D11") (pin "1") (pinfunction "K_1") (pintype "passive"))
      (node (ref "Q11") (pin "3") (pinfunction "D_3") (pintype "passive"))
      (node (ref "R11") (pin "1") (pinfunction "1_1") (pintype "passive"))
    )
    (net (code "138") (name "Net-(D12-A)") (class "Default")
      (node (ref "D12") (pin "2") (pinfunction "A_2") (pintype "passive"))
      (node (ref "R104") (pin "1") (pinfunction "1_1") (pintype "passive"))
    )
    (net (code "139") (name "Net-(D12-K)") (class "Default")
      (node (ref "D12") (pin "1") (pinfunction "K_1") (pintype "passive"))
      (node (ref "Q12") (pin "3") (pinfunction "D_3") (pintype "passive"))
      (node (ref "R12") (pin "1") (pinfunction "1_1") (pintype "passive"))
    )
    (net (code "140") (name "Net-(D13-A)") (class "Default")
      (node (ref "D13") (pin "2") (pinfunction "A_2") (pintype "passive"))
      (node (ref "R96") (pin "1") (pinfunction "1_1") (pintype "passive"))
    )
    (net (code "141") (name "Net-(D13-K)") (class "Default")
      (node (ref "D13") (pin "1") (pinfunction "K_1") (pintype "passive"))
      (node (ref "Q13") (pin "3") (pinfunction "D_3") (pintype "passive"))
      (node (ref "R13") (pin "1") (pinfunction "1_1") (pintype "passive"))
    )
    (net (code "142") (name "Net-(D14-A)") (class "Default")
      (node (ref "D14") (pin "2") (pinfunction "A_2") (pintype "passive"))
      (node (ref "R88") (pin "1") (pinfunction "1_1") (pintype "passive"))
    )
    (net (code "143") (name "Net-(D14-K)") (class "Default")
      (node (ref "D14") (pin "1") (pinfunction "K_1") (pintype "passive"))
      (node (ref "Q14") (pin "3") (pinfunction "D_3") (pintype "passive"))
      (node (ref "R14") (pin "1") (pinfunction "1_1") (pintype "passive"))
    )
    (net (code "144") (name "Net-(D15-A)") (class "Default")
      (node (ref "D15") (pin "2") (pinfunction "A_2") (pintype "passive"))
      (node (ref "R80") (pin "1") (pinfunction "1_1") (pintype "passive"))
    )
    (net (code "145") (name "Net-(D15-K)") (class "Default")
      (node (ref "D15") (pin "1") (pinfunction "K_1") (pintype "passive"))
      (node (ref "Q15") (pin "3") (pinfunction "D_3") (pintype "passive"))
      (node (ref "R15") (pin "1") (pinfunction "1_1") (pintype "passive"))
    )
    (net (code "146") (name "Net-(D16-A)") (class "Default")
      (node (ref "D16") (pin "2") (pinfunction "A_2") (pintype "passive"))
      (node (ref "R75") (pin "1") (pinfunction "1_1") (pintype "passive"))
    )
    (net (code "147") (name "Net-(D16-K)") (class "Default")
      (node (ref "D16") (pin "1") (pinfunction "K_1") (pintype "passive"))
      (node (ref "Q16") (pin "3") (pinfunction "D_3") (pintype "passive"))
      (node (ref "R16") (pin "1") (pinfunction "1_1") (pintype "passive"))
    )
    (net (code "148") (name "Net-(D19-K)") (class "Default")
      (node (ref "D19") (pin "1") (pinfunction "K_1") (pintype "passive"))
      (node (ref "Q18") (pin "2") (pinfunction "S_2") (pintype "passive"))
      (node (ref "R23") (pin "2") (pinfunction "2_2") (pintype "passive"))
    )
    (net (code "149") (name "Net-(D22-A)") (class "Default")
      (node (ref "D22") (pin "2") (pinfunction "A_2") (pintype "passive"))
      (node (ref "R60") (pin "2") (pinfunction "2_2") (pintype "passive"))
    )
    (net (code "150") (name "Net-(J2-Pad9)") (class "Default")
      (node (ref "J2") (pin "9") (pinfunction "9_9") (pintype "passive"))
      (node (ref "R73") (pin "1") (pinfunction "1_1") (pintype "passive"))
    )
    (net (code "151") (name "Net-(J2-Pad10)") (class "Default")
      (node (ref "J2") (pin "10") (pinfunction "10_10") (pintype "passive"))
      (node (ref "R71") (pin "1") (pinfunction "1_1") (pintype "passive"))
    )
    (net (code "152") (name "Net-(J2-Pad11)") (class "Default")
      (node (ref "J2") (pin "11") (pinfunction "11_11") (pintype "passive"))
      (node (ref "R69") (pin "1") (pinfunction "1_1") (pintype "passive"))
    )
    (net (code "153") (name "Net-(J2-Pad12)") (class "Default")
      (node (ref "J2") (pin "12") (pinfunction "12_12") (pintype "passive"))
      (node (ref "R67") (pin "1") (pinfunction "1_1") (pintype "passive"))
    )
    (net (code "154") (name "Net-(J2-Pad13)") (class "Default")
      (node (ref "J2") (pin "13") (pinfunction "13_13") (pintype "passive"))
      (node (ref "R65") (pin "1") (pinfunction "1_1") (pintype "passive"))
    )
    (net (code "155") (name "Net-(J2-Pad14)") (class "Default")
      (node (ref "J2") (pin "14") (pinfunction "14_14") (pintype "passive"))
      (node (ref "R58") (pin "1") (pinfunction "1_1") (pintype "passive"))
    )
    (net (code "156") (name "Net-(J2-Pad15)") (class "Default")
      (node (ref "J2") (pin "15") (pinfunction "15_15") (pintype "passive"))
      (node (ref "R55") (pin "1") (pinfunction "1_1") (pintype "passive"))
    )
    (net (code "157") (name "Net-(J2-Pad16)") (class "Default")
      (node (ref "J2") (pin "16") (pinfunction "16_16") (pintype "passive"))
      (node (ref "R51") (pin "1") (pinfunction "1_1") (pintype "passive"))
    )
    (net (code "158") (name "Net-(P1-Pad13)") (class "Default")
      (node (ref "P1") (pin "13") (pinfunction "13_13") (pintype "passive"))
      (node (ref "R34") (pin "2") (pinfunction "2_2") (pintype "passive"))
    )
    (net (code "159") (name "Net-(Q1-G)") (class "Default")
      (node (ref "Q1") (pin "1") (pinfunction "G_1") (pintype "passive"))
      (node (ref "R136") (pin "1") (pinfunction "1_1") (pintype "passive"))
      (node (ref "R137") (pin "2") (pinfunction "2_2") (pintype "passive"))
    )
    (net (code "160") (name "Net-(Q2-G)") (class "Default")
      (node (ref "Q2") (pin "1") (pinfunction "G_1") (pintype "passive"))
      (node (ref "R129") (pin "1") (pinfunction "1_1") (pintype "passive"))
      (node (ref "R130") (pin "2") (pinfunction "2_2") (pintype "passive"))
    )
    (net (code "161") (name "Net-(Q3-G)") (class "Default")
      (node (ref "Q3") (pin "1") (pinfunction "G_1") (pintype "passive"))
      (node (ref "R121") (pin "1") (pinfunction "1_1") (pintype "passive"))
      (node (ref "R122") (pin "2") (pinfunction "2_2") (pintype "passive"))
    )
    (net (code "162") (name "Net-(Q4-G)") (class "Default")
      (node (ref "Q4") (pin "1") (pinfunction "G_1") (pintype "passive"))
      (node (ref "R113") (pin "1") (pinfunction "1_1") (pintype "passive"))
      (node (ref "R114") (pin "2") (pinfunction "2_2") (pintype "passive"))
    )
    (net (code "163") (name "Net-(Q5-G)") (class "Default")
      (node (ref "Q5") (pin "1") (pinfunction "G_1") (pintype "passive"))
      (node (ref "R105") (pin "1") (pinfunction "1_1") (pintype "passive"))
      (node (ref "R106") (pin "2") (pinfunction "2_2") (pintype "passive"))
    )
    (net (code "164") (name "Net-(Q6-G)") (class "Default")
      (node (ref "Q6") (pin "1") (pinfunction "G_1") (pintype "passive"))
      (node (ref "R97") (pin "1") (pinfunction "1_1") (pintype "passive"))
      (node (ref "R98") (pin "2") (pinfunction "2_2") (pintype "passive"))
    )
    (net (code "165") (name "Net-(Q7-G)") (class "Default")
      (node (ref "Q7") (pin "1") (pinfunction "G_1") (pintype "passive"))
      (node (ref "R89") (pin "1") (pinfunction "1_1") (pintype "passive"))
      (node (ref "R90") (pin "2") (pinfunction "2_2") (pintype "passive"))
    )
    (net (code "166") (name "Net-(Q8-G)") (class "Default")
      (node (ref "Q8") (pin "1") (pinfunction "G_1") (pintype "passive"))
      (node (ref "R81") (pin "1") (pinfunction "1_1") (pintype "passive"))
      (node (ref "R82") (pin "2") (pinfunction "2_2") (pintype "passive"))
    )
    (net (code "167") (name "Net-(Q9-G)") (class "Default")
      (node (ref "Q9") (pin "1") (pinfunction "G_1") (pintype "passive"))
      (node (ref "R131") (pin "1") (pinfunction "1_1") (pintype "passive"))
      (node (ref "R133") (pin "2") (pinfunction "2_2") (pintype "passive"))
    )
    (net (code "168") (name "Net-(Q10-G)") (class "Default")
      (node (ref "Q10") (pin "1") (pinfunction "G_1") (pintype "passive"))
      (node (ref "R123") (pin "1") (pinfunction "1_1") (pintype "passive"))
      (node (ref "R125") (pin "2") (pinfunction "2_2") (pintype "passive"))
    )
    (net (code "169") (name "Net-(Q11-G)") (class "Default")
      (node (ref "Q11") (pin "1") (pinfunction "G_1") (pintype "passive"))
      (node (ref "R115") (pin "1") (pinfunction "1_1") (pintype "passive"))
      (node (ref "R117") (pin "2") (pinfunction "2_2") (pintype "passive"))
    )
    (net (code "170") (name "Net-(Q12-G)") (class "Default")
      (node (ref "Q12") (pin "1") (pinfunction "G_1") (pintype "passive"))
      (node (ref "R107") (pin "1") (pinfunction "1_1") (pintype "passive"))
      (node (ref "R109") (pin "2") (pinfunction "2_2") (pintype "passive"))
    )
    (net (code "171") (name "Net-(Q13-G)") (class "Default")
      (node (ref "Q13") (pin "1") (pinfunction "G_1") (pintype "passive"))
      (node (ref "R101") (pin "2") (pinfunction "2_2") (pintype "passive"))
      (node (ref "R99") (pin "1") (pinfunction "1_1") (pintype "passive"))
    )
    (net (code "172") (name "Net-(Q14-G)") (class "Default")
      (node (ref "Q14") (pin "1") (pinfunction "G_1") (pintype "passive"))
      (node (ref "R91") (pin "1") (pinfunction "1_1") (pintype "passive"))
      (node (ref "R93") (pin "2") (pinfunction "2_2") (pintype "passive"))
    )
    (net (code "173") (name "Net-(Q15-G)") (class "Default")
      (node (ref "Q15") (pin "1") (pinfunction "G_1") (pintype "passive"))
      (node (ref "R83") (pin "1") (pinfunction "1_1") (pintype "passive"))
      (node (ref "R85") (pin "2") (pinfunction "2_2") (pintype "passive"))
    )
    (net (code "174") (name "Net-(Q16-G)") (class "Default")
      (node (ref "Q16") (pin "1") (pinfunction "G_1") (pintype "passive"))
      (node (ref "R76") (pin "1") (pinfunction "1_1") (pintype "passive"))
      (node (ref "R77") (pin "2") (pinfunction "2_2") (pintype "passive"))
    )
    (net (code "175") (name "Net-(Q17-B)") (class "Default")
      (node (ref "Q17") (pin "1") (pinfunction "B_1") (pintype "passive"))
      (node (ref "R57") (pin "1") (pinfunction "1_1") (pintype "passive"))
    )
    (net (code "176") (name "Net-(Q17-C_(TAB))") (class "Default")
      (node (ref "C40") (pin "2") (pinfunction "2_2") (pintype "passive"))
      (node (ref "Q17") (pin "4") (pinfunction "C_(TAB)_4") (pintype "passive"))
      (node (ref "R54") (pin "2") (pinfunction "2_2") (pintype "passive"))
    )
    (net (code "177") (name "Net-(Q17-E)") (class "Default")
      (node (ref "Q17") (pin "3") (pinfunction "E_3") (pintype "passive"))
      (node (ref "R59") (pin "1") (pinfunction "1_1") (pintype "passive"))
      (node (ref "R60") (pin "1") (pinfunction "1_1") (pintype "passive"))
      (node (ref "R61") (pin "2") (pinfunction "2_2") (pintype "passive"))
      (node (ref "R62") (pin "2") (pinfunction "2_2") (pintype "passive"))
    )
    (net (code "178") (name "Net-(Q18-G)") (class "Default")
      (node (ref "Q18") (pin "1") (pinfunction "G_1") (pintype "passive"))
      (node (ref "Q19") (pin "3") (pinfunction "D_3") (pintype "passive"))
      (node (ref "R23") (pin "1") (pinfunction "1_1") (pintype "passive"))
    )
    (net (code "179") (name "Net-(R21-Pad1)") (class "Default")
      (node (ref "R21") (pin "1") (pinfunction "1_1") (pintype "passive"))
      (node (ref "SW2") (pin "6") (pinfunction "6_6") (pintype "passive"))
    )
    (net (code "180") (name "Net-(R22-Pad1)") (class "Default")
      (node (ref "R22") (pin "1") (pinfunction "1_1") (pintype "passive"))
      (node (ref "SW2") (pin "8") (pinfunction "8_8") (pintype "passive"))
    )
    (net (code "181") (name "Net-(R52-Pad2)") (class "Default")
      (node (ref "R52") (pin "2") (pinfunction "2_2") (pintype "passive"))
      (node (ref "R54") (pin "1") (pinfunction "1_1") (pintype "passive"))
    )
    (net (code "182") (name "Net-(R64-R2)") (class "Default")
      (node (ref "C36") (pin "1") (pinfunction "1_1") (pintype "passive"))
      (node (ref "R64") (pin "2") (pinfunction "R2_2") (pintype "passive"))
    )
    (net (code "183") (name "Net-(T1-Pad1)") (class "Default")
      (node (ref "T1") (pin "1") (pinfunction "1_1") (pintype "passive"))
      (node (ref "T5") (pin "4") (pinfunction "4_4") (pintype "passive"))
    )
    (net (code "184") (name "Net-(T1-Pad2)") (class "Default")
      (node (ref "T1") (pin "2") (pinfunction "2_2") (pintype "passive"))
      (node (ref "T5") (pin "3") (pinfunction "3_3") (pintype "passive"))
    )
    (net (code "185") (name "Net-(T2-Pad1)") (class "Default")
      (node (ref "T2") (pin "1") (pinfunction "1_1") (pintype "passive"))
      (node (ref "T6") (pin "4") (pinfunction "4_4") (pintype "passive"))
    )
    (net (code "186") (name "Net-(T2-Pad2)") (class "Default")
      (node (ref "T2") (pin "2") (pinfunction "2_2") (pintype "passive"))
      (node (ref "T6") (pin "3") (pinfunction "3_3") (pintype "passive"))
    )
    (net (code "187") (name "Net-(T3-Pad1)") (class "Default")
      (node (ref "T3") (pin "1") (pinfunction "1_1") (pintype "passive"))
      (node (ref "T7") (pin "4") (pinfunction "4_4") (pintype "passive"))
    )
    (net (code "188") (name "Net-(T3-Pad2)") (class "Default")
      (node (ref "T3") (pin "2") (pinfunction "2_2") (pintype "passive"))
      (node (ref "T7") (pin "3") (pinfunction "3_3") (pintype "passive"))
    )
    (net (code "189") (name "Net-(T4-Pad1)") (class "Default")
      (node (ref "T4") (pin "1") (pinfunction "1_1") (pintype "passive"))
      (node (ref "T8") (pin "4") (pinfunction "4_4") (pintype "passive"))
    )
    (net (code "190") (name "Net-(T4-Pad2)") (class "Default")
      (node (ref "T4") (pin "2") (pinfunction "2_2") (pintype "passive"))
      (node (ref "T8") (pin "3") (pinfunction "3_3") (pintype "passive"))
    )
    (net (code "191") (name "Net-(U1-CHM)") (class "Default")
      (node (ref "C42") (pin "2") (pinfunction "2_2") (pintype "passive"))
      (node (ref "U1") (pin "33") (pinfunction "CHM_33") (pintype "passive"))
    )
    (net (code "192") (name "Net-(U1-CHP)") (class "Default")
      (node (ref "C42") (pin "1") (pinfunction "1_1") (pintype "passive"))
      (node (ref "U1") (pin "32") (pinfunction "CHP_32") (pintype "passive"))
    )
    (net (code "193") (name "Net-(U1-FAULT__N)") (class "Default")
      (node (ref "R35") (pin "1") (pinfunction "1_1") (pintype "passive"))
      (node (ref "U1") (pin "40") (pinfunction "FAULT__N_40") (pintype "passive"))
    )
    (net (code "194") (name "Net-(U1-RX)") (class "Default")
      (node (ref "R36") (pin "1") (pinfunction "1_1") (pintype "passive"))
      (node (ref "U1") (pin "39") (pinfunction "RX_39") (pintype "passive"))
    )
    (net (code "195") (name "Net-(U1-TX)") (class "Default")
      (node (ref "R37") (pin "1") (pinfunction "1_1") (pintype "passive"))
      (node (ref "U1") (pin "38") (pinfunction "TX_38") (pintype "passive"))
    )
    (net (code "196") (name "Net-(U1-WAKEUP)") (class "Default")
      (node (ref "R33") (pin "1") (pinfunction "1_1") (pintype "passive"))
      (node (ref "U1") (pin "49") (pinfunction "WAKEUP_49") (pintype "passive"))
    )
    (net (code "197") (name "unconnected-(C28_2-C1-Pad1)") (class "Default")
      (node (ref "C28_2") (pin "1") (pinfunction "C1_1") (pintype "passive"))
    )
    (net (code "198") (name "unconnected-(C28_2-C2-Pad2)") (class "Default")
      (node (ref "C28_2") (pin "2") (pinfunction "C2_2") (pintype "passive"))
    )
    (net (code "199") (name "unconnected-(C67_2-Pad1)") (class "Default")
      (node (ref "C67_2") (pin "1") (pinfunction "1_1") (pintype "passive"))
    )
    (net (code "200") (name "unconnected-(C67_2-Pad2)") (class "Default")
      (node (ref "C67_2") (pin "2") (pinfunction "2_2") (pintype "passive"))
    )
    (net (code "201") (name "unconnected-(Q17-C_(NOPAD)-Pad2)") (class "Default")
      (node (ref "Q17") (pin "2") (pinfunction "C_(NOPAD)_2") (pintype "passive"))
    )
    (net (code "202") (name "unconnected-(U1-NC1-Pad36)") (class "Default")
      (node (ref "U1") (pin "36") (pinfunction "NC1_36") (pintype "passive"))
    )
    (net (code "203") (name "unconnected-(U1-NC2-Pad75)") (class "Default")
      (node (ref "U1") (pin "75") (pinfunction "NC2_75") (pintype "passive"))
    )
    (net (code "204") (name "unconnected-(U2-NC-Pad1)") (class "Default")
      (node (ref "U2") (pin "1") (pinfunction "NC_1") (pintype "passive"))
    )
  )
)
